# BaseBoard.net
KiCad netlist of a schematic drawn in Altium Designer
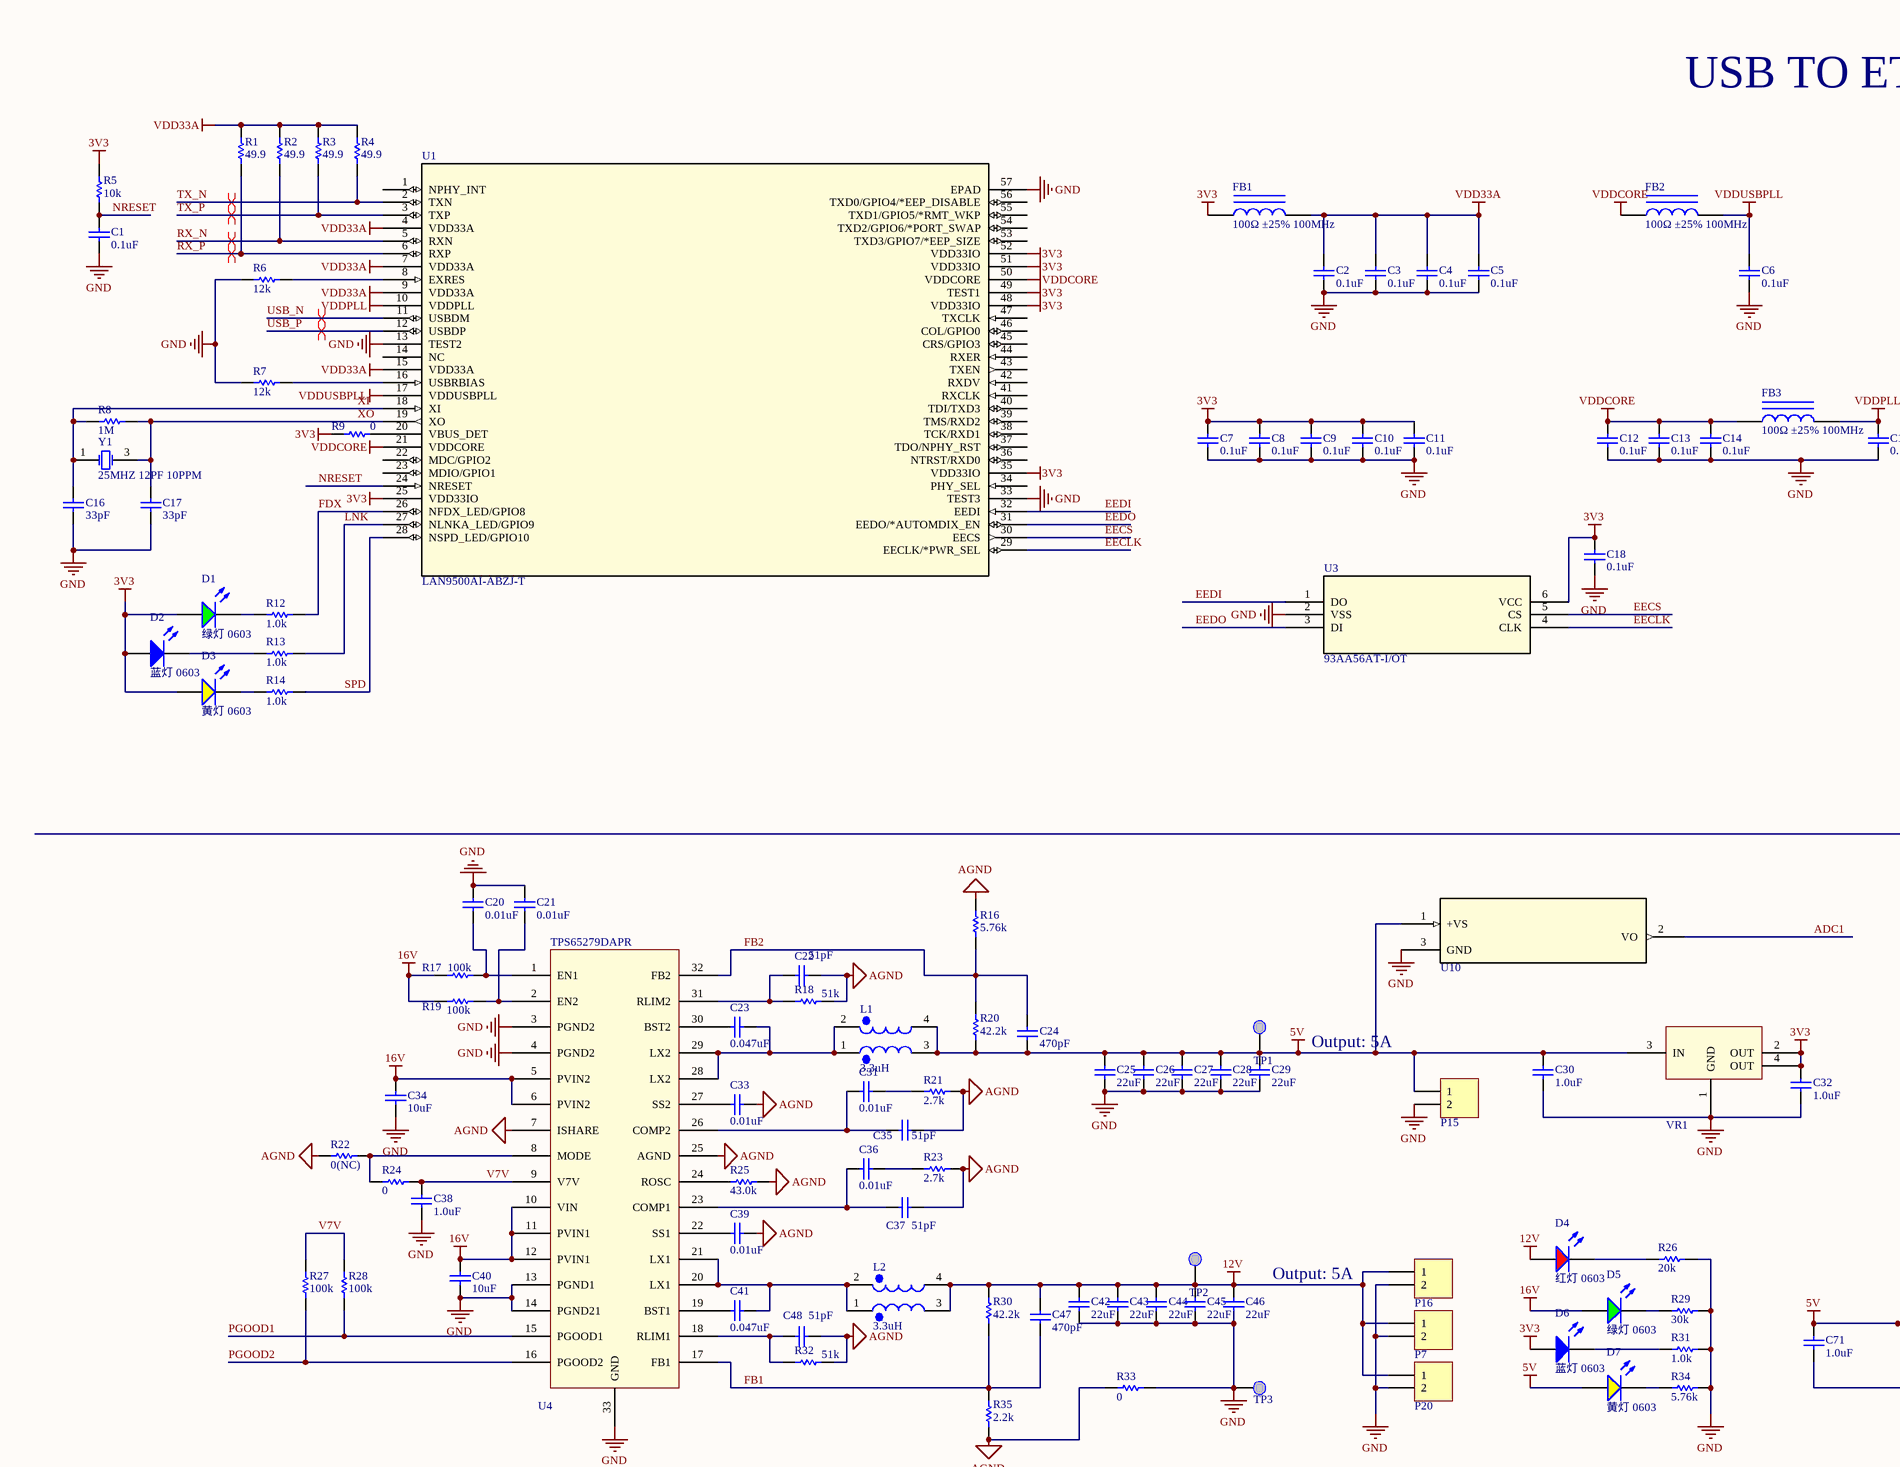
[diagram p0: BaseBoard.SchDoc, top left]
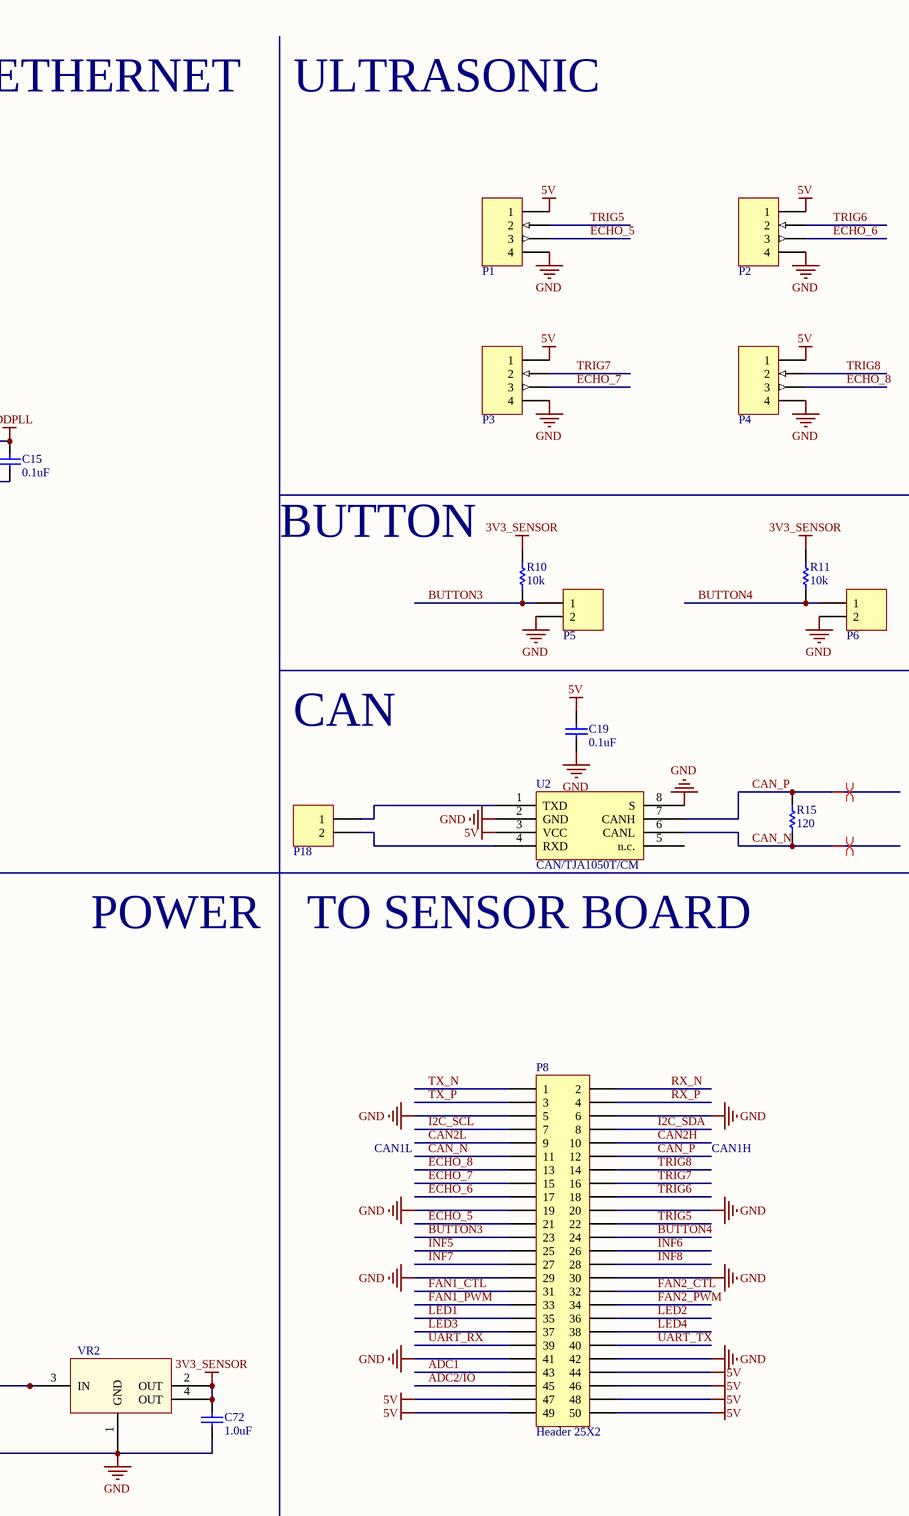
[diagram p1: BaseBoard.SchDoc, top middle]
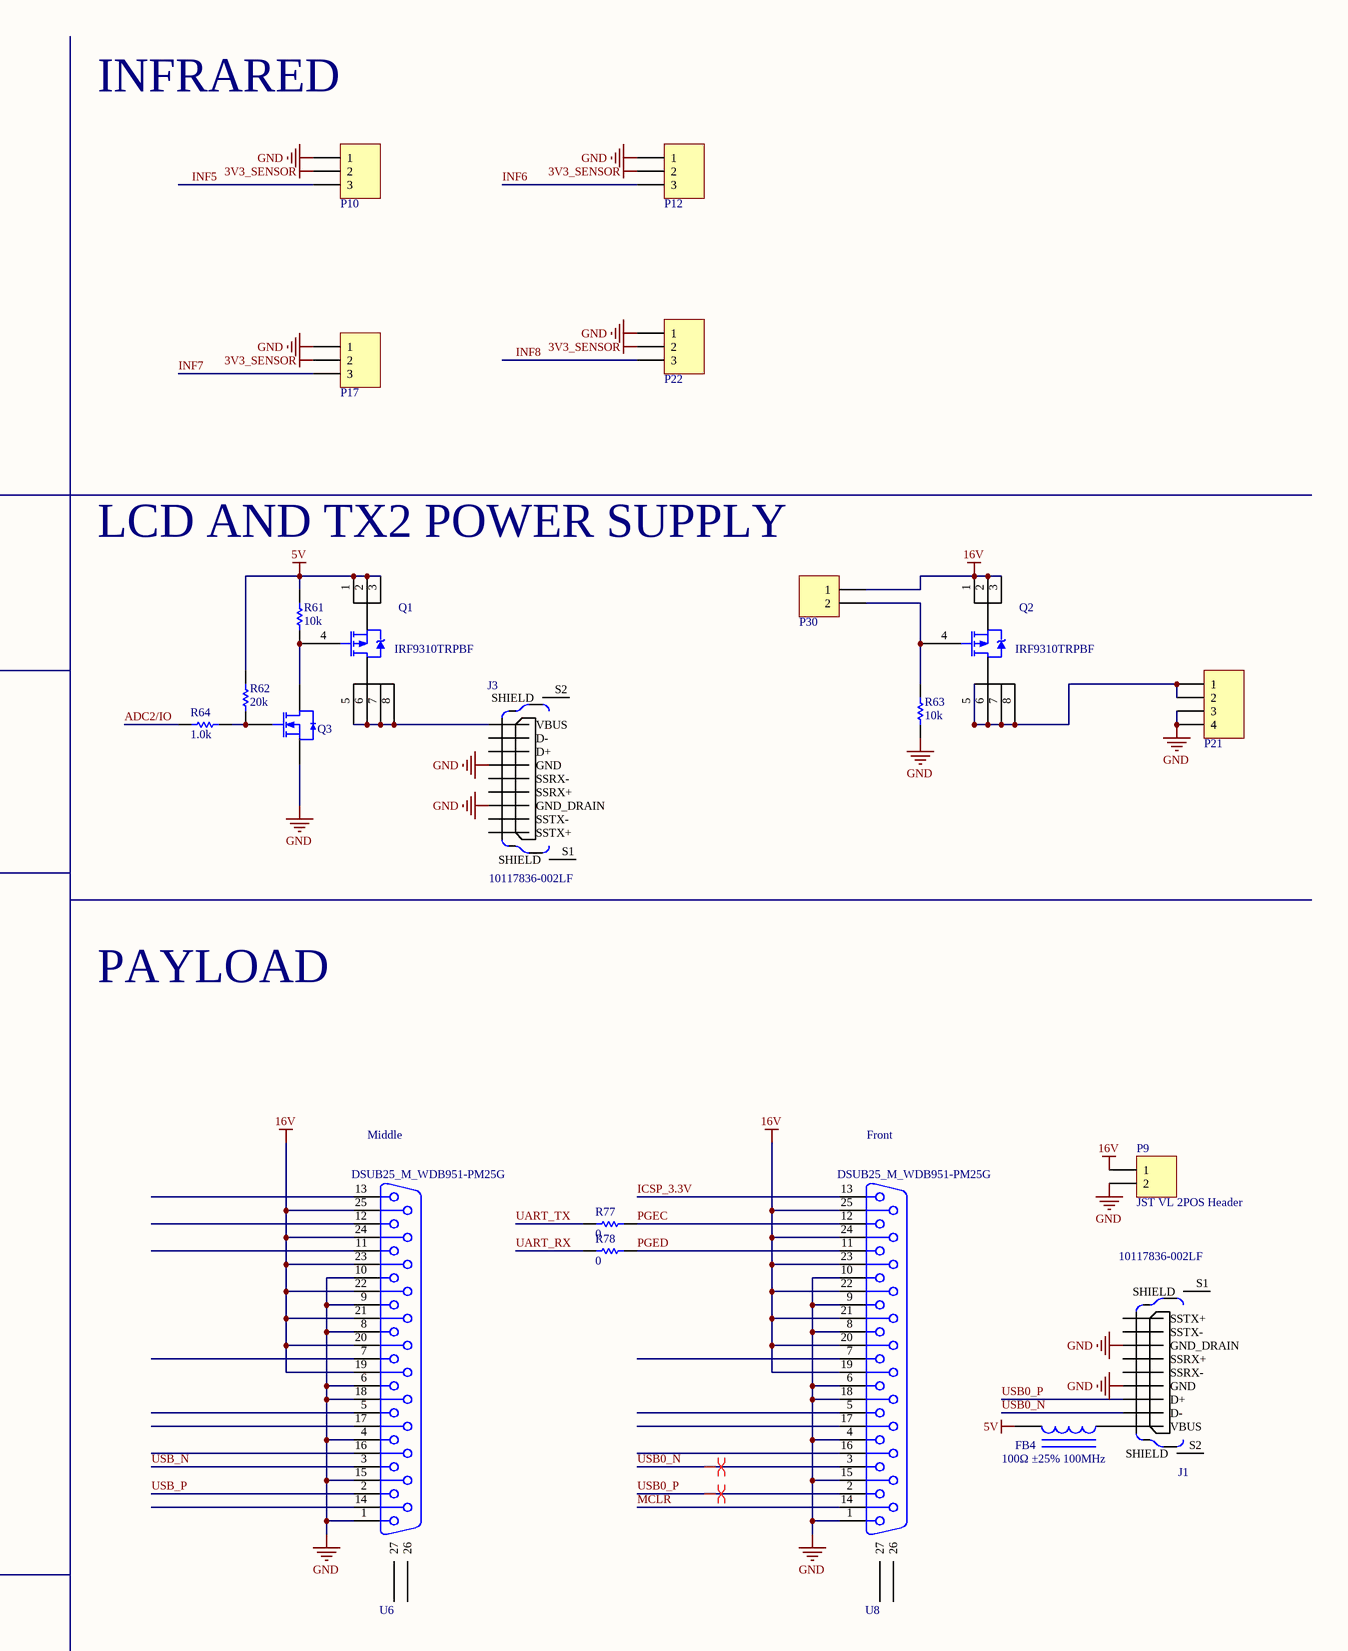
[diagram p2: BaseBoard.SchDoc, top right]
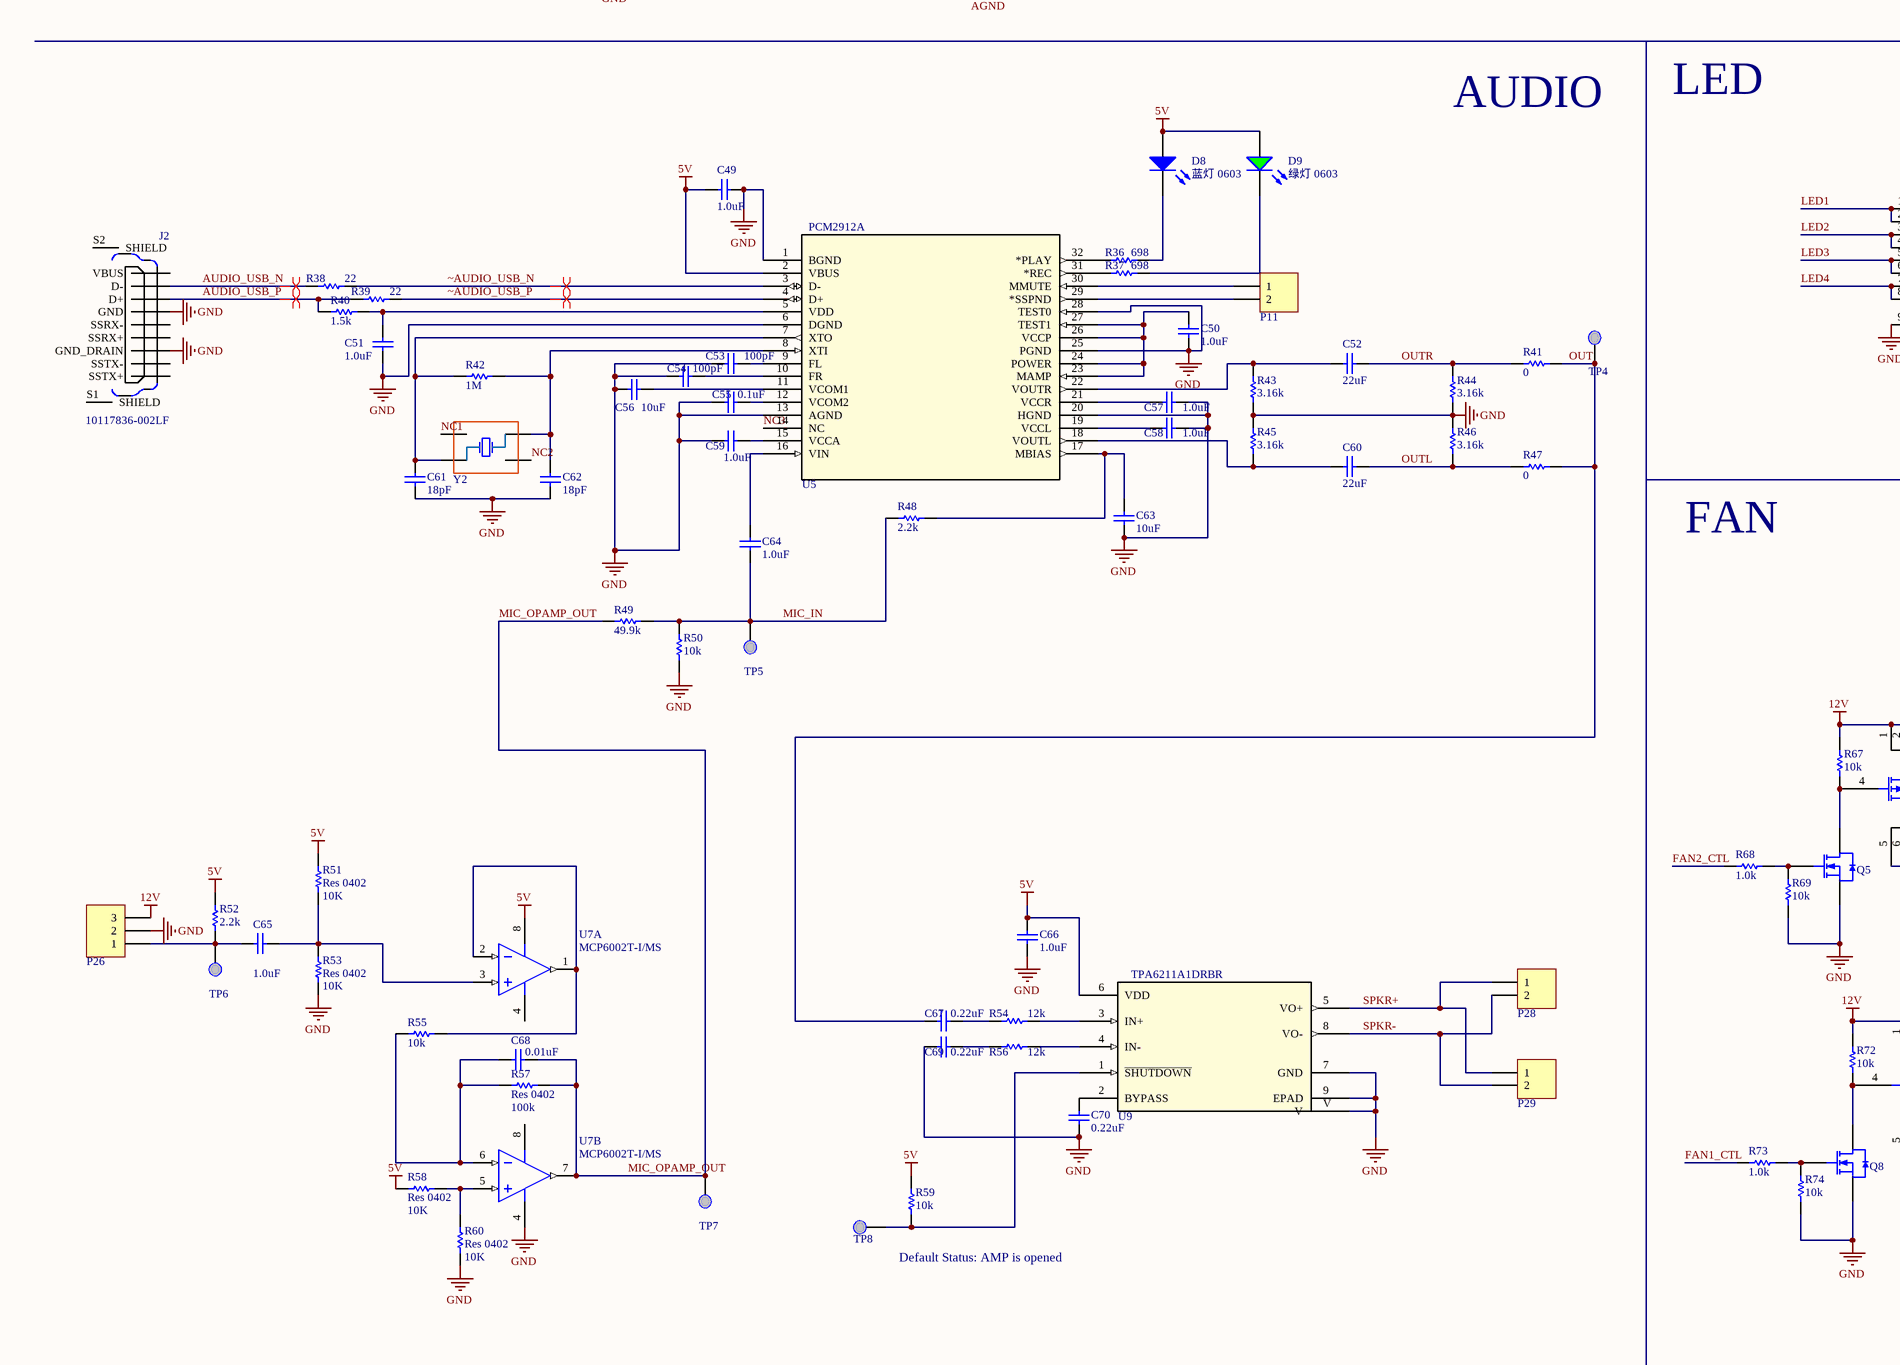
[diagram p3: BaseBoard.SchDoc, bottom left]
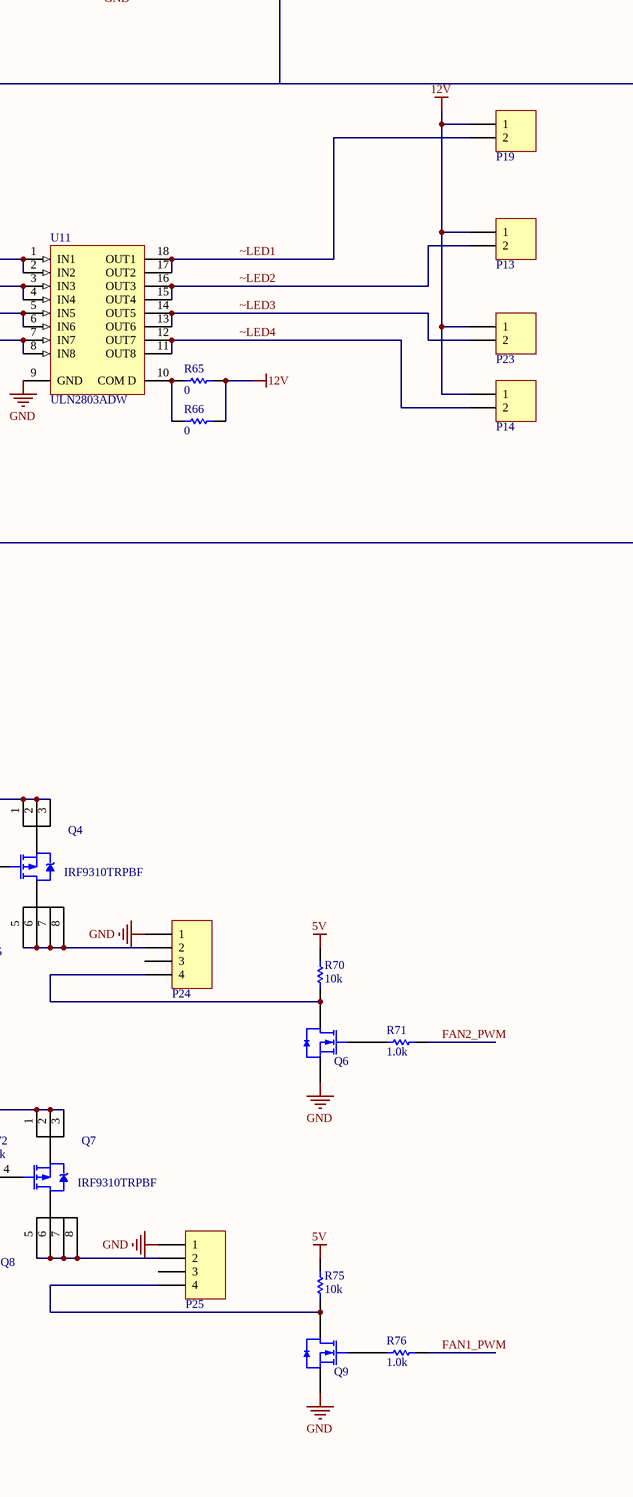
[diagram p4: BaseBoard.SchDoc, bottom middle]
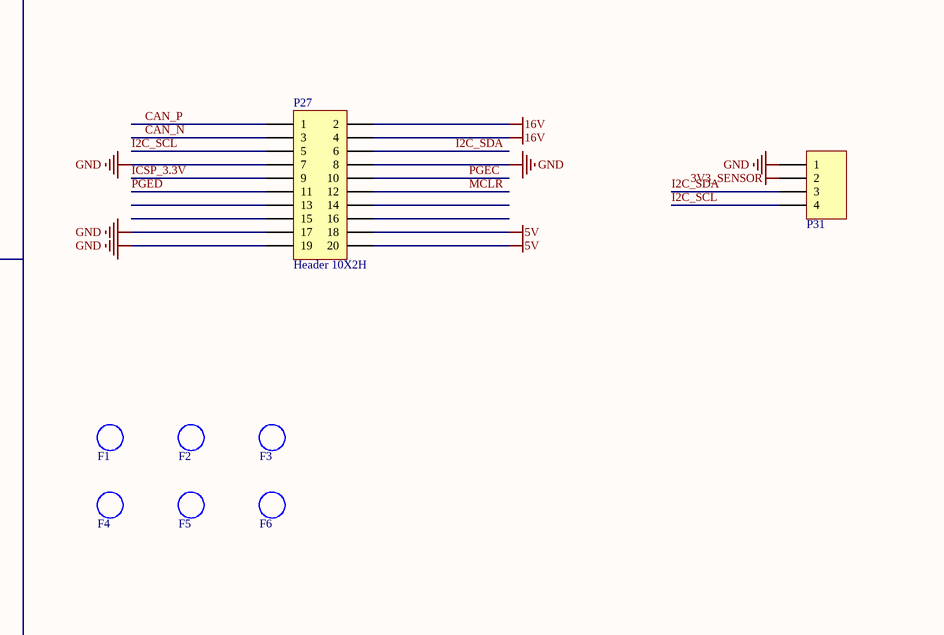
[diagram p5: BaseBoard.SchDoc, bottom right]

(export (version "E")
  (design (tool "Eeschema 10.0.6"))
  (components
    (comp (ref "C1")
      (value "0.1uF")
      (footprint "CAP0603N")
      (description "0.1µF -20%, +80% 50V Ceramic Capacitor Y5V (F) 0603 (1608 Metric)")
      (fields
        (field (name "PART NUMBER") "CAP CER 0.1UF 50V Y5V 0603")
        (field (name "MANUFACTURER") "AVX Corporation")
      )
      (libsource (lib "RoboteX") (part "Cap Non-Polar"))
    )
    (comp (ref "C2")
      (value "0.1uF")
      (footprint "CAP0402N")
      (description "CAP CER 0.1UF 50V 10% X7R 0402")
      (fields
        (field (name "MANUFACTURER") "TDK Corporation")
        (field (name "MANUFACTURER PART NUMBER") "C1005X7R1H104K")
      )
      (libsource (lib "RoboteX") (part "Cap Non-Polar"))
    )
    (comp (ref "C3")
      (value "0.1uF")
      (footprint "CAP0402N")
      (description "CAP CER 0.1UF 50V 10% X7R 0402")
      (fields
        (field (name "MANUFACTURER") "TDK Corporation")
        (field (name "MANUFACTURER PART NUMBER") "C1005X7R1H104K")
      )
      (libsource (lib "RoboteX") (part "Cap Non-Polar"))
    )
    (comp (ref "C4")
      (value "0.1uF")
      (footprint "CAP0402N")
      (description "CAP CER 0.1UF 50V 10% X7R 0402")
      (fields
        (field (name "MANUFACTURER") "TDK Corporation")
        (field (name "MANUFACTURER PART NUMBER") "C1005X7R1H104K")
      )
      (libsource (lib "RoboteX") (part "Cap Non-Polar"))
    )
    (comp (ref "C5")
      (value "0.1uF")
      (footprint "CAP0402N")
      (description "CAP CER 0.1UF 50V 10% X7R 0402")
      (fields
        (field (name "MANUFACTURER") "TDK Corporation")
        (field (name "MANUFACTURER PART NUMBER") "C1005X7R1H104K")
      )
      (libsource (lib "RoboteX") (part "Cap Non-Polar"))
    )
    (comp (ref "C6")
      (value "0.1uF")
      (footprint "CAP0402N")
      (description "CAP CER 0.1UF 50V 10% X7R 0402")
      (fields
        (field (name "MANUFACTURER") "TDK Corporation")
        (field (name "MANUFACTURER PART NUMBER") "C1005X7R1H104K")
      )
      (libsource (lib "RoboteX") (part "Cap Non-Polar"))
    )
    (comp (ref "C7")
      (value "0.1uF")
      (footprint "CAP0402N")
      (description "CAP CER 0.1UF 50V 10% X7R 0402")
      (fields
        (field (name "MANUFACTURER") "TDK Corporation")
        (field (name "MANUFACTURER PART NUMBER") "C1005X7R1H104K")
      )
      (libsource (lib "RoboteX") (part "Cap Non-Polar"))
    )
    (comp (ref "C8")
      (value "0.1uF")
      (footprint "CAP0402N")
      (description "CAP CER 0.1UF 50V 10% X7R 0402")
      (fields
        (field (name "MANUFACTURER") "TDK Corporation")
        (field (name "MANUFACTURER PART NUMBER") "C1005X7R1H104K")
      )
      (libsource (lib "RoboteX") (part "Cap Non-Polar"))
    )
    (comp (ref "C9")
      (value "0.1uF")
      (footprint "CAP0402N")
      (description "CAP CER 0.1UF 50V 10% X7R 0402")
      (fields
        (field (name "MANUFACTURER") "TDK Corporation")
        (field (name "MANUFACTURER PART NUMBER") "C1005X7R1H104K")
      )
      (libsource (lib "RoboteX") (part "Cap Non-Polar"))
    )
    (comp (ref "C10")
      (value "0.1uF")
      (footprint "CAP0402N")
      (description "CAP CER 0.1UF 50V 10% X7R 0402")
      (fields
        (field (name "MANUFACTURER") "TDK Corporation")
        (field (name "MANUFACTURER PART NUMBER") "C1005X7R1H104K")
      )
      (libsource (lib "RoboteX") (part "Cap Non-Polar"))
    )
    (comp (ref "C11")
      (value "0.1uF")
      (footprint "CAP0402N")
      (description "CAP CER 0.1UF 50V 10% X7R 0402")
      (fields
        (field (name "MANUFACTURER") "TDK Corporation")
        (field (name "MANUFACTURER PART NUMBER") "C1005X7R1H104K")
      )
      (libsource (lib "RoboteX") (part "Cap Non-Polar"))
    )
    (comp (ref "C12")
      (value "0.1uF")
      (footprint "CAP0402N")
      (description "CAP CER 0.1UF 50V 10% X7R 0402")
      (fields
        (field (name "MANUFACTURER") "TDK Corporation")
        (field (name "MANUFACTURER PART NUMBER") "C1005X7R1H104K")
      )
      (libsource (lib "RoboteX") (part "Cap Non-Polar"))
    )
    (comp (ref "C13")
      (value "0.1uF")
      (footprint "CAP0402N")
      (description "CAP CER 0.1UF 50V 10% X7R 0402")
      (fields
        (field (name "MANUFACTURER") "TDK Corporation")
        (field (name "MANUFACTURER PART NUMBER") "C1005X7R1H104K")
      )
      (libsource (lib "RoboteX") (part "Cap Non-Polar"))
    )
    (comp (ref "C14")
      (value "0.1uF")
      (footprint "CAP0402N")
      (description "CAP CER 0.1UF 50V 10% X7R 0402")
      (fields
        (field (name "MANUFACTURER") "TDK Corporation")
        (field (name "MANUFACTURER PART NUMBER") "C1005X7R1H104K")
      )
      (libsource (lib "RoboteX") (part "Cap Non-Polar"))
    )
    (comp (ref "C15")
      (value "0.1uF")
      (footprint "CAP0402N")
      (description "CAP CER 0.1UF 50V 10% X7R 0402")
      (fields
        (field (name "MANUFACTURER") "TDK Corporation")
        (field (name "MANUFACTURER PART NUMBER") "C1005X7R1H104K")
      )
      (libsource (lib "RoboteX") (part "Cap Non-Polar"))
    )
    (comp (ref "C16")
      (value "33pF")
      (footprint "CAP0402N")
      (description "CAP CERAMIC 33PF 50V NP0 0402")
      (fields
        (field (name "MANUFACTURER") "Yageo")
        (field (name "MANUFACTURER PART NUMBER") "CC0402JRNP09BN330")
      )
      (libsource (lib "RoboteX") (part "Cap Non-Polar"))
    )
    (comp (ref "C17")
      (value "33pF")
      (footprint "CAP0402N")
      (description "CAP CERAMIC 33PF 50V NP0 0402")
      (fields
        (field (name "MANUFACTURER") "Yageo")
        (field (name "MANUFACTURER PART NUMBER") "CC0402JRNP09BN330")
      )
      (libsource (lib "RoboteX") (part "Cap Non-Polar"))
    )
    (comp (ref "C18")
      (value "0.1uF")
      (footprint "CAP0402N")
      (description "CAP CER 0.1UF 50V 10% X7R 0402")
      (fields
        (field (name "MANUFACTURER") "TDK Corporation")
        (field (name "MANUFACTURER PART NUMBER") "C1005X7R1H104K")
      )
      (libsource (lib "RoboteX") (part "Cap Non-Polar"))
    )
    (comp (ref "C19")
      (value "0.1uF")
      (footprint "CAP0402N")
      (description "CAP CER 0.1UF 50V 10% X7R 0402")
      (fields
        (field (name "MANUFACTURER") "TDK Corporation")
        (field (name "MANUFACTURER PART NUMBER") "C1005X7R1H104K")
      )
      (libsource (lib "RoboteX") (part "Cap Non-Polar"))
    )
    (comp (ref "C20")
      (value "0.01uF")
      (footprint "CAP0402N")
      (description "CAP CERAMIC .01UF 50V X7R 0402")
      (fields
        (field (name "MANUFACTURER") "Yageo")
        (field (name "MANUFACTURER PART NUMBER") "CC0402KRX7R9BB103")
      )
      (libsource (lib "RoboteX") (part "Cap Non-Polar"))
    )
    (comp (ref "C21")
      (value "0.01uF")
      (footprint "CAP0402N")
      (description "CAP CERAMIC .01UF 50V X7R 0402")
      (fields
        (field (name "MANUFACTURER") "Yageo")
        (field (name "MANUFACTURER PART NUMBER") "CC0402KRX7R9BB103")
      )
      (libsource (lib "RoboteX") (part "Cap Non-Polar"))
    )
    (comp (ref "C22")
      (value "51pF")
      (footprint "CAP0402N")
      (description "CAP CER 51PF 50V 5% NP0 0402")
      (fields
        (field (name "MANUFACTURER") "Samsung")
        (field (name "MANUFACTURER PART NUMBER") "CL05C510JB5NNNC")
      )
      (libsource (lib "RoboteX") (part "Cap Non-Polar"))
    )
    (comp (ref "C23")
      (value "0.047uF")
      (footprint "CAP0402N")
      (description "CAP CER 47000PF 25V X7R 0402")
      (fields (field (name "MANUFACTURER") "TDK") (field (name "MANUFACTURER PART NUMBER") "C1005X7R1E473K"))
      (libsource (lib "RoboteX") (part "Cap Non-Polar"))
    )
    (comp (ref "C24")
      (value "470pF")
      (footprint "CAP0402N")
      (description "CAP 470PF 50V CERAMIC X7R 0402")
      (fields
        (field (name "MANUFACTURER") "Yageo")
        (field (name "MANUFACTURER PART NUMBER") "CC0402KRX7R9BB471")
      )
      (libsource (lib "RoboteX") (part "Cap Non-Polar"))
    )
    (comp (ref "C25")
      (value "22uF")
      (footprint "CAP1210N")
      (description "CAP CER 22UF 25V 20% X5R 1206")
      (fields
        (field (name "MANUFACTURER") "Taiyo Yuden")
        (field (name "MANUFACTURER PART NUMBER") "TMK316BBJ226ML-T")
      )
      (libsource (lib "RoboteX") (part "Cap Non-Polar"))
    )
    (comp (ref "C26")
      (value "22uF")
      (footprint "CAP1210N")
      (description "CAP CER 22UF 25V 20% X5R 1206")
      (fields
        (field (name "MANUFACTURER") "Taiyo Yuden")
        (field (name "MANUFACTURER PART NUMBER") "TMK316BBJ226ML-T")
      )
      (libsource (lib "RoboteX") (part "Cap Non-Polar"))
    )
    (comp (ref "C27")
      (value "22uF")
      (footprint "CAP1210N")
      (description "CAP CER 22UF 25V 20% X5R 1206")
      (fields
        (field (name "MANUFACTURER") "Taiyo Yuden")
        (field (name "MANUFACTURER PART NUMBER") "TMK316BBJ226ML-T")
      )
      (libsource (lib "RoboteX") (part "Cap Non-Polar"))
    )
    (comp (ref "C28")
      (value "22uF")
      (footprint "CAP1210N")
      (description "CAP CER 22UF 25V 20% X5R 1206")
      (fields
        (field (name "MANUFACTURER") "Taiyo Yuden")
        (field (name "MANUFACTURER PART NUMBER") "TMK316BBJ226ML-T")
      )
      (libsource (lib "RoboteX") (part "Cap Non-Polar"))
    )
    (comp (ref "C29")
      (value "22uF")
      (footprint "CAP1210N")
      (description "CAP CER 22UF 25V 20% X5R 1206")
      (fields
        (field (name "MANUFACTURER") "Taiyo Yuden")
        (field (name "MANUFACTURER PART NUMBER") "TMK316BBJ226ML-T")
      )
      (libsource (lib "RoboteX") (part "Cap Non-Polar"))
    )
    (comp (ref "C30")
      (value "1.0uF")
      (footprint "CAP0805N")
      (description "CAP CER 1.0UF 25V X7R 0805")
      (fields
        (field (name "MANUFACTURER") "Taiyo Yuden")
        (field (name "MANUFACTURER PART NUMBER") "TMK212B7105KG-T")
      )
      (libsource (lib "RoboteX") (part "Cap Non-Polar"))
    )
    (comp (ref "C31")
      (value "0.01uF")
      (footprint "CAP0402N")
      (description "CAP CERAMIC .01UF 50V X7R 0402")
      (fields
        (field (name "MANUFACTURER") "Yageo")
        (field (name "MANUFACTURER PART NUMBER") "CC0402KRX7R9BB103")
      )
      (libsource (lib "RoboteX") (part "Cap Non-Polar"))
    )
    (comp (ref "C32")
      (value "1.0uF")
      (footprint "CAP0805N")
      (description "CAP CER 1.0UF 25V X7R 0805")
      (fields
        (field (name "MANUFACTURER") "Taiyo Yuden")
        (field (name "MANUFACTURER PART NUMBER") "TMK212B7105KG-T")
      )
      (libsource (lib "RoboteX") (part "Cap Non-Polar"))
    )
    (comp (ref "C33")
      (value "0.01uF")
      (footprint "CAP0402N")
      (description "CAP CERAMIC .01UF 50V X7R 0402")
      (fields
        (field (name "MANUFACTURER") "Yageo")
        (field (name "MANUFACTURER PART NUMBER") "CC0402KRX7R9BB103")
      )
      (libsource (lib "RoboteX") (part "Cap Non-Polar"))
    )
    (comp (ref "C34")
      (value "10uF")
      (footprint "CAP1206N")
      (description "CAP CER 10UF 50V 10% X5R 1206")
      (fields
        (field (name "MANUFACTURER") "AVX Corporation")
        (field (name "MANUFACTURER PART NUMBER") "C3216X5R1H106K")
      )
      (libsource (lib "RoboteX") (part "Cap Non-Polar"))
    )
    (comp (ref "C35")
      (value "51pF")
      (footprint "CAP0402N")
      (description "CAP CER 51PF 50V 5% NP0 0402")
      (fields
        (field (name "MANUFACTURER") "Samsung")
        (field (name "MANUFACTURER PART NUMBER") "CL05C510JB5NNNC")
      )
      (libsource (lib "RoboteX") (part "Cap Non-Polar"))
    )
    (comp (ref "C36")
      (value "0.01uF")
      (footprint "CAP0402N")
      (description "CAP CERAMIC .01UF 50V X7R 0402")
      (fields
        (field (name "MANUFACTURER") "Yageo")
        (field (name "MANUFACTURER PART NUMBER") "CC0402KRX7R9BB103")
      )
      (libsource (lib "RoboteX") (part "Cap Non-Polar"))
    )
    (comp (ref "C37")
      (value "51pF")
      (footprint "CAP0402N")
      (description "CAP CER 51PF 50V 5% NP0 0402")
      (fields
        (field (name "MANUFACTURER") "Samsung")
        (field (name "MANUFACTURER PART NUMBER") "CL05C510JB5NNNC")
      )
      (libsource (lib "RoboteX") (part "Cap Non-Polar"))
    )
    (comp (ref "C38")
      (value "1.0uF")
      (footprint "CAP0603N")
      (description "CAP CER 1UF 25V 10% X7R 0603")
      (fields (field (name "MANUFACTURER") "TDK") (field (name "MANUFACTURER PART NUMBER") "C1608X7R1E105K"))
      (libsource (lib "RoboteX") (part "Cap Non-Polar"))
    )
    (comp (ref "C39")
      (value "0.01uF")
      (footprint "CAP0402N")
      (description "CAP CERAMIC .01UF 50V X7R 0402")
      (fields
        (field (name "MANUFACTURER") "Yageo")
        (field (name "MANUFACTURER PART NUMBER") "CC0402KRX7R9BB103")
      )
      (libsource (lib "RoboteX") (part "Cap Non-Polar"))
    )
    (comp (ref "C40")
      (value "10uF")
      (footprint "CAP1206N")
      (description "CAP CER 10UF 50V 10% X5R 1206")
      (fields
        (field (name "MANUFACTURER") "AVX Corporation")
        (field (name "MANUFACTURER PART NUMBER") "C3216X5R1H106K")
      )
      (libsource (lib "RoboteX") (part "Cap Non-Polar"))
    )
    (comp (ref "C41")
      (value "0.047uF")
      (footprint "CAP0402N")
      (description "CAP CER 47000PF 25V X7R 0402")
      (fields (field (name "MANUFACTURER") "TDK") (field (name "MANUFACTURER PART NUMBER") "C1005X7R1E473K"))
      (libsource (lib "RoboteX") (part "Cap Non-Polar"))
    )
    (comp (ref "C42")
      (value "22uF")
      (footprint "CAP1210N")
      (description "CAP CER 22UF 25V 20% X5R 1206")
      (fields
        (field (name "MANUFACTURER") "Taiyo Yuden")
        (field (name "MANUFACTURER PART NUMBER") "TMK316BBJ226ML-T")
      )
      (libsource (lib "RoboteX") (part "Cap Non-Polar"))
    )
    (comp (ref "C43")
      (value "22uF")
      (footprint "CAP1210N")
      (description "CAP CER 22UF 25V 20% X5R 1206")
      (fields
        (field (name "MANUFACTURER") "Taiyo Yuden")
        (field (name "MANUFACTURER PART NUMBER") "TMK316BBJ226ML-T")
      )
      (libsource (lib "RoboteX") (part "Cap Non-Polar"))
    )
    (comp (ref "C44")
      (value "22uF")
      (footprint "CAP1210N")
      (description "CAP CER 22UF 25V 20% X5R 1206")
      (fields
        (field (name "MANUFACTURER") "Taiyo Yuden")
        (field (name "MANUFACTURER PART NUMBER") "TMK316BBJ226ML-T")
      )
      (libsource (lib "RoboteX") (part "Cap Non-Polar"))
    )
    (comp (ref "C45")
      (value "22uF")
      (footprint "CAP1210N")
      (description "CAP CER 22UF 25V 20% X5R 1206")
      (fields
        (field (name "MANUFACTURER") "Taiyo Yuden")
        (field (name "MANUFACTURER PART NUMBER") "TMK316BBJ226ML-T")
      )
      (libsource (lib "RoboteX") (part "Cap Non-Polar"))
    )
    (comp (ref "C46")
      (value "22uF")
      (footprint "CAP1210N")
      (description "CAP CER 22UF 25V 20% X5R 1206")
      (fields
        (field (name "MANUFACTURER") "Taiyo Yuden")
        (field (name "MANUFACTURER PART NUMBER") "TMK316BBJ226ML-T")
      )
      (libsource (lib "RoboteX") (part "Cap Non-Polar"))
    )
    (comp (ref "C47")
      (value "470pF")
      (footprint "CAP0402N")
      (description "CAP 470PF 50V CERAMIC X7R 0402")
      (fields
        (field (name "MANUFACTURER") "Yageo")
        (field (name "MANUFACTURER PART NUMBER") "CC0402KRX7R9BB471")
      )
      (libsource (lib "RoboteX") (part "Cap Non-Polar"))
    )
    (comp (ref "C48")
      (value "51pF")
      (footprint "CAP0402N")
      (description "CAP CER 51PF 50V 5% NP0 0402")
      (fields
        (field (name "MANUFACTURER") "Samsung")
        (field (name "MANUFACTURER PART NUMBER") "CL05C510JB5NNNC")
      )
      (libsource (lib "RoboteX") (part "Cap Non-Polar"))
    )
    (comp (ref "C49")
      (value "1.0uF")
      (footprint "CAP0805N")
      (description "CAP CER 1.0UF 25V X7R 0805")
      (fields
        (field (name "MANUFACTURER") "Taiyo Yuden")
        (field (name "MANUFACTURER PART NUMBER") "TMK212B7105KG-T")
      )
      (libsource (lib "RoboteX") (part "Cap Non-Polar"))
    )
    (comp (ref "C50")
      (value "1.0uF")
      (footprint "CAP0805N")
      (description "CAP CER 1.0UF 25V X7R 0805")
      (fields
        (field (name "MANUFACTURER") "Taiyo Yuden")
        (field (name "MANUFACTURER PART NUMBER") "TMK212B7105KG-T")
      )
      (libsource (lib "RoboteX") (part "Cap Non-Polar"))
    )
    (comp (ref "C51")
      (value "1.0uF")
      (footprint "CAP0805N")
      (description "CAP CER 1.0UF 25V X7R 0805")
      (fields
        (field (name "MANUFACTURER") "Taiyo Yuden")
        (field (name "MANUFACTURER PART NUMBER") "TMK212B7105KG-T")
      )
      (libsource (lib "RoboteX") (part "Cap Non-Polar"))
    )
    (comp (ref "C52")
      (value "22uF")
      (footprint "CAP0805N")
      (description "CAP CER 22UF 10V X5R 0805")
      (fields
        (field (name "MANUFACTURER") "Taiyo Yuden")
        (field (name "MANUFACTURER PART NUMBER") "LMK212BJ226MG-T")
      )
      (libsource (lib "RoboteX") (part "Cap Non-Polar"))
    )
    (comp (ref "C53")
      (value "100pF")
      (footprint "CAP0402N")
      (description "CAP CERAMIC 100PF 50V NP0 0402")
      (fields
        (field (name "MANUFACTURER") "Yageo")
        (field (name "MANUFACTURER PART NUMBER") "CC0402JRNP09BN101")
      )
      (libsource (lib "RoboteX") (part "Cap Non-Polar"))
    )
    (comp (ref "C54")
      (value "100pF")
      (footprint "CAP0402N")
      (description "CAP CERAMIC 100PF 50V NP0 0402")
      (fields
        (field (name "MANUFACTURER") "Yageo")
        (field (name "MANUFACTURER PART NUMBER") "CC0402JRNP09BN101")
      )
      (libsource (lib "RoboteX") (part "Cap Non-Polar"))
    )
    (comp (ref "C55")
      (value "0.1uF")
      (footprint "CAP0402N")
      (description "CAP CER 0.1UF 50V 10% X7R 0402")
      (fields
        (field (name "MANUFACTURER") "TDK Corporation")
        (field (name "MANUFACTURER PART NUMBER") "C1005X7R1H104K")
      )
      (libsource (lib "RoboteX") (part "Cap Non-Polar"))
    )
    (comp (ref "C56")
      (value "10uF")
      (footprint "CAP0805N")
      (description "CAP CER 10UF 25V X5R 0805")
      (fields
        (field (name "MANUFACTURER") "Murata")
        (field (name "MANUFACTURER PART NUMBER") "GRM21BR61E106KA73L")
      )
      (libsource (lib "RoboteX") (part "Cap Non-Polar"))
    )
    (comp (ref "C57")
      (value "1.0uF")
      (footprint "CAP0805N")
      (description "CAP CER 1.0UF 25V X7R 0805")
      (fields
        (field (name "MANUFACTURER") "Taiyo Yuden")
        (field (name "MANUFACTURER PART NUMBER") "TMK212B7105KG-T")
      )
      (libsource (lib "RoboteX") (part "Cap Non-Polar"))
    )
    (comp (ref "C58")
      (value "1.0uF")
      (footprint "CAP0805N")
      (description "CAP CER 1.0UF 25V X7R 0805")
      (fields
        (field (name "MANUFACTURER") "Taiyo Yuden")
        (field (name "MANUFACTURER PART NUMBER") "TMK212B7105KG-T")
      )
      (libsource (lib "RoboteX") (part "Cap Non-Polar"))
    )
    (comp (ref "C59")
      (value "1.0uF")
      (footprint "CAP0805N")
      (description "CAP CER 1.0UF 25V X7R 0805")
      (fields
        (field (name "MANUFACTURER") "Taiyo Yuden")
        (field (name "MANUFACTURER PART NUMBER") "TMK212B7105KG-T")
      )
      (libsource (lib "RoboteX") (part "Cap Non-Polar"))
    )
    (comp (ref "C60")
      (value "22uF")
      (footprint "CAP0805N")
      (description "CAP CER 22UF 10V X5R 0805")
      (fields
        (field (name "MANUFACTURER") "Taiyo Yuden")
        (field (name "MANUFACTURER PART NUMBER") "LMK212BJ226MG-T")
      )
      (libsource (lib "RoboteX") (part "Cap Non-Polar"))
    )
    (comp (ref "C61")
      (value "18pF")
      (footprint "CAP0402N")
      (description "CAP CER 18PF 50V 5% NPO 0402")
      (fields
        (field (name "MANUFACTURER") "Yageo")
        (field (name "MANUFACTURER PART NUMBER") "CC0402JRNPO9BN180")
      )
      (libsource (lib "RoboteX") (part "Cap Non-Polar"))
    )
    (comp (ref "C62")
      (value "18pF")
      (footprint "CAP0402N")
      (description "CAP CER 18PF 50V 5% NPO 0402")
      (fields
        (field (name "MANUFACTURER") "Yageo")
        (field (name "MANUFACTURER PART NUMBER") "CC0402JRNPO9BN180")
      )
      (libsource (lib "RoboteX") (part "Cap Non-Polar"))
    )
    (comp (ref "C63")
      (value "10uF")
      (footprint "CAP0805N")
      (description "CAP CER 10UF 25V X5R 0805")
      (fields
        (field (name "MANUFACTURER") "Murata")
        (field (name "MANUFACTURER PART NUMBER") "GRM21BR61E106KA73L")
      )
      (libsource (lib "RoboteX") (part "Cap Non-Polar"))
    )
    (comp (ref "C64")
      (value "1.0uF")
      (footprint "CAP0805N")
      (description "CAP CER 1.0UF 25V X7R 0805")
      (fields
        (field (name "MANUFACTURER") "Taiyo Yuden")
        (field (name "MANUFACTURER PART NUMBER") "TMK212B7105KG-T")
      )
      (libsource (lib "RoboteX") (part "Cap Non-Polar"))
    )
    (comp (ref "C65")
      (value "1.0uF")
      (footprint "CAP0402N")
      (description "CAP CER 1.0UF 6.3V 10% X5R 0402")
      (fields
        (field (name "MANUFACTURER") "Murata Electronics North America")
        (field (name "MANUFACTURER PART NUMBER") "GRM155R60J105KE19D")
      )
      (libsource (lib "") (part "Cap Non-Polar_1"))
    )
    (comp (ref "C66")
      (value "1.0uF")
      (footprint "CAP0603N")
      (description "CAP CER 1UF 25V 10% X7R 0603")
      (fields (field (name "MANUFACTURER") "TDK") (field (name "MANUFACTURER PART NUMBER") "C1608X7R1E105K"))
      (libsource (lib "RoboteX") (part "Cap Non-Polar"))
    )
    (comp (ref "C67")
      (value "0.22uF")
      (footprint "CAP0402N")
      (description "CAP CER .22UF 25V X5R 10% 0402")
      (fields (field (name "MANUFACTURER") "TDK") (field (name "MANUFACTURER PART NUMBER") "C1005X5R1E224K"))
      (libsource (lib "RoboteX") (part "Cap Non-Polar"))
    )
    (comp (ref "C68")
      (value "0.01uF")
      (footprint "CAP0402N")
      (description "CAP CERAMIC .01UF 50V X7R 0402")
      (fields
        (field (name "MANUFACTURER") "Yageo")
        (field (name "MANUFACTURER PART NUMBER") "CC0402KRX7R9BB103")
      )
      (libsource (lib "RoboteX") (part "Cap Non-Polar"))
    )
    (comp (ref "C69")
      (value "0.22uF")
      (footprint "CAP0402N")
      (description "CAP CER .22UF 25V X5R 10% 0402")
      (fields (field (name "MANUFACTURER") "TDK") (field (name "MANUFACTURER PART NUMBER") "C1005X5R1E224K"))
      (libsource (lib "RoboteX") (part "Cap Non-Polar"))
    )
    (comp (ref "C70")
      (value "0.22uF")
      (footprint "CAP0402N")
      (description "CAP CER .22UF 25V X5R 10% 0402")
      (fields (field (name "MANUFACTURER") "TDK") (field (name "MANUFACTURER PART NUMBER") "C1005X5R1E224K"))
      (libsource (lib "RoboteX") (part "Cap Non-Polar"))
    )
    (comp (ref "C71")
      (value "1.0uF")
      (footprint "CAP0805N")
      (description "CAP CER 1.0UF 25V X7R 0805")
      (fields
        (field (name "MANUFACTURER") "Taiyo Yuden")
        (field (name "MANUFACTURER PART NUMBER") "TMK212B7105KG-T")
      )
      (libsource (lib "RoboteX") (part "Cap Non-Polar"))
    )
    (comp (ref "C72")
      (value "1.0uF")
      (footprint "CAP0805N")
      (description "CAP CER 1.0UF 25V X7R 0805")
      (fields
        (field (name "MANUFACTURER") "Taiyo Yuden")
        (field (name "MANUFACTURER PART NUMBER") "TMK212B7105KG-T")
      )
      (libsource (lib "RoboteX") (part "Cap Non-Polar"))
    )
    (comp (ref "D1")
      (value "绿灯 0603")
      (footprint "0603_LED_S1")
      (description "发光二极管")
      (libsource (lib "Miscellaneous Devices LC") (part "0603 绿灯"))
    )
    (comp (ref "D2")
      (value "蓝灯 0603")
      (footprint "0603_LED_S1")
      (description "发光二极管")
      (libsource (lib "Miscellaneous Devices LC") (part "0603 蓝灯"))
    )
    (comp (ref "D3")
      (value "黄灯 0603")
      (footprint "0603_LED_S1")
      (description "发光二极管")
      (libsource (lib "Miscellaneous Devices LC") (part "0603 黄灯"))
    )
    (comp (ref "D4")
      (value "红灯 0603")
      (footprint "0603_LED_S1")
      (description "发光二极管")
      (libsource (lib "Miscellaneous Devices LC") (part "0603 红灯"))
    )
    (comp (ref "D5")
      (value "绿灯 0603")
      (footprint "0603_LED_S1")
      (description "发光二极管")
      (libsource (lib "Miscellaneous Devices LC") (part "0603 绿灯"))
    )
    (comp (ref "D6")
      (value "蓝灯 0603")
      (footprint "0603_LED_S1")
      (description "发光二极管")
      (libsource (lib "Miscellaneous Devices LC") (part "0603 蓝灯"))
    )
    (comp (ref "D7")
      (value "黄灯 0603")
      (footprint "0603_LED_S1")
      (description "发光二极管")
      (libsource (lib "Miscellaneous Devices LC") (part "0603 黄灯"))
    )
    (comp (ref "D8")
      (value "蓝灯 0603")
      (footprint "0603_LED_S1")
      (description "发光二极管")
      (libsource (lib "Miscellaneous Devices LC") (part "0603 蓝灯"))
    )
    (comp (ref "D9")
      (value "绿灯 0603")
      (footprint "0603_LED_S1")
      (description "发光二极管")
      (libsource (lib "Miscellaneous Devices LC") (part "0603 绿灯"))
    )
    (comp (ref "F1")
      (value "Fiducial, .040\"")
      (footprint "FIDUCIAL, .040\"")
      (libsource (lib "RoboteX") (part "Fiducial"))
    )
    (comp (ref "F2")
      (value "Fiducial, .040\"")
      (footprint "FIDUCIAL, .040\"")
      (libsource (lib "RoboteX") (part "Fiducial"))
    )
    (comp (ref "F3")
      (value "Fiducial, .040\"")
      (footprint "FIDUCIAL, .040\"")
      (libsource (lib "RoboteX") (part "Fiducial"))
    )
    (comp (ref "F4")
      (value "Fiducial, .040\"")
      (footprint "FIDUCIAL, .040\"")
      (libsource (lib "RoboteX") (part "Fiducial"))
    )
    (comp (ref "F5")
      (value "Fiducial, .040\"")
      (footprint "FIDUCIAL, .040\"")
      (libsource (lib "RoboteX") (part "Fiducial"))
    )
    (comp (ref "F6")
      (value "Fiducial, .040\"")
      (footprint "FIDUCIAL, .040\"")
      (libsource (lib "RoboteX") (part "Fiducial"))
    )
    (comp (ref "FB1")
      (value "100Ω ±25% 100MHz")
      (footprint "0805_L")
      (description "贴片磁珠")
      (libsource (lib "Miscellaneous Devices LC") (part "0805 100Ω 25% 100MHz"))
    )
    (comp (ref "FB2")
      (value "100Ω ±25% 100MHz")
      (footprint "0805_L")
      (description "贴片磁珠")
      (libsource (lib "Miscellaneous Devices LC") (part "0805 100Ω 25% 100MHz"))
    )
    (comp (ref "FB3")
      (value "100Ω ±25% 100MHz")
      (footprint "0805_L")
      (description "贴片磁珠")
      (libsource (lib "Miscellaneous Devices LC") (part "0805 100Ω 25% 100MHz"))
    )
    (comp (ref "FB4")
      (value "100Ω ±25% 100MHz")
      (footprint "0805_L")
      (description "贴片磁珠")
      (libsource (lib "Miscellaneous Devices LC") (part "0805 100Ω 25% 100MHz"))
    )
    (comp (ref "J1")
      (value "10117836-002LF")
      (footprint "AMPHENOL_10117836-002LF_10117836-002LF(Primary)")
      (description "Usb, 3.0 Type A, Receptacle, SMT")
      (fields
        (field (name "MANUFACTURER") "Amphenol FCI")
        (field (name "DIGI-KEY_PART_NUMBER") "609-4660-ND")
      )
      (libsource (lib "lib") (part "10117836-002LF"))
    )
    (comp (ref "J2")
      (value "10117836-002LF")
      (footprint "AMPHENOL_10117836-002LF_10117836-002LF(Primary)")
      (description "Usb, 3.0 Type A, Receptacle, SMT")
      (fields
        (field (name "MANUFACTURER") "Amphenol FCI")
        (field (name "DIGI-KEY_PART_NUMBER") "609-4660-ND")
      )
      (libsource (lib "lib") (part "10117836-002LF"))
    )
    (comp (ref "J3")
      (value "10117836-002LF")
      (footprint "AMPHENOL_10117836-002LF_10117836-002LF(Primary)")
      (description "Usb, 3.0 Type A, Receptacle, SMT")
      (fields
        (field (name "MANUFACTURER") "Amphenol FCI")
        (field (name "DIGI-KEY_PART_NUMBER") "609-4660-ND")
      )
      (libsource (lib "") (part "10117836-002LF_1"))
    )
    (comp (ref "L1")
      (value "3.3uH")
      (footprint "SRF1280")
      (description "INDUCT ARRAY 2 COIL 3.3UH SMD")
      (fields
        (field (name "MANUFACTURER") "Bourns Inc.")
        (field (name "MANUFACTURER PART NUMBER") "SRF1280-3R3Y")
      )
      (libsource (lib "RoboteX") (part "Inductor_pin4"))
    )
    (comp (ref "L2")
      (value "3.3uH")
      (footprint "SRF1280")
      (description "INDUCT ARRAY 2 COIL 3.3UH SMD")
      (fields
        (field (name "MANUFACTURER") "Bourns Inc.")
        (field (name "MANUFACTURER PART NUMBER") "SRF1280-3R3Y")
      )
      (libsource (lib "RoboteX") (part "Inductor_pin4"))
    )
    (comp (ref "P1")
      (value "B4B-PH-SM4-TB(LF)(SN)")
      (footprint "B4B-PH-SM4-TB(LF)(SN)")
      (description "CONN HEADER PH TOP 4POS 2MM SMD")
      (fields (field (name "MANUFACTURER") "JST Sales America Inc."))
      (libsource (lib "RoboteX") (part "Header 4"))
    )
    (comp (ref "P2")
      (value "B4B-PH-SM4-TB(LF)(SN)")
      (footprint "B4B-PH-SM4-TB(LF)(SN)")
      (description "CONN HEADER PH TOP 4POS 2MM SMD")
      (fields (field (name "MANUFACTURER") "JST Sales America Inc."))
      (libsource (lib "RoboteX") (part "Header 4"))
    )
    (comp (ref "P3")
      (value "B4B-PH-SM4-TB(LF)(SN)")
      (footprint "B4B-PH-SM4-TB(LF)(SN)")
      (description "CONN HEADER PH TOP 4POS 2MM SMD")
      (fields (field (name "MANUFACTURER") "JST Sales America Inc."))
      (libsource (lib "RoboteX") (part "Header 4"))
    )
    (comp (ref "P4")
      (value "B4B-PH-SM4-TB(LF)(SN)")
      (footprint "B4B-PH-SM4-TB(LF)(SN)")
      (description "CONN HEADER PH TOP 4POS 2MM SMD")
      (fields (field (name "MANUFACTURER") "JST Sales America Inc."))
      (libsource (lib "RoboteX") (part "Header 4"))
    )
    (comp (ref "P5")
      (value "B2B-PH-SM4-TB(LF)(SN)")
      (footprint "B2B-PH-SM4-TB(LF)(SN)")
      (description "CONN HEADER PH TOP 2POS 2MM SMD")
      (fields (field (name "MANUFACTURER") "JST Sales America Inc."))
      (libsource (lib "RoboteX") (part "Header 2 POS"))
    )
    (comp (ref "P6")
      (value "B2B-PH-SM4-TB(LF)(SN)")
      (footprint "B2B-PH-SM4-TB(LF)(SN)")
      (description "CONN HEADER PH TOP 2POS 2MM SMD")
      (fields (field (name "MANUFACTURER") "JST Sales America Inc."))
      (libsource (lib "RoboteX") (part "Header 2 POS"))
    )
    (comp (ref "P7")
      (value "B2B-PH-SM4-TB(LF)(SN)")
      (footprint "B2B-PH-SM4-TB(LF)(SN)")
      (description "CONN HEADER PH TOP 2POS 2MM SMD")
      (fields (field (name "MANUFACTURER") "JST Sales America Inc."))
      (libsource (lib "RoboteX") (part "Header 2 POS"))
    )
    (comp (ref "P8")
      (value "Header 25X2")
      (footprint "HDR_2X25")
      (description "Header, 25-Pin, Dual row")
      (fields (field (name "PUBLISHER") "Altium Limited"))
      (libsource (lib "Miscellaneous Connectors") (part "Header 25X2"))
    )
    (comp (ref "P9")
      (value "JST VL 2POS Header")
      (footprint "JST-VL-2POS")
      (description "CONN HEADER 2POS VL SERIES TIN")
      (fields
        (field (name "MANUFACTURER") "JST Sales America Inc")
        (field (name "MANUFACTURER PART NUMBER") "B02P-VL")
      )
      (libsource (lib "RoboteX") (part "Header 2 POS"))
    )
    (comp (ref "P10")
      (value "B3B-PH-SM4-TB(LF)(SN)")
      (footprint "B3B-PH-SM4-TB(LF)(SN)")
      (description "CONN HEADER PH TOP 3POS 2MM SMD")
      (fields (field (name "MANUFACTURER") "JST Sales America Inc."))
      (libsource (lib "RoboteX") (part "Header 3"))
    )
    (comp (ref "P11")
      (value "0.1\" 2POS Header SNGL")
      (footprint "2 POS HEADER SINGLE ROW")
      (description "CONN HEADER 2POS .100\" SNGL TIN")
      (fields
        (field (name "MANUFACTURER") "Samtec Inc")
        (field (name "MANUFACTURER PART NUMBER") "TSW-150-08-T-S")
      )
      (libsource (lib "RoboteX") (part "Header 2 POS"))
    )
    (comp (ref "P12")
      (value "B3B-PH-SM4-TB(LF)(SN)")
      (footprint "B3B-PH-SM4-TB(LF)(SN)")
      (description "CONN HEADER PH TOP 3POS 2MM SMD")
      (fields (field (name "MANUFACTURER") "JST Sales America Inc."))
      (libsource (lib "RoboteX") (part "Header 3"))
    )
    (comp (ref "P13")
      (value "B2B-PH-SM4-TB(LF)(SN)")
      (footprint "B2B-PH-SM4-TB(LF)(SN)")
      (description "CONN HEADER PH TOP 2POS 2MM SMD")
      (fields (field (name "MANUFACTURER") "JST Sales America Inc."))
      (libsource (lib "RoboteX") (part "Header 2 POS"))
    )
    (comp (ref "P14")
      (value "B2B-PH-SM4-TB(LF)(SN)")
      (footprint "B2B-PH-SM4-TB(LF)(SN)")
      (description "CONN HEADER PH TOP 2POS 2MM SMD")
      (fields (field (name "MANUFACTURER") "JST Sales America Inc."))
      (libsource (lib "RoboteX") (part "Header 2 POS"))
    )
    (comp (ref "P15")
      (value "B2B-PH-SM4-TB(LF)(SN)")
      (footprint "B2B-PH-SM4-TB(LF)(SN)")
      (description "CONN HEADER PH TOP 2POS 2MM SMD")
      (fields (field (name "MANUFACTURER") "JST Sales America Inc."))
      (libsource (lib "RoboteX") (part "Header 2 POS"))
    )
    (comp (ref "P16")
      (value "B2B-PH-SM4-TB(LF)(SN)")
      (footprint "B2B-PH-SM4-TB(LF)(SN)")
      (description "CONN HEADER PH TOP 2POS 2MM SMD")
      (fields (field (name "MANUFACTURER") "JST Sales America Inc."))
      (libsource (lib "RoboteX") (part "Header 2 POS"))
    )
    (comp (ref "P17")
      (value "B3B-PH-SM4-TB(LF)(SN)")
      (footprint "B3B-PH-SM4-TB(LF)(SN)")
      (description "CONN HEADER PH TOP 3POS 2MM SMD")
      (fields (field (name "MANUFACTURER") "JST Sales America Inc."))
      (libsource (lib "RoboteX") (part "Header 3"))
    )
    (comp (ref "P18")
      (value "B2B-PH-SM4-TB(LF)(SN)")
      (footprint "B2B-PH-SM4-TB(LF)(SN)")
      (description "CONN HEADER PH TOP 2POS 2MM SMD")
      (fields (field (name "MANUFACTURER") "JST Sales America Inc."))
      (libsource (lib "") (part "Header 2 POS_1"))
    )
    (comp (ref "P19")
      (value "B2B-PH-SM4-TB(LF)(SN)")
      (footprint "B2B-PH-SM4-TB(LF)(SN)")
      (description "CONN HEADER PH TOP 2POS 2MM SMD")
      (fields (field (name "MANUFACTURER") "JST Sales America Inc."))
      (libsource (lib "RoboteX") (part "Header 2 POS"))
    )
    (comp (ref "P20")
      (value "B2B-PH-SM4-TB(LF)(SN)")
      (footprint "B2B-PH-SM4-TB(LF)(SN)")
      (description "CONN HEADER PH TOP 2POS 2MM SMD")
      (fields (field (name "MANUFACTURER") "JST Sales America Inc."))
      (libsource (lib "RoboteX") (part "Header 2 POS"))
    )
    (comp (ref "P21")
      (value "B4B-PH-SM4-TB(LF)(SN)")
      (footprint "B4B-PH-SM4-TB(LF)(SN)")
      (description "CONN HEADER PH TOP 4POS 2MM SMD")
      (fields (field (name "MANUFACTURER") "JST Sales America Inc."))
      (libsource (lib "") (part "Header 4_1"))
    )
    (comp (ref "P22")
      (value "B3B-PH-SM4-TB(LF)(SN)")
      (footprint "B3B-PH-SM4-TB(LF)(SN)")
      (description "CONN HEADER PH TOP 3POS 2MM SMD")
      (fields (field (name "MANUFACTURER") "JST Sales America Inc."))
      (libsource (lib "RoboteX") (part "Header 3"))
    )
    (comp (ref "P23")
      (value "B2B-PH-SM4-TB(LF)(SN)")
      (footprint "B2B-PH-SM4-TB(LF)(SN)")
      (description "CONN HEADER PH TOP 2POS 2MM SMD")
      (fields (field (name "MANUFACTURER") "JST Sales America Inc."))
      (libsource (lib "RoboteX") (part "Header 2 POS"))
    )
    (comp (ref "P24")
      (value "B4B-PH-SM4-TB(LF)(SN)")
      (footprint "B4B-PH-SM4-TB(LF)(SN)")
      (description "CONN HEADER PH TOP 4POS 2MM SMD")
      (fields (field (name "MANUFACTURER") "JST Sales America Inc."))
      (libsource (lib "") (part "Header 4_1"))
    )
    (comp (ref "P25")
      (value "B4B-PH-SM4-TB(LF)(SN)")
      (footprint "B4B-PH-SM4-TB(LF)(SN)")
      (description "CONN HEADER PH TOP 4POS 2MM SMD")
      (fields (field (name "MANUFACTURER") "JST Sales America Inc."))
      (libsource (lib "") (part "Header 4_1"))
    )
    (comp (ref "P26")
      (value "B3B-PH-SM4-TB(LF)(SN)")
      (footprint "B3B-PH-SM4-TB(LF)(SN)")
      (description "CONN HEADER PH TOP 3POS 2MM SMD")
      (fields (field (name "MANUFACTURER") "JST Sales America Inc."))
      (libsource (lib "") (part "Header 3_1"))
    )
    (comp (ref "P27")
      (value "Header 10X2H")
      (footprint "HDR_2X10")
      (description "Header, 10-Pin, Dual row, Right Angle")
      (fields
        (field (name "MANUFACTURER PART NUMBER") "AWHW 10G-0202-T")
        (field (name "MANUFACTURER") "Assmann WSW Components")
        (field (name "PUBLISHER") "Altium Limited")
      )
      (libsource (lib "Miscellaneous Connectors") (part "Header 10X2H"))
    )
    (comp (ref "P28")
      (value "B2B-PH-SM4-TB(LF)(SN)")
      (footprint "B2B-PH-SM4-TB(LF)(SN)")
      (description "CONN HEADER PH TOP 2POS 2MM SMD")
      (fields (field (name "MANUFACTURER") "JST Sales America Inc."))
      (libsource (lib "RoboteX") (part "Header 2 POS"))
    )
    (comp (ref "P29")
      (value "B2B-PH-SM4-TB(LF)(SN)")
      (footprint "B2B-PH-SM4-TB(LF)(SN)")
      (description "CONN HEADER PH TOP 2POS 2MM SMD")
      (fields (field (name "MANUFACTURER") "JST Sales America Inc."))
      (libsource (lib "RoboteX") (part "Header 2 POS"))
    )
    (comp (ref "P30")
      (value "B2B-PH-SM4-TB(LF)(SN)")
      (footprint "B2B-PH-SM4-TB(LF)(SN)")
      (description "CONN HEADER PH TOP 2POS 2MM SMD")
      (fields (field (name "MANUFACTURER") "JST Sales America Inc."))
      (libsource (lib "") (part "Header 2 POS_1"))
    )
    (comp (ref "P31")
      (value "B4B-PH-SM4-TB(LF)(SN)")
      (footprint "B4B-PH-SM4-TB(LF)(SN)")
      (description "CONN HEADER PH TOP 4POS 2MM SMD")
      (fields (field (name "MANUFACTURER") "JST Sales America Inc."))
      (libsource (lib "") (part "Header 4_1"))
    )
    (comp (ref "Q1")
      (value "IRF9310TRPBF")
      (footprint "SOIC-SN8_M")
      (description "MOSFET P-CH 30V 20A 8-SOIC")
      (fields (field (name "MANUFACTURER") "International Rectifier"))
      (libsource (lib "RoboteX") (part "MOSFET_P_8_PADS"))
    )
    (comp (ref "Q2")
      (value "IRF9310TRPBF")
      (footprint "SOIC-SN8_M")
      (description "MOSFET P-CH 30V 20A 8-SOIC")
      (fields (field (name "MANUFACTURER") "International Rectifier"))
      (libsource (lib "RoboteX") (part "MOSFET_P_8_PADS"))
    )
    (comp (ref "Q3")
      (value "AO3400A N道沟 X0YV1T SOT-23")
      (footprint "SOT-23-3L")
      (description "MOS(场效应管)")
      (libsource (lib "Miscellaneous Devices LC") (part "AO3400A N道沟 X0YV1T SOT-23"))
    )
    (comp (ref "Q4")
      (value "IRF9310TRPBF")
      (footprint "SOIC-SN8_M")
      (description "MOSFET P-CH 30V 20A 8-SOIC")
      (fields (field (name "MANUFACTURER") "International Rectifier"))
      (libsource (lib "RoboteX") (part "MOSFET_P_8_PADS"))
    )
    (comp (ref "Q5")
      (value "AO3400A N道沟 X0YV1T SOT-23")
      (footprint "SOT-23-3L")
      (description "MOS(场效应管)")
      (libsource (lib "Miscellaneous Devices LC") (part "AO3400A N道沟 X0YV1T SOT-23"))
    )
    (comp (ref "Q6")
      (value "AO3400A N道沟 X0YV1T SOT-23")
      (footprint "SOT-23-3L")
      (description "MOS(场效应管)")
      (libsource (lib "Miscellaneous Devices LC") (part "AO3400A N道沟 X0YV1T SOT-23"))
    )
    (comp (ref "Q7")
      (value "IRF9310TRPBF")
      (footprint "SOIC-SN8_M")
      (description "MOSFET P-CH 30V 20A 8-SOIC")
      (fields (field (name "MANUFACTURER") "International Rectifier"))
      (libsource (lib "RoboteX") (part "MOSFET_P_8_PADS"))
    )
    (comp (ref "Q8")
      (value "AO3400A N道沟 X0YV1T SOT-23")
      (footprint "SOT-23-3L")
      (description "MOS(场效应管)")
      (libsource (lib "Miscellaneous Devices LC") (part "AO3400A N道沟 X0YV1T SOT-23"))
    )
    (comp (ref "Q9")
      (value "AO3400A N道沟 X0YV1T SOT-23")
      (footprint "SOT-23-3L")
      (description "MOS(场效应管)")
      (libsource (lib "Miscellaneous Devices LC") (part "AO3400A N道沟 X0YV1T SOT-23"))
    )
    (comp (ref "R1")
      (value "49.9")
      (footprint "RES0603N")
      (description "RES 49.9 OHM 1/10W 1% 0603 SMD")
      (fields
        (field (name "MANUFACTURER") "Yageo")
        (field (name "MANUFACTURER PART NUMBER") "RC0603FR-0749R9L")
      )
      (libsource (lib "RoboteX") (part "Res"))
    )
    (comp (ref "R2")
      (value "49.9")
      (footprint "RES0603N")
      (description "RES 49.9 OHM 1/10W 1% 0603 SMD")
      (fields
        (field (name "MANUFACTURER") "Yageo")
        (field (name "MANUFACTURER PART NUMBER") "RC0603FR-0749R9L")
      )
      (libsource (lib "RoboteX") (part "Res"))
    )
    (comp (ref "R3")
      (value "49.9")
      (footprint "RES0603N")
      (description "RES 49.9 OHM 1/10W 1% 0603 SMD")
      (fields
        (field (name "MANUFACTURER") "Yageo")
        (field (name "MANUFACTURER PART NUMBER") "RC0603FR-0749R9L")
      )
      (libsource (lib "RoboteX") (part "Res"))
    )
    (comp (ref "R4")
      (value "49.9")
      (footprint "RES0603N")
      (description "RES 49.9 OHM 1/10W 1% 0603 SMD")
      (fields
        (field (name "MANUFACTURER") "Yageo")
        (field (name "MANUFACTURER PART NUMBER") "RC0603FR-0749R9L")
      )
      (libsource (lib "RoboteX") (part "Res"))
    )
    (comp (ref "R5")
      (value "10k")
      (footprint "RES0603N")
      (description "RES 10K OHM 1/10W 1% 0603 SMD")
      (fields
        (field (name "MANUFACTURER") "Stackpole Electronics Inc")
        (field (name "MANUFACTURER PART NUMBER") "RMCF0603FT10K0")
      )
      (libsource (lib "RoboteX") (part "Res"))
    )
    (comp (ref "R6")
      (value "12k")
      (footprint "RES0603N")
      (description "RES 12K OHM 1/10W 1% 0603 SMD")
      (fields
        (field (name "MANUFACTURER") "Stackpole Electronics")
        (field (name "MANUFACTURER PART NUMBER") "RMCF0603FT12K0")
      )
      (libsource (lib "RoboteX") (part "Res"))
    )
    (comp (ref "R7")
      (value "12k")
      (footprint "RES0603N")
      (description "RES 12K OHM 1/10W 1% 0603 SMD")
      (fields
        (field (name "MANUFACTURER") "Stackpole Electronics")
        (field (name "MANUFACTURER PART NUMBER") "RMCF0603FT12K0")
      )
      (libsource (lib "RoboteX") (part "Res"))
    )
    (comp (ref "R8")
      (value "1M")
      (footprint "RES0402N")
      (description "RES 1M OHM 1/16W 1% 0402 SMD")
      (fields
        (field (name "MANUFACTURER") "Stackpole Electronics")
        (field (name "MANUFACTURER PART NUMBER") "RMCF0402FT1M00")
      )
      (libsource (lib "RoboteX") (part "Res"))
    )
    (comp (ref "R9")
      (value "0")
      (footprint "RES0603N")
      (description "RES 0.0 OHM 1/10W 0603 SMD")
      (fields
        (field (name "MANUFACTURER") "Stackpole Electronics Inc")
        (field (name "MANUFACTURER PART NUMBER") "RMCF0603ZT0R00")
      )
      (libsource (lib "RoboteX") (part "Res"))
    )
    (comp (ref "R10")
      (value "10k")
      (footprint "RES0603N")
      (description "RES 10K OHM 1/10W 1% 0603 SMD")
      (fields
        (field (name "MANUFACTURER") "Stackpole Electronics Inc")
        (field (name "MANUFACTURER PART NUMBER") "RMCF0603FT10K0")
      )
      (libsource (lib "RoboteX") (part "Res"))
    )
    (comp (ref "R11")
      (value "10k")
      (footprint "RES0603N")
      (description "RES 10K OHM 1/10W 1% 0603 SMD")
      (fields
        (field (name "MANUFACTURER") "Stackpole Electronics Inc")
        (field (name "MANUFACTURER PART NUMBER") "RMCF0603FT10K0")
      )
      (libsource (lib "RoboteX") (part "Res"))
    )
    (comp (ref "R12")
      (value "1.0k")
      (footprint "RES0603N")
      (description "RES 1K OHM 1/10W 1% 0603 SMD")
      (fields
        (field (name "MANUFACTURER") "Stackpole Electronics Inc")
        (field (name "MANUFACTURER PART NUMBER") "RMCF0603FT1K00")
      )
      (libsource (lib "RoboteX") (part "Res"))
    )
    (comp (ref "R13")
      (value "1.0k")
      (footprint "RES0603N")
      (description "RES 1K OHM 1/10W 1% 0603 SMD")
      (fields
        (field (name "MANUFACTURER") "Stackpole Electronics Inc")
        (field (name "MANUFACTURER PART NUMBER") "RMCF0603FT1K00")
      )
      (libsource (lib "RoboteX") (part "Res"))
    )
    (comp (ref "R14")
      (value "1.0k")
      (footprint "RES0603N")
      (description "RES 1K OHM 1/10W 1% 0603 SMD")
      (fields
        (field (name "MANUFACTURER") "Stackpole Electronics Inc")
        (field (name "MANUFACTURER PART NUMBER") "RMCF0603FT1K00")
      )
      (libsource (lib "RoboteX") (part "Res"))
    )
    (comp (ref "R15")
      (value "120")
      (footprint "RES0603N")
      (description "RES SMD 120 OHM 1% 1/10W 0603")
      (fields
        (field (name "MANUFACTURER") "Panasonic Electronic Components")
        (field (name "MANUFACTURER PART NUMBER") "ERJ-3EKF1200V")
      )
      (libsource (lib "RoboteX") (part "Res"))
    )
    (comp (ref "R16")
      (value "5.76k")
      (footprint "RES0402N")
      (description "RES 5.76K OHM 1/10W 1% 0402 SMD")
      (fields
        (field (name "MANUFACTURER") "Panasonic - ECG")
        (field (name "MANUFACTURER PART NUMBER") "ERJ-2RKF5761X")
      )
      (libsource (lib "RoboteX") (part "Res"))
    )
    (comp (ref "R17")
      (value "100k")
      (footprint "RES0603N")
      (description "RES 100K OHM 1/10W 1% 0603 SMD")
      (fields
        (field (name "MANUFACTURER") "Stackpole Electronics Inc")
        (field (name "MANUFACTURER PART NUMBER") "RMCF0603FT100K")
      )
      (libsource (lib "RoboteX") (part "Res"))
    )
    (comp (ref "R18")
      (value "51k")
      (footprint "RES0402N")
      (description "RES 51.0K OHM 1/10W 1% 0402 SMD")
      (fields
        (field (name "MANUFACTURER") "Panasonic - ECG")
        (field (name "MANUFACTURER PART NUMBER") "ERJ-2RKF5102X")
      )
      (libsource (lib "RoboteX") (part "Res"))
    )
    (comp (ref "R19")
      (value "100k")
      (footprint "RES0603N")
      (description "RES 100K OHM 1/10W 1% 0603 SMD")
      (fields
        (field (name "MANUFACTURER") "Stackpole Electronics Inc")
        (field (name "MANUFACTURER PART NUMBER") "RMCF0603FT100K")
      )
      (libsource (lib "RoboteX") (part "Res"))
    )
    (comp (ref "R20")
      (value "42.2k")
      (footprint "RES0402N")
      (description "RES 42.2K OHM 1/16W 1% 0402 SMD")
      (fields
        (field (name "MANUFACTURER") "Yageo")
        (field (name "MANUFACTURER PART NUMBER") "RC0402FR-0742K2L")
      )
      (libsource (lib "RoboteX") (part "Res"))
    )
    (comp (ref "R21")
      (value "2.7k")
      (footprint "RES0603N")
      (description "RES 2.70K OHM 1/10W 1% 0603 SMD")
      (fields
        (field (name "MANUFACTURER") "Panasonic - ECG")
        (field (name "MANUFACTURER PART NUMBER") "ERJ-3EKF2701V")
      )
      (libsource (lib "RoboteX") (part "Res"))
    )
    (comp (ref "R22")
      (value "0(NC)")
      (footprint "RES0603N")
      (description "RES 0.0 OHM 1/10W 0603 SMD")
      (fields
        (field (name "MANUFACTURER") "Stackpole Electronics Inc")
        (field (name "MANUFACTURER PART NUMBER") "RMCF0603ZT0R00")
      )
      (libsource (lib "RoboteX") (part "Res"))
    )
    (comp (ref "R23")
      (value "2.7k")
      (footprint "RES0603N")
      (description "RES 2.70K OHM 1/10W 1% 0603 SMD")
      (fields
        (field (name "MANUFACTURER") "Panasonic - ECG")
        (field (name "MANUFACTURER PART NUMBER") "ERJ-3EKF2701V")
      )
      (libsource (lib "RoboteX") (part "Res"))
    )
    (comp (ref "R24")
      (value "0")
      (footprint "RES0603N")
      (description "RES 0.0 OHM 1/10W 0603 SMD")
      (fields
        (field (name "MANUFACTURER") "Stackpole Electronics Inc")
        (field (name "MANUFACTURER PART NUMBER") "RMCF0603ZT0R00")
      )
      (libsource (lib "RoboteX") (part "Res"))
    )
    (comp (ref "R25")
      (value "43.0k")
      (footprint "RES0603N")
      (description "RES 43.0K OHM 1/10W 1% 0603 SMD")
      (fields
        (field (name "MANUFACTURER") "Panasonic - ECG")
        (field (name "MANUFACTURER PART NUMBER") "ERJ-3EKF4302V")
      )
      (libsource (lib "RoboteX") (part "Res"))
    )
    (comp (ref "R26")
      (value "20k")
      (footprint "RES0603N")
      (description "RES 20K OHM 1/10W 1% 0603 SMD")
      (fields
        (field (name "MANUFACTURER") "Stackpole Electronics")
        (field (name "MANUFACTURER PART NUMBER") "RMCF0603FT20K0")
      )
      (libsource (lib "RoboteX") (part "Res"))
    )
    (comp (ref "R27")
      (value "100k")
      (footprint "RES0603N")
      (description "RES 100K OHM 1/10W 1% 0603 SMD")
      (fields
        (field (name "MANUFACTURER") "Stackpole Electronics Inc")
        (field (name "MANUFACTURER PART NUMBER") "RMCF0603FT100K")
      )
      (libsource (lib "RoboteX") (part "Res"))
    )
    (comp (ref "R28")
      (value "100k")
      (footprint "RES0603N")
      (description "RES 100K OHM 1/10W 1% 0603 SMD")
      (fields
        (field (name "MANUFACTURER") "Stackpole Electronics Inc")
        (field (name "MANUFACTURER PART NUMBER") "RMCF0603FT100K")
      )
      (libsource (lib "RoboteX") (part "Res"))
    )
    (comp (ref "R29")
      (value "30k")
      (footprint "RES0603N")
      (description "RES 30K OHM 1/10W 1% 0603 SMD")
      (fields
        (field (name "MANUFACTURER") "Stackpole Electronics")
        (field (name "MANUFACTURER PART NUMBER") "RMCF0603FT30K0")
      )
      (libsource (lib "RoboteX") (part "Res"))
    )
    (comp (ref "R30")
      (value "42.2k")
      (footprint "RES0402N")
      (description "RES 42.2K OHM 1/16W 1% 0402 SMD")
      (fields
        (field (name "MANUFACTURER") "Yageo")
        (field (name "MANUFACTURER PART NUMBER") "RC0402FR-0742K2L")
      )
      (libsource (lib "RoboteX") (part "Res"))
    )
    (comp (ref "R31")
      (value "1.0k")
      (footprint "RES0603N")
      (description "RES 1K OHM 1/10W 1% 0603 SMD")
      (fields
        (field (name "MANUFACTURER") "Stackpole Electronics Inc")
        (field (name "MANUFACTURER PART NUMBER") "RMCF0603FT1K00")
      )
      (libsource (lib "RoboteX") (part "Res"))
    )
    (comp (ref "R32")
      (value "51k")
      (footprint "RES0402N")
      (description "RES 51.0K OHM 1/10W 1% 0402 SMD")
      (fields
        (field (name "MANUFACTURER") "Panasonic - ECG")
        (field (name "MANUFACTURER PART NUMBER") "ERJ-2RKF5102X")
      )
      (libsource (lib "RoboteX") (part "Res"))
    )
    (comp (ref "R33")
      (value "0")
      (footprint "RES0805N")
      (description "RES 0.0 OHM 1/8W 0805 SMD")
      (fields
        (field (name "MANUFACTURER") "Stackpole Electronics Inc")
        (field (name "MANUFACTURER PART NUMBER") "RMCF0805ZT0R00")
      )
      (libsource (lib "RoboteX") (part "Res"))
    )
    (comp (ref "R34")
      (value "5.76k")
      (footprint "RES0603N")
      (description "RES TF 5.76K OHM 1% 0.1W 0603")
      (fields
        (field (name "MANUFACTURER") "Stackpole Electronics")
        (field (name "MANUFACTURER PART NUMBER") "RMCF0603FT5K76")
      )
      (libsource (lib "RoboteX") (part "Res"))
    )
    (comp (ref "R35")
      (value "2.2k")
      (footprint "RES0402N")
      (description "RES 2.20K OHM 1/16W 1% 0402 SMD")
      (fields
        (field (name "MANUFACTURER") "Yageo")
        (field (name "MANUFACTURER PART NUMBER") "RC0402FR-072K2L")
      )
      (libsource (lib "RoboteX") (part "Res"))
    )
    (comp (ref "R36")
      (value "698")
      (footprint "RES0805N")
      (description "RES 698 OHM 1/8W 1% 0805 SMD")
      (fields
        (field (name "MANUFACTURER") "Rohm Semiconductor")
        (field (name "MANUFACTURER PART NUMBER") "MCR10EZPF6980")
      )
      (libsource (lib "RoboteX") (part "Res"))
    )
    (comp (ref "R37")
      (value "698")
      (footprint "RES0805N")
      (description "RES 698 OHM 1/8W 1% 0805 SMD")
      (fields
        (field (name "MANUFACTURER") "Rohm Semiconductor")
        (field (name "MANUFACTURER PART NUMBER") "MCR10EZPF6980")
      )
      (libsource (lib "RoboteX") (part "Res"))
    )
    (comp (ref "R38")
      (value "22")
      (footprint "RES0402N")
      (description "RES 22 OHM 1/10W 1% 0402 SMD")
      (fields
        (field (name "MANUFACTURER") "Panasonic")
        (field (name "MANUFACTURER PART NUMBER") "ERJ-2RKF22R0X")
      )
      (libsource (lib "RoboteX") (part "Res"))
    )
    (comp (ref "R39")
      (value "22")
      (footprint "RES0402N")
      (description "RES 22 OHM 1/10W 1% 0402 SMD")
      (fields
        (field (name "MANUFACTURER") "Panasonic")
        (field (name "MANUFACTURER PART NUMBER") "ERJ-2RKF22R0X")
      )
      (libsource (lib "RoboteX") (part "Res"))
    )
    (comp (ref "R40")
      (value "1.5k")
      (footprint "RES0402N")
      (description "RES 1.5K OHM 1/16W 1% 0402 SMD")
      (fields
        (field (name "MANUFACTURER") "Stackpole Electronics")
        (field (name "MANUFACTURER PART NUMBER") "RMCF0402FT1K50")
      )
      (libsource (lib "RoboteX") (part "Res"))
    )
    (comp (ref "R41")
      (value "0")
      (footprint "RES0402N")
      (description "RES 0.0 OHM 1/16W 0402 SMD")
      (fields
        (field (name "MANUFACTURER") "Stackpole Electronics")
        (field (name "MANUFACTURER PART NUMBER") "RMCF0402ZT0R00")
      )
      (libsource (lib "RoboteX") (part "Res"))
    )
    (comp (ref "R42")
      (value "1M")
      (footprint "RES0402N")
      (description "RES 1M OHM 1/16W 1% 0402 SMD")
      (fields
        (field (name "MANUFACTURER") "Stackpole Electronics")
        (field (name "MANUFACTURER PART NUMBER") "RMCF0402FT1M00")
      )
      (libsource (lib "RoboteX") (part "Res"))
    )
    (comp (ref "R43")
      (value "3.16k")
      (footprint "RES0402N")
      (description "RES 3.16K OHM 1/10W 1% 0402 SMD")
      (fields
        (field (name "MANUFACTURER") "Panasonic")
        (field (name "MANUFACTURER PART NUMBER") "ERJ-2RKF3161X")
      )
      (libsource (lib "RoboteX") (part "Res"))
    )
    (comp (ref "R44")
      (value "3.16k")
      (footprint "RES0402N")
      (description "RES 3.16K OHM 1/10W 1% 0402 SMD")
      (fields
        (field (name "MANUFACTURER") "Panasonic")
        (field (name "MANUFACTURER PART NUMBER") "ERJ-2RKF3161X")
      )
      (libsource (lib "RoboteX") (part "Res"))
    )
    (comp (ref "R45")
      (value "3.16k")
      (footprint "RES0402N")
      (description "RES 3.16K OHM 1/10W 1% 0402 SMD")
      (fields
        (field (name "MANUFACTURER") "Panasonic")
        (field (name "MANUFACTURER PART NUMBER") "ERJ-2RKF3161X")
      )
      (libsource (lib "RoboteX") (part "Res"))
    )
    (comp (ref "R46")
      (value "3.16k")
      (footprint "RES0402N")
      (description "RES 3.16K OHM 1/10W 1% 0402 SMD")
      (fields
        (field (name "MANUFACTURER") "Panasonic")
        (field (name "MANUFACTURER PART NUMBER") "ERJ-2RKF3161X")
      )
      (libsource (lib "RoboteX") (part "Res"))
    )
    (comp (ref "R47")
      (value "0")
      (footprint "RES0402N")
      (description "RES 0.0 OHM 1/16W 0402 SMD")
      (fields
        (field (name "MANUFACTURER") "Stackpole Electronics")
        (field (name "MANUFACTURER PART NUMBER") "RMCF0402ZT0R00")
      )
      (libsource (lib "RoboteX") (part "Res"))
    )
    (comp (ref "R48")
      (value "2.2k")
      (footprint "RES0402N")
      (description "RES 2.20K OHM 1/16W 1% 0402 SMD")
      (fields
        (field (name "MANUFACTURER") "Yageo")
        (field (name "MANUFACTURER PART NUMBER") "RC0402FR-072K2L")
      )
      (libsource (lib "RoboteX") (part "Res"))
    )
    (comp (ref "R49")
      (value "49.9k")
      (footprint "RES0603N")
      (description "RES 49.9K OHM 1/10W 1% 0603 SMD")
      (fields
        (field (name "MANUFACTURER") "Yageo")
        (field (name "MANUFACTURER PART NUMBER") "RC0603FR-0749K9L")
      )
      (libsource (lib "RoboteX") (part "Res"))
    )
    (comp (ref "R50")
      (value "10k")
      (footprint "RES0603N")
      (description "RES 10K OHM 1/10W 1% 0603 SMD")
      (fields
        (field (name "MANUFACTURER") "Stackpole Electronics Inc")
        (field (name "MANUFACTURER PART NUMBER") "RMCF0603FT10K0")
      )
      (libsource (lib "RoboteX") (part "Res"))
    )
    (comp (ref "R51")
      (value "Res 0402")
      (footprint "RES0402N")
      (description "RES 10K OHM 1/16W 1% 0402 SMD")
      (fields
        (field (name "ALTIUM_VALUE") "10K")
        (field (name "MANUFACTURER") "Stackpole Electronics")
        (field (name "MANUFACTURER PART NUMBER") "RMCF0402FT10K0")
      )
      (libsource (lib "RoboteX") (part "Res"))
    )
    (comp (ref "R52")
      (value "2.2k")
      (footprint "RES0402N")
      (description "RES 2.20K OHM 1/16W 1% 0402 SMD")
      (fields
        (field (name "MANUFACTURER") "Yageo")
        (field (name "MANUFACTURER PART NUMBER") "RC0402FR-072K2L")
      )
      (libsource (lib "RoboteX") (part "Res"))
    )
    (comp (ref "R53")
      (value "Res 0402")
      (footprint "RES0402N")
      (description "RES 10K OHM 1/16W 1% 0402 SMD")
      (fields
        (field (name "ALTIUM_VALUE") "10K")
        (field (name "MANUFACTURER") "Stackpole Electronics")
        (field (name "MANUFACTURER PART NUMBER") "RMCF0402FT10K0")
      )
      (libsource (lib "RoboteX") (part "Res"))
    )
    (comp (ref "R54")
      (value "12k")
      (footprint "RES0603N")
      (description "RES 12K OHM 1/10W 1% 0603 SMD")
      (fields
        (field (name "MANUFACTURER") "Stackpole Electronics")
        (field (name "MANUFACTURER PART NUMBER") "RMCF0603FT12K0")
      )
      (libsource (lib "RoboteX") (part "Res"))
    )
    (comp (ref "R55")
      (value "10k")
      (footprint "RES0603N")
      (description "RES 10K OHM 1/10W 1% 0603 SMD")
      (fields
        (field (name "MANUFACTURER") "Stackpole Electronics Inc")
        (field (name "MANUFACTURER PART NUMBER") "RMCF0603FT10K0")
      )
      (libsource (lib "RoboteX") (part "Res"))
    )
    (comp (ref "R56")
      (value "12k")
      (footprint "RES0603N")
      (description "RES 12K OHM 1/10W 1% 0603 SMD")
      (fields
        (field (name "MANUFACTURER") "Stackpole Electronics")
        (field (name "MANUFACTURER PART NUMBER") "RMCF0603FT12K0")
      )
      (libsource (lib "RoboteX") (part "Res"))
    )
    (comp (ref "R57")
      (value "Res 0402")
      (footprint "RES0402N")
      (description "RES 100K OHM 1/16W 1% 0402 SMD")
      (fields
        (field (name "ALTIUM_VALUE") "100k")
        (field (name "MANUFACTURER") "Stackpole Electronics")
        (field (name "MANUFACTURER PART NUMBER") "RMCF0402FT100K")
      )
      (libsource (lib "RoboteX") (part "Res"))
    )
    (comp (ref "R58")
      (value "Res 0402")
      (footprint "RES0402N")
      (description "RES 10K OHM 1/16W 1% 0402 SMD")
      (fields
        (field (name "ALTIUM_VALUE") "10K")
        (field (name "MANUFACTURER") "Stackpole Electronics")
        (field (name "MANUFACTURER PART NUMBER") "RMCF0402FT10K0")
      )
      (libsource (lib "RoboteX") (part "Res"))
    )
    (comp (ref "R59")
      (value "10k")
      (footprint "RES0603N")
      (description "RES 10K OHM 1/10W 1% 0603 SMD")
      (fields
        (field (name "MANUFACTURER") "Stackpole Electronics Inc")
        (field (name "MANUFACTURER PART NUMBER") "RMCF0603FT10K0")
      )
      (libsource (lib "RoboteX") (part "Res"))
    )
    (comp (ref "R60")
      (value "Res 0402")
      (footprint "RES0402N")
      (description "RES 10K OHM 1/16W 1% 0402 SMD")
      (fields
        (field (name "ALTIUM_VALUE") "10K")
        (field (name "MANUFACTURER") "Stackpole Electronics")
        (field (name "MANUFACTURER PART NUMBER") "RMCF0402FT10K0")
      )
      (libsource (lib "RoboteX") (part "Res"))
    )
    (comp (ref "R61")
      (value "10k")
      (footprint "RES0603N")
      (description "RES 10K OHM 1/10W 1% 0603 SMD")
      (fields
        (field (name "MANUFACTURER") "Stackpole Electronics Inc")
        (field (name "MANUFACTURER PART NUMBER") "RMCF0603FT10K0")
      )
      (libsource (lib "RoboteX") (part "Res"))
    )
    (comp (ref "R62")
      (value "20k")
      (footprint "RES0603N")
      (description "RES 20K OHM 1/10W 1% 0603 SMD")
      (fields
        (field (name "MANUFACTURER") "Stackpole Electronics")
        (field (name "MANUFACTURER PART NUMBER") "RMCF0603FT20K0")
      )
      (libsource (lib "RoboteX") (part "Res"))
    )
    (comp (ref "R63")
      (value "10k")
      (footprint "RES0603N")
      (description "RES 10K OHM 1/10W 1% 0603 SMD")
      (fields
        (field (name "MANUFACTURER") "Stackpole Electronics Inc")
        (field (name "MANUFACTURER PART NUMBER") "RMCF0603FT10K0")
      )
      (libsource (lib "RoboteX") (part "Res"))
    )
    (comp (ref "R64")
      (value "1.0k")
      (footprint "RES0603N")
      (description "RES 1K OHM 1/10W 1% 0603 SMD")
      (fields
        (field (name "MANUFACTURER") "Stackpole Electronics Inc")
        (field (name "MANUFACTURER PART NUMBER") "RMCF0603FT1K00")
      )
      (libsource (lib "RoboteX") (part "Res"))
    )
    (comp (ref "R65")
      (value "0")
      (footprint "RES0805N")
      (description "RES 0.0 OHM 1/8W 0805 SMD")
      (fields
        (field (name "MANUFACTURER") "Stackpole Electronics Inc")
        (field (name "MANUFACTURER PART NUMBER") "RMCF0805ZT0R00")
      )
      (libsource (lib "RoboteX") (part "Res"))
    )
    (comp (ref "R66")
      (value "0")
      (footprint "RES0805N")
      (description "RES 0.0 OHM 1/8W 0805 SMD")
      (fields
        (field (name "MANUFACTURER") "Stackpole Electronics Inc")
        (field (name "MANUFACTURER PART NUMBER") "RMCF0805ZT0R00")
      )
      (libsource (lib "RoboteX") (part "Res"))
    )
    (comp (ref "R67")
      (value "10k")
      (footprint "RES0603N")
      (description "RES 10K OHM 1/10W 1% 0603 SMD")
      (fields
        (field (name "MANUFACTURER") "Stackpole Electronics Inc")
        (field (name "MANUFACTURER PART NUMBER") "RMCF0603FT10K0")
      )
      (libsource (lib "RoboteX") (part "Res"))
    )
    (comp (ref "R68")
      (value "1.0k")
      (footprint "RES0603N")
      (description "RES 1K OHM 1/10W 1% 0603 SMD")
      (fields
        (field (name "MANUFACTURER") "Stackpole Electronics Inc")
        (field (name "MANUFACTURER PART NUMBER") "RMCF0603FT1K00")
      )
      (libsource (lib "RoboteX") (part "Res"))
    )
    (comp (ref "R69")
      (value "10k")
      (footprint "RES0603N")
      (description "RES 10K OHM 1/10W 1% 0603 SMD")
      (fields
        (field (name "MANUFACTURER") "Stackpole Electronics Inc")
        (field (name "MANUFACTURER PART NUMBER") "RMCF0603FT10K0")
      )
      (libsource (lib "RoboteX") (part "Res"))
    )
    (comp (ref "R70")
      (value "10k")
      (footprint "RES0603N")
      (description "RES 10K OHM 1/10W 1% 0603 SMD")
      (fields
        (field (name "MANUFACTURER") "Stackpole Electronics Inc")
        (field (name "MANUFACTURER PART NUMBER") "RMCF0603FT10K0")
      )
      (libsource (lib "RoboteX") (part "Res"))
    )
    (comp (ref "R71")
      (value "1.0k")
      (footprint "RES0603N")
      (description "RES 1K OHM 1/10W 1% 0603 SMD")
      (fields
        (field (name "MANUFACTURER") "Stackpole Electronics Inc")
        (field (name "MANUFACTURER PART NUMBER") "RMCF0603FT1K00")
      )
      (libsource (lib "RoboteX") (part "Res"))
    )
    (comp (ref "R72")
      (value "10k")
      (footprint "RES0603N")
      (description "RES 10K OHM 1/10W 1% 0603 SMD")
      (fields
        (field (name "MANUFACTURER") "Stackpole Electronics Inc")
        (field (name "MANUFACTURER PART NUMBER") "RMCF0603FT10K0")
      )
      (libsource (lib "RoboteX") (part "Res"))
    )
    (comp (ref "R73")
      (value "1.0k")
      (footprint "RES0603N")
      (description "RES 1K OHM 1/10W 1% 0603 SMD")
      (fields
        (field (name "MANUFACTURER") "Stackpole Electronics Inc")
        (field (name "MANUFACTURER PART NUMBER") "RMCF0603FT1K00")
      )
      (libsource (lib "RoboteX") (part "Res"))
    )
    (comp (ref "R74")
      (value "10k")
      (footprint "RES0603N")
      (description "RES 10K OHM 1/10W 1% 0603 SMD")
      (fields
        (field (name "MANUFACTURER") "Stackpole Electronics Inc")
        (field (name "MANUFACTURER PART NUMBER") "RMCF0603FT10K0")
      )
      (libsource (lib "RoboteX") (part "Res"))
    )
    (comp (ref "R75")
      (value "10k")
      (footprint "RES0603N")
      (description "RES 10K OHM 1/10W 1% 0603 SMD")
      (fields
        (field (name "MANUFACTURER") "Stackpole Electronics Inc")
        (field (name "MANUFACTURER PART NUMBER") "RMCF0603FT10K0")
      )
      (libsource (lib "RoboteX") (part "Res"))
    )
    (comp (ref "R76")
      (value "1.0k")
      (footprint "RES0603N")
      (description "RES 1K OHM 1/10W 1% 0603 SMD")
      (fields
        (field (name "MANUFACTURER") "Stackpole Electronics Inc")
        (field (name "MANUFACTURER PART NUMBER") "RMCF0603FT1K00")
      )
      (libsource (lib "RoboteX") (part "Res"))
    )
    (comp (ref "R77")
      (value "0")
      (footprint "RES0603N")
      (description "RES 0.0 OHM 1/10W 0603 SMD")
      (fields
        (field (name "MANUFACTURER") "Stackpole Electronics Inc")
        (field (name "MANUFACTURER PART NUMBER") "RMCF0603ZT0R00")
      )
      (libsource (lib "RoboteX") (part "Res"))
    )
    (comp (ref "R78")
      (value "0")
      (footprint "RES0603N")
      (description "RES 0.0 OHM 1/10W 0603 SMD")
      (fields
        (field (name "MANUFACTURER") "Stackpole Electronics Inc")
        (field (name "MANUFACTURER PART NUMBER") "RMCF0603ZT0R00")
      )
      (libsource (lib "RoboteX") (part "Res"))
    )
    (comp (ref "TP1")
      (value "Test Point, 60mil")
      (footprint "test_point_60_mil")
      (libsource (lib "RoboteX") (part "test_point"))
    )
    (comp (ref "TP2")
      (value "Test Point, 60mil")
      (footprint "test_point_60_mil")
      (libsource (lib "RoboteX") (part "test_point"))
    )
    (comp (ref "TP3")
      (value "Test Point, 60mil")
      (footprint "test_point_60_mil")
      (libsource (lib "RoboteX") (part "test_point"))
    )
    (comp (ref "TP4")
      (value "Test Point, 60mil")
      (footprint "test_point_60_mil")
      (libsource (lib "RoboteX") (part "test_point"))
    )
    (comp (ref "TP5")
      (value "Test Point, 60mil")
      (footprint "test_point_60_mil")
      (libsource (lib "RoboteX") (part "test_point"))
    )
    (comp (ref "TP6")
      (value "Test Point, 60mil")
      (footprint "test_point_60_mil")
      (libsource (lib "RoboteX") (part "test_point"))
    )
    (comp (ref "TP7")
      (value "Test Point, 60mil")
      (footprint "test_point_60_mil")
      (libsource (lib "RoboteX") (part "test_point"))
    )
    (comp (ref "TP8")
      (value "Test Point, 60mil")
      (footprint "test_point_60_mil")
      (libsource (lib "RoboteX") (part "test_point"))
    )
    (comp (ref "U1")
      (value "LAN9500AI-ABZJ-T")
      (footprint "QFN56_8X8MC-M")
      (description "Imported")
      (fields (field (name "MANUFACTURER_PART_NUMBER") "LAN9500AI-ABZJ-TR"))
      (libsource (lib "AltiumDesigner") (part "LAN9500AI-ABZJ-T"))
    )
    (comp (ref "U2")
      (value "CAN/TJA1050T/CM")
      (footprint "SOIC-8_150mil")
      (description "CAN")
      (libsource (lib "Miscellaneous Devices LC") (part "CAN/TJA1050T/CM_[C6952]"))
    )
    (comp (ref "U3")
      (value "93AA56AT-I/OT")
      (footprint "SOT-23-6_MC-M")
      (description "Imported")
      (libsource (lib "AltiumDesigner") (part "93AA56AT-I/OT"))
    )
    (comp (ref "U4")
      (value "TPS65279DAPR")
      (footprint "DAD32-M")
      (description "IC REG BUCK ADJ 5A DL 32HTSSOP")
      (fields (field (name "PART NUMBER") "TPS65279DAP") (field (name "MANUFACTURER") "Texas Instruments"))
      (libsource (lib "RoboteX") (part "TPS65279DAPR"))
    )
    (comp (ref "U5")
      (value "PCM2912A")
      (footprint "PJT32-M")
      (description "IC STEREO AUD CODEC W/USB 32TQFP")
      (fields
        (field (name "MANUFACTURER") "Texas Instruments")
        (field (name "MANUFACTURER PART NUMBER") "PCM2912APJTR")
      )
      (libsource (lib "RoboteX") (part "PCM2912A_PJT_32"))
    )
    (comp (ref "U6")
      (value "DSUB25_M_WDB951-PM25G")
      (footprint "DSUB25_M_WDB951-PM25G")
      (fields
        (field (name "MANUFACTURER") "MMT Machrone")
        (field (name "MANUFACTURER PART NUMBER") "WDB951-PM25G")
      )
      (libsource (lib "RoboteX") (part "DSUB-25_Male_Board_Locks"))
    )
    (comp (ref "U7")
      (value "MCP6002T-I/MS")
      (footprint "MSOP-MS8_N")
      (description "IC OPAMP 1.8V 1MHZ DUAL 8-MSOP")
      (fields (field (name "MANUFACTURER") "Microchip") (field (name "PUBLISHER") "Altium Limited"))
      (libsource (lib "RoboteX") (part "MCP6002T-I/MS"))
    )
    (comp (ref "U8")
      (value "DSUB25_M_WDB951-PM25G")
      (footprint "DSUB25_M_WDB951-PM25G")
      (fields
        (field (name "MANUFACTURER") "MMT Machrone")
        (field (name "MANUFACTURER PART NUMBER") "WDB951-PM25G")
      )
      (libsource (lib "RoboteX") (part "DSUB-25_Male_Board_Locks"))
    )
    (comp (ref "U9")
      (value "TPA6211A1DRBR")
      (footprint "DRB8_1P75X1P5")
      (description "IC AMP AUDIO PWR 3.1W MONO 8SON")
      (fields (field (name "MANUFACTURER") "Texas Instruments"))
      (libsource (lib "RoboteX") (part "TPA6211A1_DRB_8"))
    )
    (comp (ref "U10")
      (value "LM50CIM3/NOPB")
      (footprint "MF03A-M")
      (description "Temperature Sensor Analog, Local -40°C ~ 125°C 10mV/°C SOT-23-3")
      (fields (field (name "MANUFACTURER") "Texas Instruments"))
      (libsource (lib "RoboteX") (part "LM50_DBZ_3"))
    )
    (comp (ref "U11")
      (value "ULN2803ADW")
      (footprint "SOIC-18_300mil")
      (description "大电流驱动")
      (libsource (lib "Miscellaneous Devices LC") (part "ULN2803ADW_[C9683]"))
    )
    (comp (ref "VR1")
      (value "AZ1117EH-3.3TRG1")
      (footprint "SOT-223")
      (description "IC REG LINEAR 3.3V 1A SOT223")
      (fields (field (name "MANUFACTURER") "Diodes Incorporated"))
      (libsource (lib "RoboteX") (part "AZ1117EH-3.3TRG1"))
    )
    (comp (ref "VR2")
      (value "AZ1117EH-3.3TRG1")
      (footprint "SOT-223")
      (description "IC REG LINEAR 3.3V 1A SOT223")
      (fields (field (name "MANUFACTURER") "Diodes Incorporated"))
      (libsource (lib "RoboteX") (part "AZ1117EH-3.3TRG1"))
    )
    (comp (ref "Y1")
      (value "25MHZ 12PF 10PPM")
      (footprint "SMD-3225_4P")
      (description "贴片晶振")
      (libsource (lib "Miscellaneous Devices LC") (part "SMD-3225_4P  25MHZ 12PF 10PPM"))
    )
    (comp (ref "Y2")
      (value "ABMM-6.000MHZ-B2-T")
      (footprint "SMD-7050_4P")
      (description "CRYSTAL 6.0000MHZ 18PF SMD")
      (fields (field (name "MANUFACTURER") "Abracon LLC"))
      (libsource (lib "RoboteX") (part "XTAL_4P"))
    )
  )
  (nets
    (net (code "1") (name "/ADC1") (class "Default")
      (node (ref "P8") (pin "43") (pinfunction "43_43") (pintype "passive"))
      (node (ref "U10") (pin "2") (pinfunction "VO_2") (pintype "output"))
    )
    (net (code "2") (name "/ADC2{slash}IO") (class "Default")
      (node (ref "P8") (pin "45") (pinfunction "45_45") (pintype "passive"))
      (node (ref "R64") (pin "1") (pinfunction "1_1") (pintype "passive"))
    )
    (net (code "3") (name "/AUDIO_USB_N") (class "Default")
      (node (ref "J2") (pin "2") (pinfunction "D-_2") (pintype "passive"))
      (node (ref "R38") (pin "1") (pinfunction "1_1") (pintype "passive"))
    )
    (net (code "4") (name "/AUDIO_USB_P") (class "Default")
      (node (ref "J2") (pin "3") (pinfunction "D+_3") (pintype "passive"))
      (node (ref "R39") (pin "1") (pinfunction "1_1") (pintype "passive"))
      (node (ref "R40") (pin "1") (pinfunction "1_1") (pintype "passive"))
    )
    (net (code "5") (name "/BUTTON3") (class "Default")
      (node (ref "P5") (pin "1") (pinfunction "1_1") (pintype "passive"))
      (node (ref "P8") (pin "23") (pinfunction "23_23") (pintype "passive"))
      (node (ref "R10") (pin "1") (pinfunction "1_1") (pintype "passive"))
    )
    (net (code "6") (name "/BUTTON4") (class "Default")
      (node (ref "P6") (pin "1") (pinfunction "1_1") (pintype "passive"))
      (node (ref "P8") (pin "24") (pinfunction "24_24") (pintype "passive"))
      (node (ref "R11") (pin "1") (pinfunction "1_1") (pintype "passive"))
    )
    (net (code "7") (name "/CAN2H") (class "Default")
      (node (ref "P8") (pin "10") (pinfunction "10_10") (pintype "passive"))
    )
    (net (code "8") (name "/CAN2L") (class "Default")
      (node (ref "P8") (pin "9") (pinfunction "9_9") (pintype "passive"))
    )
    (net (code "9") (name "/CAN_N") (class "Default")
      (node (ref "P27") (pin "3") (pinfunction "3_3") (pintype "passive"))
      (node (ref "P8") (pin "11") (pinfunction "11_11") (pintype "passive"))
      (node (ref "R15") (pin "1") (pinfunction "1_1") (pintype "passive"))
      (node (ref "U2") (pin "6") (pinfunction "CANL_6") (pintype "passive"))
    )
    (net (code "10") (name "/CAN_P") (class "Default")
      (node (ref "P27") (pin "1") (pinfunction "1_1") (pintype "passive"))
      (node (ref "P8") (pin "12") (pinfunction "12_12") (pintype "passive"))
      (node (ref "R15") (pin "2") (pinfunction "2_2") (pintype "passive"))
      (node (ref "U2") (pin "7") (pinfunction "CANH_7") (pintype "passive"))
    )
    (net (code "11") (name "/ECHO_5") (class "Default")
      (node (ref "P1") (pin "3") (pinfunction "3_3") (pintype "output"))
      (node (ref "P8") (pin "21") (pinfunction "21_21") (pintype "passive"))
    )
    (net (code "12") (name "/ECHO_6") (class "Default")
      (node (ref "P2") (pin "3") (pinfunction "3_3") (pintype "output"))
      (node (ref "P8") (pin "17") (pinfunction "17_17") (pintype "passive"))
    )
    (net (code "13") (name "/ECHO_7") (class "Default")
      (node (ref "P3") (pin "3") (pinfunction "3_3") (pintype "output"))
      (node (ref "P8") (pin "15") (pinfunction "15_15") (pintype "passive"))
    )
    (net (code "14") (name "/ECHO_8") (class "Default")
      (node (ref "P4") (pin "3") (pinfunction "3_3") (pintype "output"))
      (node (ref "P8") (pin "13") (pinfunction "13_13") (pintype "passive"))
    )
    (net (code "15") (name "/EECLK") (class "Default")
      (node (ref "U1") (pin "29") (pinfunction "EECLK/*PWR_SEL_29") (pintype "bidirectional"))
      (node (ref "U3") (pin "4") (pinfunction "CLK_4") (pintype "passive"))
    )
    (net (code "16") (name "/EECS") (class "Default")
      (node (ref "U1") (pin "30") (pinfunction "EECS_30") (pintype "output"))
      (node (ref "U3") (pin "5") (pinfunction "CS_5") (pintype "passive"))
    )
    (net (code "17") (name "/EEDI") (class "Default")
      (node (ref "U1") (pin "32") (pinfunction "EEDI_32") (pintype "input"))
      (node (ref "U3") (pin "1") (pinfunction "DO_1") (pintype "passive"))
    )
    (net (code "18") (name "/EEDO") (class "Default")
      (node (ref "U1") (pin "31") (pinfunction "EEDO/*AUTOMDIX_EN_31") (pintype "bidirectional"))
      (node (ref "U3") (pin "3") (pinfunction "DI_3") (pintype "passive"))
    )
    (net (code "19") (name "/FAN1_CTL") (class "Default")
      (node (ref "P8") (pin "31") (pinfunction "31_31") (pintype "passive"))
      (node (ref "R73") (pin "1") (pinfunction "1_1") (pintype "passive"))
    )
    (net (code "20") (name "/FAN1_PWM") (class "Default")
      (node (ref "P8") (pin "33") (pinfunction "33_33") (pintype "passive"))
      (node (ref "R76") (pin "2") (pinfunction "2_2") (pintype "passive"))
    )
    (net (code "21") (name "/FAN2_CTL") (class "Default")
      (node (ref "P8") (pin "32") (pinfunction "32_32") (pintype "passive"))
      (node (ref "R68") (pin "1") (pinfunction "1_1") (pintype "passive"))
    )
    (net (code "22") (name "/FAN2_PWM") (class "Default")
      (node (ref "P8") (pin "34") (pinfunction "34_34") (pintype "passive"))
      (node (ref "R71") (pin "2") (pinfunction "2_2") (pintype "passive"))
    )
    (net (code "23") (name "/FB1") (class "Default")
      (node (ref "C47") (pin "1") (pinfunction "1_1") (pintype "passive"))
      (node (ref "R30") (pin "1") (pinfunction "1_1") (pintype "passive"))
      (node (ref "R35") (pin "2") (pinfunction "2_2") (pintype "passive"))
      (node (ref "U4") (pin "17") (pinfunction "FB1_17") (pintype "passive"))
    )
    (net (code "24") (name "/FB2") (class "Default")
      (node (ref "C24") (pin "2") (pinfunction "2_2") (pintype "passive"))
      (node (ref "R16") (pin "1") (pinfunction "1_1") (pintype "passive"))
      (node (ref "R20") (pin "2") (pinfunction "2_2") (pintype "passive"))
      (node (ref "U4") (pin "32") (pinfunction "FB2_32") (pintype "passive"))
    )
    (net (code "25") (name "/FDX") (class "Default")
      (node (ref "R12") (pin "2") (pinfunction "2_2") (pintype "passive"))
      (node (ref "U1") (pin "26") (pinfunction "NFDX_LED/GPIO8_26") (pintype "bidirectional"))
    )
    (net (code "26") (name "/I2C_SCL") (class "Default")
      (node (ref "P27") (pin "5") (pinfunction "5_5") (pintype "passive"))
      (node (ref "P31") (pin "4") (pinfunction "4_4") (pintype "passive"))
      (node (ref "P8") (pin "7") (pinfunction "7_7") (pintype "passive"))
    )
    (net (code "27") (name "/I2C_SDA") (class "Default")
      (node (ref "P27") (pin "6") (pinfunction "6_6") (pintype "passive"))
      (node (ref "P31") (pin "3") (pinfunction "3_3") (pintype "passive"))
      (node (ref "P8") (pin "8") (pinfunction "8_8") (pintype "passive"))
    )
    (net (code "28") (name "/ICSP_3.3V") (class "Default")
      (node (ref "P27") (pin "9") (pinfunction "9_9") (pintype "passive"))
      (node (ref "U8") (pin "13") (pinfunction "13_13") (pintype "passive"))
    )
    (net (code "29") (name "/INF5") (class "Default")
      (node (ref "P10") (pin "3") (pinfunction "3_3") (pintype "passive"))
      (node (ref "P8") (pin "25") (pinfunction "25_25") (pintype "passive"))
    )
    (net (code "30") (name "/INF6") (class "Default")
      (node (ref "P12") (pin "3") (pinfunction "3_3") (pintype "passive"))
      (node (ref "P8") (pin "26") (pinfunction "26_26") (pintype "passive"))
    )
    (net (code "31") (name "/INF7") (class "Default")
      (node (ref "P17") (pin "3") (pinfunction "3_3") (pintype "passive"))
      (node (ref "P8") (pin "27") (pinfunction "27_27") (pintype "passive"))
    )
    (net (code "32") (name "/INF8") (class "Default")
      (node (ref "P22") (pin "3") (pinfunction "3_3") (pintype "passive"))
      (node (ref "P8") (pin "28") (pinfunction "28_28") (pintype "passive"))
    )
    (net (code "33") (name "/LED1") (class "Default")
      (node (ref "P8") (pin "35") (pinfunction "35_35") (pintype "passive"))
      (node (ref "U11") (pin "1") (pinfunction "IN1_1") (pintype "input"))
      (node (ref "U11") (pin "2") (pinfunction "IN2_2") (pintype "input"))
    )
    (net (code "34") (name "/LED2") (class "Default")
      (node (ref "P8") (pin "36") (pinfunction "36_36") (pintype "passive"))
      (node (ref "U11") (pin "3") (pinfunction "IN3_3") (pintype "input"))
      (node (ref "U11") (pin "4") (pinfunction "IN4_4") (pintype "input"))
    )
    (net (code "35") (name "/LED3") (class "Default")
      (node (ref "P8") (pin "37") (pinfunction "37_37") (pintype "passive"))
      (node (ref "U11") (pin "5") (pinfunction "IN5_5") (pintype "input"))
      (node (ref "U11") (pin "6") (pinfunction "IN6_6") (pintype "input"))
    )
    (net (code "36") (name "/LED4") (class "Default")
      (node (ref "P8") (pin "38") (pinfunction "38_38") (pintype "passive"))
      (node (ref "U11") (pin "7") (pinfunction "IN7_7") (pintype "input"))
      (node (ref "U11") (pin "8") (pinfunction "IN8_8") (pintype "input"))
    )
    (net (code "37") (name "/LNK") (class "Default")
      (node (ref "R13") (pin "2") (pinfunction "2_2") (pintype "passive"))
      (node (ref "U1") (pin "27") (pinfunction "NLNKA_LED/GPIO9_27") (pintype "bidirectional"))
    )
    (net (code "38") (name "/MCLR") (class "Default")
      (node (ref "P27") (pin "12") (pinfunction "12_12") (pintype "passive"))
      (node (ref "U8") (pin "14") (pinfunction "14_14") (pintype "passive"))
    )
    (net (code "39") (name "/MIC_IN") (class "Default")
      (node (ref "C64") (pin "1") (pinfunction "1_1") (pintype "passive"))
      (node (ref "R48") (pin "1") (pinfunction "1_1") (pintype "passive"))
      (node (ref "R49") (pin "2") (pinfunction "2_2") (pintype "passive"))
      (node (ref "R50") (pin "2") (pinfunction "2_2") (pintype "passive"))
      (node (ref "TP5") (pin "0") (pinfunction "0_0") (pintype "passive"))
    )
    (net (code "40") (name "/MIC_OPAMP_OUT") (class "Default")
      (node (ref "C68") (pin "2") (pinfunction "2_2") (pintype "passive"))
      (node (ref "R49") (pin "1") (pinfunction "1_1") (pintype "passive"))
      (node (ref "R57") (pin "1") (pinfunction "1_1") (pintype "passive"))
      (node (ref "TP7") (pin "0") (pinfunction "0_0") (pintype "passive"))
      (node (ref "U7") (pin "7") (pinfunction "VOUTB_7") (pintype "output"))
    )
    (net (code "41") (name "/NC1") (class "Default")
      (node (ref "Y2") (pin "4") (pinfunction "NC_4") (pintype "passive"))
    )
    (net (code "42") (name "/NC2") (class "Default")
      (node (ref "Y2") (pin "2") (pinfunction "NC_2") (pintype "passive"))
    )
    (net (code "43") (name "/NC3") (class "Default")
      (node (ref "U5") (pin "14") (pinfunction "NC_14") (pintype "passive"))
    )
    (net (code "44") (name "/NRESET") (class "Default")
      (node (ref "C1") (pin "2") (pinfunction "2_2") (pintype "passive"))
      (node (ref "R5") (pin "1") (pinfunction "1_1") (pintype "passive"))
      (node (ref "U1") (pin "24") (pinfunction "NRESET_24") (pintype "input"))
    )
    (net (code "45") (name "/OUT") (class "Default")
      (node (ref "C67") (pin "2") (pinfunction "2_2") (pintype "passive"))
      (node (ref "R41") (pin "2") (pinfunction "2_2") (pintype "passive"))
      (node (ref "R47") (pin "2") (pinfunction "2_2") (pintype "passive"))
      (node (ref "TP4") (pin "0") (pinfunction "0_0") (pintype "passive"))
    )
    (net (code "46") (name "/OUTL") (class "Default")
      (node (ref "C60") (pin "2") (pinfunction "2_2") (pintype "passive"))
      (node (ref "R46") (pin "1") (pinfunction "1_1") (pintype "passive"))
      (node (ref "R47") (pin "1") (pinfunction "1_1") (pintype "passive"))
    )
    (net (code "47") (name "/OUTR") (class "Default")
      (node (ref "C52") (pin "2") (pinfunction "2_2") (pintype "passive"))
      (node (ref "R41") (pin "1") (pinfunction "1_1") (pintype "passive"))
      (node (ref "R44") (pin "2") (pinfunction "2_2") (pintype "passive"))
    )
    (net (code "48") (name "/PGEC") (class "Default")
      (node (ref "P27") (pin "10") (pinfunction "10_10") (pintype "passive"))
      (node (ref "R77") (pin "2") (pinfunction "2_2") (pintype "passive"))
      (node (ref "U8") (pin "12") (pinfunction "12_12") (pintype "passive"))
    )
    (net (code "49") (name "/PGED") (class "Default")
      (node (ref "P27") (pin "11") (pinfunction "11_11") (pintype "passive"))
      (node (ref "R78") (pin "2") (pinfunction "2_2") (pintype "passive"))
      (node (ref "U8") (pin "11") (pinfunction "11_11") (pintype "passive"))
    )
    (net (code "50") (name "/PGOOD1") (class "Default")
      (node (ref "R28") (pin "1") (pinfunction "1_1") (pintype "passive"))
      (node (ref "U4") (pin "15") (pinfunction "PGOOD1_15") (pintype "passive"))
    )
    (net (code "51") (name "/PGOOD2") (class "Default")
      (node (ref "R27") (pin "1") (pinfunction "1_1") (pintype "passive"))
      (node (ref "U4") (pin "16") (pinfunction "PGOOD2_16") (pintype "passive"))
    )
    (net (code "52") (name "/RX_N") (class "Default")
      (node (ref "P8") (pin "2") (pinfunction "2_2") (pintype "passive"))
      (node (ref "R2") (pin "1") (pinfunction "1_1") (pintype "passive"))
      (node (ref "U1") (pin "5") (pinfunction "RXN_5") (pintype "bidirectional"))
    )
    (net (code "53") (name "/RX_P") (class "Default")
      (node (ref "P8") (pin "4") (pinfunction "4_4") (pintype "passive"))
      (node (ref "R1") (pin "1") (pinfunction "1_1") (pintype "passive"))
      (node (ref "U1") (pin "6") (pinfunction "RXP_6") (pintype "bidirectional"))
    )
    (net (code "54") (name "/SPD") (class "Default")
      (node (ref "R14") (pin "2") (pinfunction "2_2") (pintype "passive"))
      (node (ref "U1") (pin "28") (pinfunction "NSPD_LED/GPIO10_28") (pintype "bidirectional"))
    )
    (net (code "55") (name "/SPKR+") (class "Default")
      (node (ref "P28") (pin "1") (pinfunction "1_1") (pintype "passive"))
      (node (ref "P29") (pin "1") (pinfunction "1_1") (pintype "passive"))
      (node (ref "U9") (pin "5") (pinfunction "VO+_5") (pintype "output"))
    )
    (net (code "56") (name "/SPKR-") (class "Default")
      (node (ref "P28") (pin "2") (pinfunction "2_2") (pintype "passive"))
      (node (ref "P29") (pin "2") (pinfunction "2_2") (pintype "passive"))
      (node (ref "U9") (pin "8") (pinfunction "VO-_8") (pintype "output"))
    )
    (net (code "57") (name "/TRIG5") (class "Default")
      (node (ref "P1") (pin "2") (pinfunction "2_2") (pintype "input"))
      (node (ref "P8") (pin "22") (pinfunction "22_22") (pintype "passive"))
    )
    (net (code "58") (name "/TRIG6") (class "Default")
      (node (ref "P2") (pin "2") (pinfunction "2_2") (pintype "input"))
      (node (ref "P8") (pin "18") (pinfunction "18_18") (pintype "passive"))
    )
    (net (code "59") (name "/TRIG7") (class "Default")
      (node (ref "P3") (pin "2") (pinfunction "2_2") (pintype "input"))
      (node (ref "P8") (pin "16") (pinfunction "16_16") (pintype "passive"))
    )
    (net (code "60") (name "/TRIG8") (class "Default")
      (node (ref "P4") (pin "2") (pinfunction "2_2") (pintype "input"))
      (node (ref "P8") (pin "14") (pinfunction "14_14") (pintype "passive"))
    )
    (net (code "61") (name "/TX_N") (class "Default")
      (node (ref "P8") (pin "1") (pinfunction "1_1") (pintype "passive"))
      (node (ref "R4") (pin "1") (pinfunction "1_1") (pintype "passive"))
      (node (ref "U1") (pin "2") (pinfunction "TXN_2") (pintype "bidirectional"))
    )
    (net (code "62") (name "/TX_P") (class "Default")
      (node (ref "P8") (pin "3") (pinfunction "3_3") (pintype "passive"))
      (node (ref "R3") (pin "1") (pinfunction "1_1") (pintype "passive"))
      (node (ref "U1") (pin "3") (pinfunction "TXP_3") (pintype "bidirectional"))
    )
    (net (code "63") (name "/UART_RX") (class "Default")
      (node (ref "P8") (pin "39") (pinfunction "39_39") (pintype "passive"))
      (node (ref "R78") (pin "1") (pinfunction "1_1") (pintype "passive"))
    )
    (net (code "64") (name "/UART_TX") (class "Default")
      (node (ref "P8") (pin "40") (pinfunction "40_40") (pintype "passive"))
      (node (ref "R77") (pin "1") (pinfunction "1_1") (pintype "passive"))
    )
    (net (code "65") (name "/USB0_N") (class "Default")
      (node (ref "J1") (pin "2") (pinfunction "D-_2") (pintype "passive"))
      (node (ref "U8") (pin "3") (pinfunction "3_3") (pintype "passive"))
    )
    (net (code "66") (name "/USB0_P") (class "Default")
      (node (ref "J1") (pin "3") (pinfunction "D+_3") (pintype "passive"))
      (node (ref "U8") (pin "2") (pinfunction "2_2") (pintype "passive"))
    )
    (net (code "67") (name "/USB_N") (class "Default")
      (node (ref "U1") (pin "11") (pinfunction "USBDM_11") (pintype "bidirectional"))
      (node (ref "U6") (pin "3") (pinfunction "3_3") (pintype "passive"))
    )
    (net (code "68") (name "/USB_P") (class "Default")
      (node (ref "U1") (pin "12") (pinfunction "USBDP_12") (pintype "bidirectional"))
      (node (ref "U6") (pin "2") (pinfunction "2_2") (pintype "passive"))
    )
    (net (code "69") (name "/V7V") (class "Default")
      (node (ref "C38") (pin "2") (pinfunction "2_2") (pintype "passive"))
      (node (ref "R24") (pin "2") (pinfunction "2_2") (pintype "passive"))
      (node (ref "R27") (pin "2") (pinfunction "2_2") (pintype "passive"))
      (node (ref "R28") (pin "2") (pinfunction "2_2") (pintype "passive"))
      (node (ref "U4") (pin "9") (pinfunction "V7V_9") (pintype "passive"))
    )
    (net (code "70") (name "/XI") (class "Default")
      (node (ref "C16") (pin "2") (pinfunction "2_2") (pintype "passive"))
      (node (ref "R8") (pin "1") (pinfunction "1_1") (pintype "passive"))
      (node (ref "U1") (pin "18") (pinfunction "XI_18") (pintype "input"))
      (node (ref "Y1") (pin "1") (pinfunction "OSC1_1") (pintype "passive"))
    )
    (net (code "71") (name "/XO") (class "Default")
      (node (ref "C17") (pin "2") (pinfunction "2_2") (pintype "passive"))
      (node (ref "R8") (pin "2") (pinfunction "2_2") (pintype "passive"))
      (node (ref "U1") (pin "19") (pinfunction "XO_19") (pintype "output"))
      (node (ref "Y1") (pin "3") (pinfunction "OSC2_3") (pintype "passive"))
    )
    (net (code "72") (name "/~AUDIO_USB_N") (class "Default")
      (node (ref "R38") (pin "2") (pinfunction "2_2") (pintype "passive"))
      (node (ref "U5") (pin "3") (pinfunction "D-_3") (pintype "bidirectional"))
    )
    (net (code "73") (name "/~AUDIO_USB_P") (class "Default")
      (node (ref "R39") (pin "2") (pinfunction "2_2") (pintype "passive"))
      (node (ref "U5") (pin "4") (pinfunction "D+_4") (pintype "bidirectional"))
    )
    (net (code "74") (name "/~LED1") (class "Default")
      (node (ref "P19") (pin "2") (pinfunction "2_2") (pintype "passive"))
      (node (ref "U11") (pin "17") (pinfunction "OUT2_17") (pintype "open_collector"))
      (node (ref "U11") (pin "18") (pinfunction "OUT1_18") (pintype "open_collector"))
    )
    (net (code "75") (name "/~LED2") (class "Default")
      (node (ref "P13") (pin "2") (pinfunction "2_2") (pintype "passive"))
      (node (ref "U11") (pin "15") (pinfunction "OUT4_15") (pintype "open_collector"))
      (node (ref "U11") (pin "16") (pinfunction "OUT3_16") (pintype "open_collector"))
    )
    (net (code "76") (name "/~LED3") (class "Default")
      (node (ref "P23") (pin "2") (pinfunction "2_2") (pintype "passive"))
      (node (ref "U11") (pin "13") (pinfunction "OUT6_13") (pintype "open_collector"))
      (node (ref "U11") (pin "14") (pinfunction "OUT5_14") (pintype "open_collector"))
    )
    (net (code "77") (name "/~LED4") (class "Default")
      (node (ref "P14") (pin "2") (pinfunction "2_2") (pintype "passive"))
      (node (ref "U11") (pin "11") (pinfunction "OUT8_11") (pintype "open_collector"))
      (node (ref "U11") (pin "12") (pinfunction "OUT7_12") (pintype "open_collector"))
    )
    (net (code "78") (name "3V3") (class "Default")
      (node (ref "C10") (pin "2") (pinfunction "2_2") (pintype "passive"))
      (node (ref "C11") (pin "2") (pinfunction "2_2") (pintype "passive"))
      (node (ref "C18") (pin "2") (pinfunction "2_2") (pintype "passive"))
      (node (ref "C32") (pin "2") (pinfunction "2_2") (pintype "passive"))
      (node (ref "C7") (pin "2") (pinfunction "2_2") (pintype "passive"))
      (node (ref "C8") (pin "2") (pinfunction "2_2") (pintype "passive"))
      (node (ref "C9") (pin "2") (pinfunction "2_2") (pintype "passive"))
      (node (ref "D1") (pin "A") (pinfunction "A_A") (pintype "passive"))
      (node (ref "D2") (pin "A") (pinfunction "A_A") (pintype "passive"))
      (node (ref "D3") (pin "A") (pinfunction "A_A") (pintype "passive"))
      (node (ref "D6") (pin "A") (pinfunction "A_A") (pintype "passive"))
      (node (ref "FB1") (pin "1") (pinfunction "1_1") (pintype "passive"))
      (node (ref "R5") (pin "2") (pinfunction "2_2") (pintype "passive"))
      (node (ref "R9") (pin "1") (pinfunction "1_1") (pintype "passive"))
      (node (ref "U1") (pin "25") (pinfunction "VDD33IO_25") (pintype "power_in"))
      (node (ref "U1") (pin "35") (pinfunction "VDD33IO_35") (pintype "power_in"))
      (node (ref "U1") (pin "48") (pinfunction "VDD33IO_48") (pintype "power_in"))
      (node (ref "U1") (pin "49") (pinfunction "TEST1_49") (pintype "passive"))
      (node (ref "U1") (pin "51") (pinfunction "VDD33IO_51") (pintype "power_in"))
      (node (ref "U1") (pin "52") (pinfunction "VDD33IO_52") (pintype "power_in"))
      (node (ref "U3") (pin "6") (pinfunction "VCC_6") (pintype "passive"))
      (node (ref "VR1") (pin "2") (pinfunction "OUT_2") (pintype "passive"))
      (node (ref "VR1") (pin "4") (pinfunction "OUT_4") (pintype "passive"))
    )
    (net (code "79") (name "3V3_SENSOR") (class "Default")
      (node (ref "C72") (pin "2") (pinfunction "2_2") (pintype "passive"))
      (node (ref "P10") (pin "2") (pinfunction "2_2") (pintype "passive"))
      (node (ref "P12") (pin "2") (pinfunction "2_2") (pintype "passive"))
      (node (ref "P17") (pin "2") (pinfunction "2_2") (pintype "passive"))
      (node (ref "P22") (pin "2") (pinfunction "2_2") (pintype "passive"))
      (node (ref "P31") (pin "2") (pinfunction "2_2") (pintype "passive"))
      (node (ref "R10") (pin "2") (pinfunction "2_2") (pintype "passive"))
      (node (ref "R11") (pin "2") (pinfunction "2_2") (pintype "passive"))
      (node (ref "VR2") (pin "2") (pinfunction "OUT_2") (pintype "passive"))
      (node (ref "VR2") (pin "4") (pinfunction "OUT_4") (pintype "passive"))
    )
    (net (code "80") (name "5V") (class "Default")
      (node (ref "C19") (pin "2") (pinfunction "2_2") (pintype "passive"))
      (node (ref "C24") (pin "1") (pinfunction "1_1") (pintype "passive"))
      (node (ref "C25") (pin "2") (pinfunction "2_2") (pintype "passive"))
      (node (ref "C26") (pin "2") (pinfunction "2_2") (pintype "passive"))
      (node (ref "C27") (pin "2") (pinfunction "2_2") (pintype "passive"))
      (node (ref "C28") (pin "2") (pinfunction "2_2") (pintype "passive"))
      (node (ref "C29") (pin "2") (pinfunction "2_2") (pintype "passive"))
      (node (ref "C30") (pin "2") (pinfunction "2_2") (pintype "passive"))
      (node (ref "C49") (pin "1") (pinfunction "1_1") (pintype "passive"))
      (node (ref "C66") (pin "2") (pinfunction "2_2") (pintype "passive"))
      (node (ref "C71") (pin "2") (pinfunction "2_2") (pintype "passive"))
      (node (ref "D7") (pin "A") (pinfunction "A_A") (pintype "passive"))
      (node (ref "D8") (pin "A") (pinfunction "A_A") (pintype "passive"))
      (node (ref "D9") (pin "A") (pinfunction "A_A") (pintype "passive"))
      (node (ref "FB4") (pin "2") (pinfunction "2_2") (pintype "passive"))
      (node (ref "L1") (pin "3") (pinfunction "3_3") (pintype "passive"))
      (node (ref "L1") (pin "4") (pinfunction "4_4") (pintype "passive"))
      (node (ref "P1") (pin "1") (pinfunction "1_1") (pintype "passive"))
      (node (ref "P15") (pin "1") (pinfunction "1_1") (pintype "passive"))
      (node (ref "P2") (pin "1") (pinfunction "1_1") (pintype "passive"))
      (node (ref "P27") (pin "18") (pinfunction "18_18") (pintype "passive"))
      (node (ref "P27") (pin "20") (pinfunction "20_20") (pintype "passive"))
      (node (ref "P3") (pin "1") (pinfunction "1_1") (pintype "passive"))
      (node (ref "P4") (pin "1") (pinfunction "1_1") (pintype "passive"))
      (node (ref "P8") (pin "44") (pinfunction "44_44") (pintype "passive"))
      (node (ref "P8") (pin "46") (pinfunction "46_46") (pintype "passive"))
      (node (ref "P8") (pin "47") (pinfunction "47_47") (pintype "passive"))
      (node (ref "P8") (pin "48") (pinfunction "48_48") (pintype "passive"))
      (node (ref "P8") (pin "49") (pinfunction "49_49") (pintype "passive"))
      (node (ref "P8") (pin "50") (pinfunction "50_50") (pintype "passive"))
      (node (ref "Q1") (pin "1") (pinfunction "G_1") (pintype "passive"))
      (node (ref "Q1") (pin "2") (pinfunction "D_2") (pintype "passive"))
      (node (ref "Q1") (pin "3") (pinfunction "S_3") (pintype "passive"))
      (node (ref "R20") (pin "1") (pinfunction "1_1") (pintype "passive"))
      (node (ref "R51") (pin "1") (pinfunction "1_1") (pintype "passive"))
      (node (ref "R52") (pin "2") (pinfunction "2_2") (pintype "passive"))
      (node (ref "R58") (pin "1") (pinfunction "1_1") (pintype "passive"))
      (node (ref "R59") (pin "2") (pinfunction "2_2") (pintype "passive"))
      (node (ref "R61") (pin "2") (pinfunction "2_2") (pintype "passive"))
      (node (ref "R62") (pin "2") (pinfunction "2_2") (pintype "passive"))
      (node (ref "R70") (pin "2") (pinfunction "2_2") (pintype "passive"))
      (node (ref "R75") (pin "2") (pinfunction "2_2") (pintype "passive"))
      (node (ref "TP1") (pin "0") (pinfunction "0_0") (pintype "passive"))
      (node (ref "U10") (pin "1") (pinfunction "+VS_1") (pintype "input"))
      (node (ref "U2") (pin "3") (pinfunction "VCC_3") (pintype "passive"))
      (node (ref "U5") (pin "2") (pinfunction "VBUS_2") (pintype "power_in"))
      (node (ref "U7") (pin "8") (pinfunction "VDD_8") (pintype "power_in"))
      (node (ref "U9") (pin "6") (pinfunction "VDD_6") (pintype "power_in"))
      (node (ref "VR1") (pin "3") (pinfunction "IN_3") (pintype "passive"))
      (node (ref "VR2") (pin "3") (pinfunction "IN_3") (pintype "passive"))
    )
    (net (code "81") (name "12V") (class "Default")
      (node (ref "C42") (pin "2") (pinfunction "2_2") (pintype "passive"))
      (node (ref "C43") (pin "2") (pinfunction "2_2") (pintype "passive"))
      (node (ref "C44") (pin "2") (pinfunction "2_2") (pintype "passive"))
      (node (ref "C45") (pin "2") (pinfunction "2_2") (pintype "passive"))
      (node (ref "C46") (pin "2") (pinfunction "2_2") (pintype "passive"))
      (node (ref "C47") (pin "2") (pinfunction "2_2") (pintype "passive"))
      (node (ref "D4") (pin "A") (pinfunction "A_A") (pintype "passive"))
      (node (ref "L2") (pin "3") (pinfunction "3_3") (pintype "passive"))
      (node (ref "L2") (pin "4") (pinfunction "4_4") (pintype "passive"))
      (node (ref "P13") (pin "1") (pinfunction "1_1") (pintype "passive"))
      (node (ref "P14") (pin "1") (pinfunction "1_1") (pintype "passive"))
      (node (ref "P16") (pin "1") (pinfunction "1_1") (pintype "passive"))
      (node (ref "P19") (pin "1") (pinfunction "1_1") (pintype "passive"))
      (node (ref "P20") (pin "1") (pinfunction "1_1") (pintype "passive"))
      (node (ref "P23") (pin "1") (pinfunction "1_1") (pintype "passive"))
      (node (ref "P26") (pin "3") (pinfunction "3_3") (pintype "passive"))
      (node (ref "P7") (pin "1") (pinfunction "1_1") (pintype "passive"))
      (node (ref "Q4") (pin "1") (pinfunction "G_1") (pintype "passive"))
      (node (ref "Q4") (pin "2") (pinfunction "D_2") (pintype "passive"))
      (node (ref "Q4") (pin "3") (pinfunction "S_3") (pintype "passive"))
      (node (ref "Q7") (pin "1") (pinfunction "G_1") (pintype "passive"))
      (node (ref "Q7") (pin "2") (pinfunction "D_2") (pintype "passive"))
      (node (ref "Q7") (pin "3") (pinfunction "S_3") (pintype "passive"))
      (node (ref "R30") (pin "2") (pinfunction "2_2") (pintype "passive"))
      (node (ref "R65") (pin "2") (pinfunction "2_2") (pintype "passive"))
      (node (ref "R66") (pin "2") (pinfunction "2_2") (pintype "passive"))
      (node (ref "R67") (pin "2") (pinfunction "2_2") (pintype "passive"))
      (node (ref "R72") (pin "2") (pinfunction "2_2") (pintype "passive"))
      (node (ref "TP2") (pin "0") (pinfunction "0_0") (pintype "passive"))
    )
    (net (code "82") (name "16V") (class "Default")
      (node (ref "C34") (pin "2") (pinfunction "2_2") (pintype "passive"))
      (node (ref "C40") (pin "2") (pinfunction "2_2") (pintype "passive"))
      (node (ref "D5") (pin "A") (pinfunction "A_A") (pintype "passive"))
      (node (ref "P27") (pin "2") (pinfunction "2_2") (pintype "passive"))
      (node (ref "P27") (pin "4") (pinfunction "4_4") (pintype "passive"))
      (node (ref "P30") (pin "1") (pinfunction "1_1") (pintype "passive"))
      (node (ref "P9") (pin "1") (pinfunction "1_1") (pintype "passive"))
      (node (ref "Q2") (pin "1") (pinfunction "G_1") (pintype "passive"))
      (node (ref "Q2") (pin "2") (pinfunction "D_2") (pintype "passive"))
      (node (ref "Q2") (pin "3") (pinfunction "S_3") (pintype "passive"))
      (node (ref "R17") (pin "1") (pinfunction "1_1") (pintype "passive"))
      (node (ref "R19") (pin "1") (pinfunction "1_1") (pintype "passive"))
      (node (ref "U4") (pin "10") (pinfunction "VIN_10") (pintype "passive"))
      (node (ref "U4") (pin "11") (pinfunction "PVIN1_11") (pintype "passive"))
      (node (ref "U4") (pin "12") (pinfunction "PVIN1_12") (pintype "passive"))
      (node (ref "U4") (pin "5") (pinfunction "PVIN2_5") (pintype "passive"))
      (node (ref "U4") (pin "6") (pinfunction "PVIN2_6") (pintype "passive"))
      (node (ref "U6") (pin "19") (pinfunction "19_19") (pintype "passive"))
      (node (ref "U6") (pin "20") (pinfunction "20_20") (pintype "passive"))
      (node (ref "U6") (pin "21") (pinfunction "21_21") (pintype "passive"))
      (node (ref "U6") (pin "22") (pinfunction "22_22") (pintype "passive"))
      (node (ref "U6") (pin "23") (pinfunction "23_23") (pintype "passive"))
      (node (ref "U6") (pin "24") (pinfunction "24_24") (pintype "passive"))
      (node (ref "U6") (pin "25") (pinfunction "25_25") (pintype "passive"))
      (node (ref "U8") (pin "19") (pinfunction "19_19") (pintype "passive"))
      (node (ref "U8") (pin "20") (pinfunction "20_20") (pintype "passive"))
      (node (ref "U8") (pin "21") (pinfunction "21_21") (pintype "passive"))
      (node (ref "U8") (pin "22") (pinfunction "22_22") (pintype "passive"))
      (node (ref "U8") (pin "23") (pinfunction "23_23") (pintype "passive"))
      (node (ref "U8") (pin "24") (pinfunction "24_24") (pintype "passive"))
      (node (ref "U8") (pin "25") (pinfunction "25_25") (pintype "passive"))
    )
    (net (code "83") (name "AGND") (class "Default")
      (node (ref "C22") (pin "2") (pinfunction "2_2") (pintype "passive"))
      (node (ref "C33") (pin "1") (pinfunction "1_1") (pintype "passive"))
      (node (ref "C35") (pin "2") (pinfunction "2_2") (pintype "passive"))
      (node (ref "C37") (pin "2") (pinfunction "2_2") (pintype "passive"))
      (node (ref "C39") (pin "1") (pinfunction "1_1") (pintype "passive"))
      (node (ref "C48") (pin "2") (pinfunction "2_2") (pintype "passive"))
      (node (ref "R16") (pin "2") (pinfunction "2_2") (pintype "passive"))
      (node (ref "R18") (pin "2") (pinfunction "2_2") (pintype "passive"))
      (node (ref "R21") (pin "2") (pinfunction "2_2") (pintype "passive"))
      (node (ref "R22") (pin "2") (pinfunction "2_2") (pintype "passive"))
      (node (ref "R23") (pin "2") (pinfunction "2_2") (pintype "passive"))
      (node (ref "R25") (pin "2") (pinfunction "2_2") (pintype "passive"))
      (node (ref "R32") (pin "2") (pinfunction "2_2") (pintype "passive"))
      (node (ref "R33") (pin "1") (pinfunction "1_1") (pintype "passive"))
      (node (ref "R35") (pin "1") (pinfunction "1_1") (pintype "passive"))
      (node (ref "U4") (pin "25") (pinfunction "AGND_25") (pintype "passive"))
      (node (ref "U4") (pin "7") (pinfunction "ISHARE_7") (pintype "passive"))
    )
    (net (code "84") (name "GND") (class "Default")
      (node (ref "C1") (pin "1") (pinfunction "1_1") (pintype "passive"))
      (node (ref "C10") (pin "1") (pinfunction "1_1") (pintype "passive"))
      (node (ref "C11") (pin "1") (pinfunction "1_1") (pintype "passive"))
      (node (ref "C12") (pin "1") (pinfunction "1_1") (pintype "passive"))
      (node (ref "C13") (pin "1") (pinfunction "1_1") (pintype "passive"))
      (node (ref "C14") (pin "1") (pinfunction "1_1") (pintype "passive"))
      (node (ref "C15") (pin "1") (pinfunction "1_1") (pintype "passive"))
      (node (ref "C16") (pin "1") (pinfunction "1_1") (pintype "passive"))
      (node (ref "C17") (pin "1") (pinfunction "1_1") (pintype "passive"))
      (node (ref "C18") (pin "1") (pinfunction "1_1") (pintype "passive"))
      (node (ref "C19") (pin "1") (pinfunction "1_1") (pintype "passive"))
      (node (ref "C2") (pin "1") (pinfunction "1_1") (pintype "passive"))
      (node (ref "C20") (pin "2") (pinfunction "2_2") (pintype "passive"))
      (node (ref "C21") (pin "2") (pinfunction "2_2") (pintype "passive"))
      (node (ref "C25") (pin "1") (pinfunction "1_1") (pintype "passive"))
      (node (ref "C26") (pin "1") (pinfunction "1_1") (pintype "passive"))
      (node (ref "C27") (pin "1") (pinfunction "1_1") (pintype "passive"))
      (node (ref "C28") (pin "1") (pinfunction "1_1") (pintype "passive"))
      (node (ref "C29") (pin "1") (pinfunction "1_1") (pintype "passive"))
      (node (ref "C3") (pin "1") (pinfunction "1_1") (pintype "passive"))
      (node (ref "C30") (pin "1") (pinfunction "1_1") (pintype "passive"))
      (node (ref "C32") (pin "1") (pinfunction "1_1") (pintype "passive"))
      (node (ref "C34") (pin "1") (pinfunction "1_1") (pintype "passive"))
      (node (ref "C38") (pin "1") (pinfunction "1_1") (pintype "passive"))
      (node (ref "C4") (pin "1") (pinfunction "1_1") (pintype "passive"))
      (node (ref "C40") (pin "1") (pinfunction "1_1") (pintype "passive"))
      (node (ref "C42") (pin "1") (pinfunction "1_1") (pintype "passive"))
      (node (ref "C43") (pin "1") (pinfunction "1_1") (pintype "passive"))
      (node (ref "C44") (pin "1") (pinfunction "1_1") (pintype "passive"))
      (node (ref "C45") (pin "1") (pinfunction "1_1") (pintype "passive"))
      (node (ref "C46") (pin "1") (pinfunction "1_1") (pintype "passive"))
      (node (ref "C49") (pin "2") (pinfunction "2_2") (pintype "passive"))
      (node (ref "C5") (pin "1") (pinfunction "1_1") (pintype "passive"))
      (node (ref "C50") (pin "1") (pinfunction "1_1") (pintype "passive"))
      (node (ref "C51") (pin "1") (pinfunction "1_1") (pintype "passive"))
      (node (ref "C53") (pin "1") (pinfunction "1_1") (pintype "passive"))
      (node (ref "C54") (pin "1") (pinfunction "1_1") (pintype "passive"))
      (node (ref "C55") (pin "1") (pinfunction "1_1") (pintype "passive"))
      (node (ref "C56") (pin "1") (pinfunction "1_1") (pintype "passive"))
      (node (ref "C57") (pin "2") (pinfunction "2_2") (pintype "passive"))
      (node (ref "C58") (pin "2") (pinfunction "2_2") (pintype "passive"))
      (node (ref "C59") (pin "1") (pinfunction "1_1") (pintype "passive"))
      (node (ref "C6") (pin "1") (pinfunction "1_1") (pintype "passive"))
      (node (ref "C61") (pin "1") (pinfunction "1_1") (pintype "passive"))
      (node (ref "C62") (pin "1") (pinfunction "1_1") (pintype "passive"))
      (node (ref "C63") (pin "1") (pinfunction "1_1") (pintype "passive"))
      (node (ref "C66") (pin "1") (pinfunction "1_1") (pintype "passive"))
      (node (ref "C69") (pin "2") (pinfunction "2_2") (pintype "passive"))
      (node (ref "C7") (pin "1") (pinfunction "1_1") (pintype "passive"))
      (node (ref "C70") (pin "1") (pinfunction "1_1") (pintype "passive"))
      (node (ref "C71") (pin "1") (pinfunction "1_1") (pintype "passive"))
      (node (ref "C72") (pin "1") (pinfunction "1_1") (pintype "passive"))
      (node (ref "C8") (pin "1") (pinfunction "1_1") (pintype "passive"))
      (node (ref "C9") (pin "1") (pinfunction "1_1") (pintype "passive"))
      (node (ref "J1") (pin "4") (pinfunction "GND_4") (pintype "passive"))
      (node (ref "J1") (pin "7") (pinfunction "GND_DRAIN_7") (pintype "passive"))
      (node (ref "J2") (pin "4") (pinfunction "GND_4") (pintype "passive"))
      (node (ref "J2") (pin "7") (pinfunction "GND_DRAIN_7") (pintype "passive"))
      (node (ref "J3") (pin "4") (pinfunction "GND_4") (pintype "passive"))
      (node (ref "J3") (pin "7") (pinfunction "GND_DRAIN_7") (pintype "passive"))
      (node (ref "P1") (pin "4") (pinfunction "4_4") (pintype "passive"))
      (node (ref "P10") (pin "1") (pinfunction "1_1") (pintype "passive"))
      (node (ref "P12") (pin "1") (pinfunction "1_1") (pintype "passive"))
      (node (ref "P15") (pin "2") (pinfunction "2_2") (pintype "passive"))
      (node (ref "P16") (pin "2") (pinfunction "2_2") (pintype "passive"))
      (node (ref "P17") (pin "1") (pinfunction "1_1") (pintype "passive"))
      (node (ref "P2") (pin "4") (pinfunction "4_4") (pintype "passive"))
      (node (ref "P20") (pin "2") (pinfunction "2_2") (pintype "passive"))
      (node (ref "P21") (pin "3") (pinfunction "3_3") (pintype "passive"))
      (node (ref "P21") (pin "4") (pinfunction "4_4") (pintype "passive"))
      (node (ref "P22") (pin "1") (pinfunction "1_1") (pintype "passive"))
      (node (ref "P24") (pin "1") (pinfunction "1_1") (pintype "passive"))
      (node (ref "P25") (pin "1") (pinfunction "1_1") (pintype "passive"))
      (node (ref "P26") (pin "2") (pinfunction "2_2") (pintype "passive"))
      (node (ref "P27") (pin "17") (pinfunction "17_17") (pintype "passive"))
      (node (ref "P27") (pin "19") (pinfunction "19_19") (pintype "passive"))
      (node (ref "P27") (pin "7") (pinfunction "7_7") (pintype "passive"))
      (node (ref "P27") (pin "8") (pinfunction "8_8") (pintype "passive"))
      (node (ref "P3") (pin "4") (pinfunction "4_4") (pintype "passive"))
      (node (ref "P31") (pin "1") (pinfunction "1_1") (pintype "passive"))
      (node (ref "P4") (pin "4") (pinfunction "4_4") (pintype "passive"))
      (node (ref "P5") (pin "2") (pinfunction "2_2") (pintype "passive"))
      (node (ref "P6") (pin "2") (pinfunction "2_2") (pintype "passive"))
      (node (ref "P7") (pin "2") (pinfunction "2_2") (pintype "passive"))
      (node (ref "P8") (pin "19") (pinfunction "19_19") (pintype "passive"))
      (node (ref "P8") (pin "20") (pinfunction "20_20") (pintype "passive"))
      (node (ref "P8") (pin "29") (pinfunction "29_29") (pintype "passive"))
      (node (ref "P8") (pin "30") (pinfunction "30_30") (pintype "passive"))
      (node (ref "P8") (pin "41") (pinfunction "41_41") (pintype "passive"))
      (node (ref "P8") (pin "42") (pinfunction "42_42") (pintype "passive"))
      (node (ref "P8") (pin "5") (pinfunction "5_5") (pintype "passive"))
      (node (ref "P8") (pin "6") (pinfunction "6_6") (pintype "passive"))
      (node (ref "P9") (pin "2") (pinfunction "2_2") (pintype "passive"))
      (node (ref "Q3") (pin "2") (pinfunction "S_2") (pintype "passive"))
      (node (ref "Q5") (pin "2") (pinfunction "S_2") (pintype "passive"))
      (node (ref "Q6") (pin "2") (pinfunction "S_2") (pintype "passive"))
      (node (ref "Q8") (pin "2") (pinfunction "S_2") (pintype "passive"))
      (node (ref "Q9") (pin "2") (pinfunction "S_2") (pintype "passive"))
      (node (ref "R26") (pin "2") (pinfunction "2_2") (pintype "passive"))
      (node (ref "R29") (pin "2") (pinfunction "2_2") (pintype "passive"))
      (node (ref "R31") (pin "2") (pinfunction "2_2") (pintype "passive"))
      (node (ref "R33") (pin "2") (pinfunction "2_2") (pintype "passive"))
      (node (ref "R34") (pin "2") (pinfunction "2_2") (pintype "passive"))
      (node (ref "R43") (pin "1") (pinfunction "1_1") (pintype "passive"))
      (node (ref "R44") (pin "1") (pinfunction "1_1") (pintype "passive"))
      (node (ref "R45") (pin "2") (pinfunction "2_2") (pintype "passive"))
      (node (ref "R46") (pin "2") (pinfunction "2_2") (pintype "passive"))
      (node (ref "R50") (pin "1") (pinfunction "1_1") (pintype "passive"))
      (node (ref "R53") (pin "2") (pinfunction "2_2") (pintype "passive"))
      (node (ref "R6") (pin "1") (pinfunction "1_1") (pintype "passive"))
      (node (ref "R60") (pin "1") (pinfunction "1_1") (pintype "passive"))
      (node (ref "R63") (pin "1") (pinfunction "1_1") (pintype "passive"))
      (node (ref "R69") (pin "1") (pinfunction "1_1") (pintype "passive"))
      (node (ref "R7") (pin "1") (pinfunction "1_1") (pintype "passive"))
      (node (ref "R74") (pin "1") (pinfunction "1_1") (pintype "passive"))
      (node (ref "TP3") (pin "0") (pinfunction "0_0") (pintype "passive"))
      (node (ref "U1") (pin "13") (pinfunction "TEST2_13") (pintype "passive"))
      (node (ref "U1") (pin "33") (pinfunction "TEST3_33") (pintype "passive"))
      (node (ref "U1") (pin "57") (pinfunction "EPAD_57") (pintype "passive"))
      (node (ref "U10") (pin "3") (pinfunction "GND_3") (pintype "passive"))
      (node (ref "U11") (pin "9") (pinfunction "GND_9") (pintype "power_in"))
      (node (ref "U2") (pin "2") (pinfunction "GND_2") (pintype "passive"))
      (node (ref "U2") (pin "8") (pinfunction "S_8") (pintype "passive"))
      (node (ref "U3") (pin "2") (pinfunction "VSS_2") (pintype "passive"))
      (node (ref "U4") (pin "13") (pinfunction "PGND1_13") (pintype "passive"))
      (node (ref "U4") (pin "14") (pinfunction "PGND21_14") (pintype "passive"))
      (node (ref "U4") (pin "3") (pinfunction "PGND2_3") (pintype "passive"))
      (node (ref "U4") (pin "33") (pinfunction "GND_33") (pintype "passive"))
      (node (ref "U4") (pin "4") (pinfunction "PGND2_4") (pintype "passive"))
      (node (ref "U5") (pin "1") (pinfunction "BGND_1") (pintype "power_in"))
      (node (ref "U5") (pin "13") (pinfunction "AGND_13") (pintype "power_in"))
      (node (ref "U5") (pin "20") (pinfunction "HGND_20") (pintype "power_in"))
      (node (ref "U5") (pin "25") (pinfunction "PGND_25") (pintype "power_in"))
      (node (ref "U5") (pin "28") (pinfunction "TEST0_28") (pintype "input"))
      (node (ref "U5") (pin "6") (pinfunction "DGND_6") (pintype "power_in"))
      (node (ref "U6") (pin "1") (pinfunction "1_1") (pintype "passive"))
      (node (ref "U6") (pin "10") (pinfunction "10_10") (pintype "passive"))
      (node (ref "U6") (pin "15") (pinfunction "15_15") (pintype "passive"))
      (node (ref "U6") (pin "18") (pinfunction "18_18") (pintype "passive"))
      (node (ref "U6") (pin "4") (pinfunction "4_4") (pintype "passive"))
      (node (ref "U6") (pin "6") (pinfunction "6_6") (pintype "passive"))
      (node (ref "U6") (pin "8") (pinfunction "8_8") (pintype "passive"))
      (node (ref "U6") (pin "9") (pinfunction "9_9") (pintype "passive"))
      (node (ref "U7") (pin "4") (pinfunction "VSS_4") (pintype "power_in"))
      (node (ref "U8") (pin "1") (pinfunction "1_1") (pintype "passive"))
      (node (ref "U8") (pin "10") (pinfunction "10_10") (pintype "passive"))
      (node (ref "U8") (pin "15") (pinfunction "15_15") (pintype "passive"))
      (node (ref "U8") (pin "18") (pinfunction "18_18") (pintype "passive"))
      (node (ref "U8") (pin "4") (pinfunction "4_4") (pintype "passive"))
      (node (ref "U8") (pin "6") (pinfunction "6_6") (pintype "passive"))
      (node (ref "U8") (pin "8") (pinfunction "8_8") (pintype "passive"))
      (node (ref "U8") (pin "9") (pinfunction "9_9") (pintype "passive"))
      (node (ref "U9") (pin "7") (pinfunction "GND_7") (pintype "power_in"))
      (node (ref "U9") (pin "9") (pinfunction "EPAD_9") (pintype "passive"))
      (node (ref "U9") (pin "V") (pinfunction "V_V") (pintype "passive"))
      (node (ref "VR1") (pin "1") (pinfunction "GND_1") (pintype "passive"))
      (node (ref "VR2") (pin "1") (pinfunction "GND_1") (pintype "passive"))
    )
    (net (code "85") (name "Net-(C23-Pad2)") (class "Default")
      (node (ref "C23") (pin "2") (pinfunction "2_2") (pintype "passive"))
      (node (ref "L1") (pin "1") (pinfunction "1_1") (pintype "passive"))
      (node (ref "L1") (pin "2") (pinfunction "2_2") (pintype "passive"))
      (node (ref "U4") (pin "28") (pinfunction "LX2_28") (pintype "passive"))
      (node (ref "U4") (pin "29") (pinfunction "LX2_29") (pintype "passive"))
    )
    (net (code "86") (name "Net-(C31-Pad1)") (class "Default")
      (node (ref "C31") (pin "1") (pinfunction "1_1") (pintype "passive"))
      (node (ref "R21") (pin "1") (pinfunction "1_1") (pintype "passive"))
    )
    (net (code "87") (name "Net-(C36-Pad1)") (class "Default")
      (node (ref "C36") (pin "1") (pinfunction "1_1") (pintype "passive"))
      (node (ref "R23") (pin "1") (pinfunction "1_1") (pintype "passive"))
    )
    (net (code "88") (name "Net-(C41-Pad2)") (class "Default")
      (node (ref "C41") (pin "2") (pinfunction "2_2") (pintype "passive"))
      (node (ref "L2") (pin "1") (pinfunction "1_1") (pintype "passive"))
      (node (ref "L2") (pin "2") (pinfunction "2_2") (pintype "passive"))
      (node (ref "U4") (pin "20") (pinfunction "LX1_20") (pintype "passive"))
      (node (ref "U4") (pin "21") (pinfunction "LX1_21") (pintype "passive"))
    )
    (net (code "89") (name "Net-(C65-Pad2)") (class "Default")
      (node (ref "C65") (pin "2") (pinfunction "2_2") (pintype "passive"))
      (node (ref "P26") (pin "1") (pinfunction "1_1") (pintype "passive"))
      (node (ref "R52") (pin "1") (pinfunction "1_1") (pintype "passive"))
      (node (ref "TP6") (pin "0") (pinfunction "0_0") (pintype "passive"))
    )
    (net (code "90") (name "Net-(C67-Pad1)") (class "Default")
      (node (ref "C67") (pin "1") (pinfunction "1_1") (pintype "passive"))
      (node (ref "R54") (pin "1") (pinfunction "1_1") (pintype "passive"))
    )
    (net (code "91") (name "Net-(C69-Pad1)") (class "Default")
      (node (ref "C69") (pin "1") (pinfunction "1_1") (pintype "passive"))
      (node (ref "R56") (pin "1") (pinfunction "1_1") (pintype "passive"))
    )
    (net (code "92") (name "Net-(D1-PadK)") (class "Default")
      (node (ref "D1") (pin "K") (pinfunction "K_K") (pintype "passive"))
      (node (ref "R12") (pin "1") (pinfunction "1_1") (pintype "passive"))
    )
    (net (code "93") (name "Net-(D2-PadK)") (class "Default")
      (node (ref "D2") (pin "K") (pinfunction "K_K") (pintype "passive"))
      (node (ref "R13") (pin "1") (pinfunction "1_1") (pintype "passive"))
    )
    (net (code "94") (name "Net-(D3-PadK)") (class "Default")
      (node (ref "D3") (pin "K") (pinfunction "K_K") (pintype "passive"))
      (node (ref "R14") (pin "1") (pinfunction "1_1") (pintype "passive"))
    )
    (net (code "95") (name "Net-(D4-PadK)") (class "Default")
      (node (ref "D4") (pin "K") (pinfunction "K_K") (pintype "passive"))
      (node (ref "R26") (pin "1") (pinfunction "1_1") (pintype "passive"))
    )
    (net (code "96") (name "Net-(D5-PadK)") (class "Default")
      (node (ref "D5") (pin "K") (pinfunction "K_K") (pintype "passive"))
      (node (ref "R29") (pin "1") (pinfunction "1_1") (pintype "passive"))
    )
    (net (code "97") (name "Net-(D6-PadK)") (class "Default")
      (node (ref "D6") (pin "K") (pinfunction "K_K") (pintype "passive"))
      (node (ref "R31") (pin "1") (pinfunction "1_1") (pintype "passive"))
    )
    (net (code "98") (name "Net-(D7-PadK)") (class "Default")
      (node (ref "D7") (pin "K") (pinfunction "K_K") (pintype "passive"))
      (node (ref "R34") (pin "1") (pinfunction "1_1") (pintype "passive"))
    )
    (net (code "99") (name "Net-(D8-PadK)") (class "Default")
      (node (ref "D8") (pin "K") (pinfunction "K_K") (pintype "passive"))
      (node (ref "R36") (pin "2") (pinfunction "2_2") (pintype "passive"))
    )
    (net (code "100") (name "Net-(D9-PadK)") (class "Default")
      (node (ref "D9") (pin "K") (pinfunction "K_K") (pintype "passive"))
      (node (ref "R37") (pin "2") (pinfunction "2_2") (pintype "passive"))
    )
    (net (code "101") (name "Net-(J1-VBUS)") (class "Default")
      (node (ref "FB4") (pin "1") (pinfunction "1_1") (pintype "passive"))
      (node (ref "J1") (pin "1") (pinfunction "VBUS_1") (pintype "passive"))
    )
    (net (code "102") (name "Net-(J3-VBUS)") (class "Default")
      (node (ref "J3") (pin "1") (pinfunction "VBUS_1") (pintype "passive"))
      (node (ref "Q1") (pin "5") (pinfunction "5_5") (pintype "passive"))
      (node (ref "Q1") (pin "6") (pinfunction "6_6") (pintype "passive"))
      (node (ref "Q1") (pin "7") (pinfunction "7_7") (pintype "passive"))
      (node (ref "Q1") (pin "8") (pinfunction "8_8") (pintype "passive"))
    )
    (net (code "103") (name "Net-(P21-Pad1)") (class "Default")
      (node (ref "P21") (pin "1") (pinfunction "1_1") (pintype "passive"))
      (node (ref "P21") (pin "2") (pinfunction "2_2") (pintype "passive"))
      (node (ref "Q2") (pin "5") (pinfunction "5_5") (pintype "passive"))
      (node (ref "Q2") (pin "6") (pinfunction "6_6") (pintype "passive"))
      (node (ref "Q2") (pin "7") (pinfunction "7_7") (pintype "passive"))
      (node (ref "Q2") (pin "8") (pinfunction "8_8") (pintype "passive"))
    )
    (net (code "104") (name "Net-(P24-Pad2)") (class "Default")
      (node (ref "P24") (pin "2") (pinfunction "2_2") (pintype "passive"))
      (node (ref "Q4") (pin "5") (pinfunction "5_5") (pintype "passive"))
      (node (ref "Q4") (pin "6") (pinfunction "6_6") (pintype "passive"))
      (node (ref "Q4") (pin "7") (pinfunction "7_7") (pintype "passive"))
      (node (ref "Q4") (pin "8") (pinfunction "8_8") (pintype "passive"))
    )
    (net (code "105") (name "Net-(P25-Pad2)") (class "Default")
      (node (ref "P25") (pin "2") (pinfunction "2_2") (pintype "passive"))
      (node (ref "Q7") (pin "5") (pinfunction "5_5") (pintype "passive"))
      (node (ref "Q7") (pin "6") (pinfunction "6_6") (pintype "passive"))
      (node (ref "Q7") (pin "7") (pinfunction "7_7") (pintype "passive"))
      (node (ref "Q7") (pin "8") (pinfunction "8_8") (pintype "passive"))
    )
    (net (code "106") (name "Net-(P30-Pad2)") (class "Default")
      (node (ref "P30") (pin "2") (pinfunction "2_2") (pintype "passive"))
      (node (ref "Q2") (pin "4") (pinfunction "4_4") (pintype "passive"))
      (node (ref "R63") (pin "2") (pinfunction "2_2") (pintype "passive"))
    )
    (net (code "107") (name "Net-(Q3-D)") (class "Default")
      (node (ref "Q1") (pin "4") (pinfunction "4_4") (pintype "passive"))
      (node (ref "Q3") (pin "3") (pinfunction "D_3") (pintype "passive"))
      (node (ref "R61") (pin "1") (pinfunction "1_1") (pintype "passive"))
    )
    (net (code "108") (name "Net-(Q3-G)") (class "Default")
      (node (ref "Q3") (pin "1") (pinfunction "G_1") (pintype "passive"))
      (node (ref "R62") (pin "1") (pinfunction "1_1") (pintype "passive"))
      (node (ref "R64") (pin "2") (pinfunction "2_2") (pintype "passive"))
    )
    (net (code "109") (name "Net-(Q5-D)") (class "Default")
      (node (ref "Q4") (pin "4") (pinfunction "4_4") (pintype "passive"))
      (node (ref "Q5") (pin "3") (pinfunction "D_3") (pintype "passive"))
      (node (ref "R67") (pin "1") (pinfunction "1_1") (pintype "passive"))
    )
    (net (code "110") (name "Net-(Q5-G)") (class "Default")
      (node (ref "Q5") (pin "1") (pinfunction "G_1") (pintype "passive"))
      (node (ref "R68") (pin "2") (pinfunction "2_2") (pintype "passive"))
      (node (ref "R69") (pin "2") (pinfunction "2_2") (pintype "passive"))
    )
    (net (code "111") (name "Net-(Q6-D)") (class "Default")
      (node (ref "P24") (pin "4") (pinfunction "4_4") (pintype "passive"))
      (node (ref "Q6") (pin "3") (pinfunction "D_3") (pintype "passive"))
      (node (ref "R70") (pin "1") (pinfunction "1_1") (pintype "passive"))
    )
    (net (code "112") (name "Net-(Q6-G)") (class "Default")
      (node (ref "Q6") (pin "1") (pinfunction "G_1") (pintype "passive"))
      (node (ref "R71") (pin "1") (pinfunction "1_1") (pintype "passive"))
    )
    (net (code "113") (name "Net-(Q8-D)") (class "Default")
      (node (ref "Q7") (pin "4") (pinfunction "4_4") (pintype "passive"))
      (node (ref "Q8") (pin "3") (pinfunction "D_3") (pintype "passive"))
      (node (ref "R72") (pin "1") (pinfunction "1_1") (pintype "passive"))
    )
    (net (code "114") (name "Net-(Q8-G)") (class "Default")
      (node (ref "Q8") (pin "1") (pinfunction "G_1") (pintype "passive"))
      (node (ref "R73") (pin "2") (pinfunction "2_2") (pintype "passive"))
      (node (ref "R74") (pin "2") (pinfunction "2_2") (pintype "passive"))
    )
    (net (code "115") (name "Net-(Q9-D)") (class "Default")
      (node (ref "P25") (pin "4") (pinfunction "4_4") (pintype "passive"))
      (node (ref "Q9") (pin "3") (pinfunction "D_3") (pintype "passive"))
      (node (ref "R75") (pin "1") (pinfunction "1_1") (pintype "passive"))
    )
    (net (code "116") (name "Net-(Q9-G)") (class "Default")
      (node (ref "Q9") (pin "1") (pinfunction "G_1") (pintype "passive"))
      (node (ref "R76") (pin "1") (pinfunction "1_1") (pintype "passive"))
    )
    (net (code "117") (name "Net-(U1-EXRES)") (class "Default")
      (node (ref "R6") (pin "2") (pinfunction "2_2") (pintype "passive"))
      (node (ref "U1") (pin "8") (pinfunction "EXRES_8") (pintype "input"))
    )
    (net (code "118") (name "Net-(U1-USBRBIAS)") (class "Default")
      (node (ref "R7") (pin "2") (pinfunction "2_2") (pintype "passive"))
      (node (ref "U1") (pin "16") (pinfunction "USBRBIAS_16") (pintype "input"))
    )
    (net (code "119") (name "Net-(U1-VBUS_DET)") (class "Default")
      (node (ref "R9") (pin "2") (pinfunction "2_2") (pintype "passive"))
      (node (ref "U1") (pin "20") (pinfunction "VBUS_DET_20") (pintype "power_in"))
    )
    (net (code "120") (name "Net-(U2-RXD)") (class "Default")
      (node (ref "P18") (pin "2") (pinfunction "2_2") (pintype "passive"))
      (node (ref "U2") (pin "4") (pinfunction "RXD_4") (pintype "passive"))
    )
    (net (code "121") (name "Net-(U2-TXD)") (class "Default")
      (node (ref "P18") (pin "1") (pinfunction "1_1") (pintype "passive"))
      (node (ref "U2") (pin "1") (pinfunction "TXD_1") (pintype "passive"))
    )
    (net (code "122") (name "Net-(U4-BST1)") (class "Default")
      (node (ref "C41") (pin "1") (pinfunction "1_1") (pintype "passive"))
      (node (ref "U4") (pin "19") (pinfunction "BST1_19") (pintype "passive"))
    )
    (net (code "123") (name "Net-(U4-BST2)") (class "Default")
      (node (ref "C23") (pin "1") (pinfunction "1_1") (pintype "passive"))
      (node (ref "U4") (pin "30") (pinfunction "BST2_30") (pintype "passive"))
    )
    (net (code "124") (name "Net-(U4-COMP1)") (class "Default")
      (node (ref "C36") (pin "2") (pinfunction "2_2") (pintype "passive"))
      (node (ref "C37") (pin "1") (pinfunction "1_1") (pintype "passive"))
      (node (ref "U4") (pin "23") (pinfunction "COMP1_23") (pintype "passive"))
    )
    (net (code "125") (name "Net-(U4-COMP2)") (class "Default")
      (node (ref "C31") (pin "2") (pinfunction "2_2") (pintype "passive"))
      (node (ref "C35") (pin "1") (pinfunction "1_1") (pintype "passive"))
      (node (ref "U4") (pin "26") (pinfunction "COMP2_26") (pintype "passive"))
    )
    (net (code "126") (name "Net-(U4-EN1)") (class "Default")
      (node (ref "C20") (pin "1") (pinfunction "1_1") (pintype "passive"))
      (node (ref "R17") (pin "2") (pinfunction "2_2") (pintype "passive"))
      (node (ref "U4") (pin "1") (pinfunction "EN1_1") (pintype "passive"))
    )
    (net (code "127") (name "Net-(U4-EN2)") (class "Default")
      (node (ref "C21") (pin "1") (pinfunction "1_1") (pintype "passive"))
      (node (ref "R19") (pin "2") (pinfunction "2_2") (pintype "passive"))
      (node (ref "U4") (pin "2") (pinfunction "EN2_2") (pintype "passive"))
    )
    (net (code "128") (name "Net-(U4-MODE)") (class "Default")
      (node (ref "R22") (pin "1") (pinfunction "1_1") (pintype "passive"))
      (node (ref "R24") (pin "1") (pinfunction "1_1") (pintype "passive"))
      (node (ref "U4") (pin "8") (pinfunction "MODE_8") (pintype "passive"))
    )
    (net (code "129") (name "Net-(U4-RLIM1)") (class "Default")
      (node (ref "C48") (pin "1") (pinfunction "1_1") (pintype "passive"))
      (node (ref "R32") (pin "1") (pinfunction "1_1") (pintype "passive"))
      (node (ref "U4") (pin "18") (pinfunction "RLIM1_18") (pintype "passive"))
    )
    (net (code "130") (name "Net-(U4-RLIM2)") (class "Default")
      (node (ref "C22") (pin "1") (pinfunction "1_1") (pintype "passive"))
      (node (ref "R18") (pin "1") (pinfunction "1_1") (pintype "passive"))
      (node (ref "U4") (pin "31") (pinfunction "RLIM2_31") (pintype "passive"))
    )
    (net (code "131") (name "Net-(U4-ROSC)") (class "Default")
      (node (ref "R25") (pin "1") (pinfunction "1_1") (pintype "passive"))
      (node (ref "U4") (pin "24") (pinfunction "ROSC_24") (pintype "passive"))
    )
    (net (code "132") (name "Net-(U4-SS1)") (class "Default")
      (node (ref "C39") (pin "2") (pinfunction "2_2") (pintype "passive"))
      (node (ref "U4") (pin "22") (pinfunction "SS1_22") (pintype "passive"))
    )
    (net (code "133") (name "Net-(U4-SS2)") (class "Default")
      (node (ref "C33") (pin "2") (pinfunction "2_2") (pintype "passive"))
      (node (ref "U4") (pin "27") (pinfunction "SS2_27") (pintype "passive"))
    )
    (net (code "134") (name "Net-(U5-*PLAY)") (class "Default")
      (node (ref "R36") (pin "1") (pinfunction "1_1") (pintype "passive"))
      (node (ref "U5") (pin "32") (pinfunction "*PLAY_32") (pintype "output"))
    )
    (net (code "135") (name "Net-(U5-*REC)") (class "Default")
      (node (ref "R37") (pin "1") (pinfunction "1_1") (pintype "passive"))
      (node (ref "U5") (pin "31") (pinfunction "*REC_31") (pintype "output"))
    )
    (net (code "136") (name "Net-(U5-*SSPND)") (class "Default")
      (node (ref "P11") (pin "2") (pinfunction "2_2") (pintype "passive"))
      (node (ref "U5") (pin "29") (pinfunction "*SSPND_29") (pintype "output"))
    )
    (net (code "137") (name "Net-(U5-FL)") (class "Default")
      (node (ref "C53") (pin "2") (pinfunction "2_2") (pintype "passive"))
      (node (ref "U5") (pin "9") (pinfunction "FL_9") (pintype "passive"))
    )
    (net (code "138") (name "Net-(U5-FR)") (class "Default")
      (node (ref "C54") (pin "2") (pinfunction "2_2") (pintype "passive"))
      (node (ref "U5") (pin "10") (pinfunction "FR_10") (pintype "passive"))
    )
    (net (code "139") (name "Net-(U5-MAMP)") (class "Default")
      (node (ref "C50") (pin "2") (pinfunction "2_2") (pintype "passive"))
      (node (ref "U5") (pin "23") (pinfunction "MAMP_23") (pintype "input"))
      (node (ref "U5") (pin "24") (pinfunction "POWER_24") (pintype "power_in"))
      (node (ref "U5") (pin "26") (pinfunction "VCCP_26") (pintype "power_in"))
      (node (ref "U5") (pin "27") (pinfunction "TEST1_27") (pintype "input"))
    )
    (net (code "140") (name "Net-(U5-MBIAS)") (class "Default")
      (node (ref "C63") (pin "2") (pinfunction "2_2") (pintype "passive"))
      (node (ref "R48") (pin "2") (pinfunction "2_2") (pintype "passive"))
      (node (ref "U5") (pin "17") (pinfunction "MBIAS_17") (pintype "output"))
    )
    (net (code "141") (name "Net-(U5-MMUTE)") (class "Default")
      (node (ref "P11") (pin "1") (pinfunction "1_1") (pintype "passive"))
      (node (ref "U5") (pin "30") (pinfunction "MMUTE_30") (pintype "input"))
    )
    (net (code "142") (name "Net-(U5-VCCA)") (class "Default")
      (node (ref "C59") (pin "2") (pinfunction "2_2") (pintype "passive"))
      (node (ref "U5") (pin "15") (pinfunction "VCCA_15") (pintype "power_in"))
    )
    (net (code "143") (name "Net-(U5-VCCL)") (class "Default")
      (node (ref "C58") (pin "1") (pinfunction "1_1") (pintype "passive"))
      (node (ref "U5") (pin "19") (pinfunction "VCCL_19") (pintype "power_in"))
    )
    (net (code "144") (name "Net-(U5-VCCR)") (class "Default")
      (node (ref "C57") (pin "1") (pinfunction "1_1") (pintype "passive"))
      (node (ref "U5") (pin "21") (pinfunction "VCCR_21") (pintype "power_in"))
    )
    (net (code "145") (name "Net-(U5-VCOM1)") (class "Default")
      (node (ref "C56") (pin "2") (pinfunction "2_2") (pintype "passive"))
      (node (ref "U5") (pin "11") (pinfunction "VCOM1_11") (pintype "power_in"))
    )
    (net (code "146") (name "Net-(U5-VCOM2)") (class "Default")
      (node (ref "C55") (pin "2") (pinfunction "2_2") (pintype "passive"))
      (node (ref "U5") (pin "12") (pinfunction "VCOM2_12") (pintype "power_in"))
    )
    (net (code "147") (name "Net-(U5-VDD)") (class "Default")
      (node (ref "C51") (pin "2") (pinfunction "2_2") (pintype "passive"))
      (node (ref "R40") (pin "2") (pinfunction "2_2") (pintype "passive"))
      (node (ref "U5") (pin "5") (pinfunction "VDD_5") (pintype "power_in"))
    )
    (net (code "148") (name "Net-(U5-VIN)") (class "Default")
      (node (ref "C64") (pin "2") (pinfunction "2_2") (pintype "passive"))
      (node (ref "U5") (pin "16") (pinfunction "VIN_16") (pintype "input"))
    )
    (net (code "149") (name "Net-(U5-VOUTL)") (class "Default")
      (node (ref "C60") (pin "1") (pinfunction "1_1") (pintype "passive"))
      (node (ref "R45") (pin "1") (pinfunction "1_1") (pintype "passive"))
      (node (ref "U5") (pin "18") (pinfunction "VOUTL_18") (pintype "output"))
    )
    (net (code "150") (name "Net-(U5-VOUTR)") (class "Default")
      (node (ref "C52") (pin "1") (pinfunction "1_1") (pintype "passive"))
      (node (ref "R43") (pin "2") (pinfunction "2_2") (pintype "passive"))
      (node (ref "U5") (pin "22") (pinfunction "VOUTR_22") (pintype "output"))
    )
    (net (code "151") (name "Net-(U5-XTI)") (class "Default")
      (node (ref "C62") (pin "2") (pinfunction "2_2") (pintype "passive"))
      (node (ref "R42") (pin "2") (pinfunction "2_2") (pintype "passive"))
      (node (ref "U5") (pin "8") (pinfunction "XTI_8") (pintype "input"))
      (node (ref "Y2") (pin "1") (pinfunction "OSC1_1") (pintype "passive"))
    )
    (net (code "152") (name "Net-(U5-XTO)") (class "Default")
      (node (ref "C61") (pin "2") (pinfunction "2_2") (pintype "passive"))
      (node (ref "R42") (pin "1") (pinfunction "1_1") (pintype "passive"))
      (node (ref "U5") (pin "7") (pinfunction "XTO_7") (pintype "output"))
      (node (ref "Y2") (pin "3") (pinfunction "OSC2_3") (pintype "passive"))
    )
    (net (code "153") (name "Net-(U7A-VINA+)") (class "Default")
      (node (ref "C65") (pin "1") (pinfunction "1_1") (pintype "passive"))
      (node (ref "R51") (pin "2") (pinfunction "2_2") (pintype "passive"))
      (node (ref "R53") (pin "1") (pinfunction "1_1") (pintype "passive"))
      (node (ref "U7") (pin "3") (pinfunction "VINA+_3") (pintype "input"))
    )
    (net (code "154") (name "Net-(U7A-VINA-)") (class "Default")
      (node (ref "R55") (pin "2") (pinfunction "2_2") (pintype "passive"))
      (node (ref "U7") (pin "1") (pinfunction "VOUTA_1") (pintype "output"))
      (node (ref "U7") (pin "2") (pinfunction "VINA-_2") (pintype "input"))
    )
    (net (code "155") (name "Net-(U7B-VINB+)") (class "Default")
      (node (ref "R58") (pin "2") (pinfunction "2_2") (pintype "passive"))
      (node (ref "R60") (pin "2") (pinfunction "2_2") (pintype "passive"))
      (node (ref "U7") (pin "5") (pinfunction "VINB+_5") (pintype "input"))
    )
    (net (code "156") (name "Net-(U7B-VINB-)") (class "Default")
      (node (ref "C68") (pin "1") (pinfunction "1_1") (pintype "passive"))
      (node (ref "R55") (pin "1") (pinfunction "1_1") (pintype "passive"))
      (node (ref "R57") (pin "2") (pinfunction "2_2") (pintype "passive"))
      (node (ref "U7") (pin "6") (pinfunction "VINB-_6") (pintype "input"))
    )
    (net (code "157") (name "Net-(U9-BYPASS)") (class "Default")
      (node (ref "C70") (pin "2") (pinfunction "2_2") (pintype "passive"))
      (node (ref "U9") (pin "2") (pinfunction "BYPASS_2") (pintype "passive"))
    )
    (net (code "158") (name "Net-(U9-IN+)") (class "Default")
      (node (ref "R54") (pin "2") (pinfunction "2_2") (pintype "passive"))
      (node (ref "U9") (pin "3") (pinfunction "IN+_3") (pintype "input"))
    )
    (net (code "159") (name "Net-(U9-IN-)") (class "Default")
      (node (ref "R56") (pin "2") (pinfunction "2_2") (pintype "passive"))
      (node (ref "U9") (pin "4") (pinfunction "IN-_4") (pintype "input"))
    )
    (net (code "160") (name "Net-(U9-~{SHUTDOWN})") (class "Default")
      (node (ref "R59") (pin "1") (pinfunction "1_1") (pintype "passive"))
      (node (ref "TP8") (pin "0") (pinfunction "0_0") (pintype "passive"))
      (node (ref "U9") (pin "1") (pinfunction "~{SHUTDOWN}_1") (pintype "input"))
    )
    (net (code "161") (name "Net-(U11-COM_D)") (class "Default")
      (node (ref "R65") (pin "1") (pinfunction "1_1") (pintype "passive"))
      (node (ref "R66") (pin "1") (pinfunction "1_1") (pintype "passive"))
      (node (ref "U11") (pin "10") (pinfunction "COM_D_10") (pintype "passive"))
    )
    (net (code "162") (name "VDD33A") (class "Default")
      (node (ref "C2") (pin "2") (pinfunction "2_2") (pintype "passive"))
      (node (ref "C3") (pin "2") (pinfunction "2_2") (pintype "passive"))
      (node (ref "C4") (pin "2") (pinfunction "2_2") (pintype "passive"))
      (node (ref "C5") (pin "2") (pinfunction "2_2") (pintype "passive"))
      (node (ref "FB1") (pin "2") (pinfunction "2_2") (pintype "passive"))
      (node (ref "R1") (pin "2") (pinfunction "2_2") (pintype "passive"))
      (node (ref "R2") (pin "2") (pinfunction "2_2") (pintype "passive"))
      (node (ref "R3") (pin "2") (pinfunction "2_2") (pintype "passive"))
      (node (ref "R4") (pin "2") (pinfunction "2_2") (pintype "passive"))
      (node (ref "U1") (pin "15") (pinfunction "VDD33A_15") (pintype "power_in"))
      (node (ref "U1") (pin "4") (pinfunction "VDD33A_4") (pintype "power_in"))
      (node (ref "U1") (pin "7") (pinfunction "VDD33A_7") (pintype "power_in"))
      (node (ref "U1") (pin "9") (pinfunction "VDD33A_9") (pintype "power_in"))
    )
    (net (code "163") (name "VDDCORE") (class "Default")
      (node (ref "C12") (pin "2") (pinfunction "2_2") (pintype "passive"))
      (node (ref "C13") (pin "2") (pinfunction "2_2") (pintype "passive"))
      (node (ref "C14") (pin "2") (pinfunction "2_2") (pintype "passive"))
      (node (ref "FB2") (pin "1") (pinfunction "1_1") (pintype "passive"))
      (node (ref "FB3") (pin "1") (pinfunction "1_1") (pintype "passive"))
      (node (ref "U1") (pin "21") (pinfunction "VDDCORE_21") (pintype "power_in"))
      (node (ref "U1") (pin "50") (pinfunction "VDDCORE_50") (pintype "power_in"))
    )
    (net (code "164") (name "VDDPLL") (class "Default")
      (node (ref "C15") (pin "2") (pinfunction "2_2") (pintype "passive"))
      (node (ref "FB3") (pin "2") (pinfunction "2_2") (pintype "passive"))
      (node (ref "U1") (pin "10") (pinfunction "VDDPLL_10") (pintype "power_in"))
    )
    (net (code "165") (name "VDDUSBPLL") (class "Default")
      (node (ref "C6") (pin "2") (pinfunction "2_2") (pintype "passive"))
      (node (ref "FB2") (pin "2") (pinfunction "2_2") (pintype "passive"))
      (node (ref "U1") (pin "17") (pinfunction "VDDUSBPLL_17") (pintype "power_in"))
    )
    (net (code "166") (name "unconnected-(J1-SHIELD-PadS1)") (class "Default")
      (node (ref "J1") (pin "S1") (pinfunction "SHIELD_S1") (pintype "passive"))
    )
    (net (code "167") (name "unconnected-(J1-SHIELD-PadS2)") (class "Default")
      (node (ref "J1") (pin "S2") (pinfunction "SHIELD_S2") (pintype "passive"))
    )
    (net (code "168") (name "unconnected-(J1-SSRX+-Pad6)") (class "Default")
      (node (ref "J1") (pin "6") (pinfunction "SSRX+_6") (pintype "passive"))
    )
    (net (code "169") (name "unconnected-(J1-SSRX--Pad5)") (class "Default")
      (node (ref "J1") (pin "5") (pinfunction "SSRX-_5") (pintype "passive"))
    )
    (net (code "170") (name "unconnected-(J1-SSTX+-Pad9)") (class "Default")
      (node (ref "J1") (pin "9") (pinfunction "SSTX+_9") (pintype "passive"))
    )
    (net (code "171") (name "unconnected-(J1-SSTX--Pad8)") (class "Default")
      (node (ref "J1") (pin "8") (pinfunction "SSTX-_8") (pintype "passive"))
    )
    (net (code "172") (name "unconnected-(J2-SHIELD-PadS1)") (class "Default")
      (node (ref "J2") (pin "S1") (pinfunction "SHIELD_S1") (pintype "passive"))
    )
    (net (code "173") (name "unconnected-(J2-SHIELD-PadS2)") (class "Default")
      (node (ref "J2") (pin "S2") (pinfunction "SHIELD_S2") (pintype "passive"))
    )
    (net (code "174") (name "unconnected-(J2-SSRX+-Pad6)") (class "Default")
      (node (ref "J2") (pin "6") (pinfunction "SSRX+_6") (pintype "passive"))
    )
    (net (code "175") (name "unconnected-(J2-SSRX--Pad5)") (class "Default")
      (node (ref "J2") (pin "5") (pinfunction "SSRX-_5") (pintype "passive"))
    )
    (net (code "176") (name "unconnected-(J2-SSTX+-Pad9)") (class "Default")
      (node (ref "J2") (pin "9") (pinfunction "SSTX+_9") (pintype "passive"))
    )
    (net (code "177") (name "unconnected-(J2-SSTX--Pad8)") (class "Default")
      (node (ref "J2") (pin "8") (pinfunction "SSTX-_8") (pintype "passive"))
    )
    (net (code "178") (name "unconnected-(J2-VBUS-Pad1)") (class "Default")
      (node (ref "J2") (pin "1") (pinfunction "VBUS_1") (pintype "passive"))
    )
    (net (code "179") (name "unconnected-(J3-D+-Pad3)") (class "Default")
      (node (ref "J3") (pin "3") (pinfunction "D+_3") (pintype "passive"))
    )
    (net (code "180") (name "unconnected-(J3-D--Pad2)") (class "Default")
      (node (ref "J3") (pin "2") (pinfunction "D-_2") (pintype "passive"))
    )
    (net (code "181") (name "unconnected-(J3-SHIELD-PadS1)") (class "Default")
      (node (ref "J3") (pin "S1") (pinfunction "SHIELD_S1") (pintype "passive"))
    )
    (net (code "182") (name "unconnected-(J3-SHIELD-PadS2)") (class "Default")
      (node (ref "J3") (pin "S2") (pinfunction "SHIELD_S2") (pintype "passive"))
    )
    (net (code "183") (name "unconnected-(J3-SSRX+-Pad6)") (class "Default")
      (node (ref "J3") (pin "6") (pinfunction "SSRX+_6") (pintype "passive"))
    )
    (net (code "184") (name "unconnected-(J3-SSRX--Pad5)") (class "Default")
      (node (ref "J3") (pin "5") (pinfunction "SSRX-_5") (pintype "passive"))
    )
    (net (code "185") (name "unconnected-(J3-SSTX+-Pad9)") (class "Default")
      (node (ref "J3") (pin "9") (pinfunction "SSTX+_9") (pintype "passive"))
    )
    (net (code "186") (name "unconnected-(J3-SSTX--Pad8)") (class "Default")
      (node (ref "J3") (pin "8") (pinfunction "SSTX-_8") (pintype "passive"))
    )
    (net (code "187") (name "unconnected-(P24-Pad3)") (class "Default")
      (node (ref "P24") (pin "3") (pinfunction "3_3") (pintype "passive"))
    )
    (net (code "188") (name "unconnected-(P25-Pad3)") (class "Default")
      (node (ref "P25") (pin "3") (pinfunction "3_3") (pintype "passive"))
    )
    (net (code "189") (name "unconnected-(P27-Pad13)") (class "Default")
      (node (ref "P27") (pin "13") (pinfunction "13_13") (pintype "passive"))
    )
    (net (code "190") (name "unconnected-(P27-Pad14)") (class "Default")
      (node (ref "P27") (pin "14") (pinfunction "14_14") (pintype "passive"))
    )
    (net (code "191") (name "unconnected-(P27-Pad15)") (class "Default")
      (node (ref "P27") (pin "15") (pinfunction "15_15") (pintype "passive"))
    )
    (net (code "192") (name "unconnected-(P27-Pad16)") (class "Default")
      (node (ref "P27") (pin "16") (pinfunction "16_16") (pintype "passive"))
    )
    (net (code "193") (name "unconnected-(U1-COL{slash}GPIO0-Pad46)") (class "Default")
      (node (ref "U1") (pin "46") (pinfunction "COL/GPIO0_46") (pintype "bidirectional"))
    )
    (net (code "194") (name "unconnected-(U1-CRS{slash}GPIO3-Pad45)") (class "Default")
      (node (ref "U1") (pin "45") (pinfunction "CRS/GPIO3_45") (pintype "bidirectional"))
    )
    (net (code "195") (name "unconnected-(U1-MDC{slash}GPIO2-Pad22)") (class "Default")
      (node (ref "U1") (pin "22") (pinfunction "MDC/GPIO2_22") (pintype "bidirectional"))
    )
    (net (code "196") (name "unconnected-(U1-MDIO{slash}GPIO1-Pad23)") (class "Default")
      (node (ref "U1") (pin "23") (pinfunction "MDIO/GPIO1_23") (pintype "bidirectional"))
    )
    (net (code "197") (name "unconnected-(U1-NC-Pad14)") (class "Default")
      (node (ref "U1") (pin "14") (pinfunction "NC_14") (pintype "passive"))
    )
    (net (code "198") (name "unconnected-(U1-NPHY_INT-Pad1)") (class "Default")
      (node (ref "U1") (pin "1") (pinfunction "NPHY_INT_1") (pintype "bidirectional"))
    )
    (net (code "199") (name "unconnected-(U1-NTRST{slash}RXD0-Pad36)") (class "Default")
      (node (ref "U1") (pin "36") (pinfunction "NTRST/RXD0_36") (pintype "bidirectional"))
    )
    (net (code "200") (name "unconnected-(U1-PHY_SEL-Pad34)") (class "Default")
      (node (ref "U1") (pin "34") (pinfunction "PHY_SEL_34") (pintype "input"))
    )
    (net (code "201") (name "unconnected-(U1-RXCLK-Pad41)") (class "Default")
      (node (ref "U1") (pin "41") (pinfunction "RXCLK_41") (pintype "input"))
    )
    (net (code "202") (name "unconnected-(U1-RXDV-Pad42)") (class "Default")
      (node (ref "U1") (pin "42") (pinfunction "RXDV_42") (pintype "input"))
    )
    (net (code "203") (name "unconnected-(U1-RXER-Pad44)") (class "Default")
      (node (ref "U1") (pin "44") (pinfunction "RXER_44") (pintype "input"))
    )
    (net (code "204") (name "unconnected-(U1-TCK{slash}RXD1-Pad38)") (class "Default")
      (node (ref "U1") (pin "38") (pinfunction "TCK/RXD1_38") (pintype "bidirectional"))
    )
    (net (code "205") (name "unconnected-(U1-TDI{slash}TXD3-Pad40)") (class "Default")
      (node (ref "U1") (pin "40") (pinfunction "TDI/TXD3_40") (pintype "bidirectional"))
    )
    (net (code "206") (name "unconnected-(U1-TDO{slash}NPHY_RST-Pad37)") (class "Default")
      (node (ref "U1") (pin "37") (pinfunction "TDO/NPHY_RST_37") (pintype "bidirectional"))
    )
    (net (code "207") (name "unconnected-(U1-TMS{slash}RXD2-Pad39)") (class "Default")
      (node (ref "U1") (pin "39") (pinfunction "TMS/RXD2_39") (pintype "bidirectional"))
    )
    (net (code "208") (name "unconnected-(U1-TXCLK-Pad47)") (class "Default")
      (node (ref "U1") (pin "47") (pinfunction "TXCLK_47") (pintype "input"))
    )
    (net (code "209") (name "unconnected-(U1-TXD0{slash}GPIO4{slash}*EEP_DISABLE-Pad56)") (class "Default")
      (node (ref "U1") (pin "56") (pinfunction "TXD0/GPIO4/*EEP_DISABLE_56") (pintype "bidirectional"))
    )
    (net (code "210") (name "unconnected-(U1-TXD1{slash}GPIO5{slash}*RMT_WKP-Pad55)") (class "Default")
      (node (ref "U1") (pin "55") (pinfunction "TXD1/GPIO5/*RMT_WKP_55") (pintype "bidirectional"))
    )
    (net (code "211") (name "unconnected-(U1-TXD2{slash}GPIO6{slash}*PORT_SWAP-Pad54)") (class "Default")
      (node (ref "U1") (pin "54") (pinfunction "TXD2/GPIO6/*PORT_SWAP_54") (pintype "bidirectional"))
    )
    (net (code "212") (name "unconnected-(U1-TXD3{slash}GPIO7{slash}*EEP_SIZE-Pad53)") (class "Default")
      (node (ref "U1") (pin "53") (pinfunction "TXD3/GPIO7/*EEP_SIZE_53") (pintype "bidirectional"))
    )
    (net (code "213") (name "unconnected-(U1-TXEN-Pad43)") (class "Default")
      (node (ref "U1") (pin "43") (pinfunction "TXEN_43") (pintype "output"))
    )
    (net (code "214") (name "unconnected-(U2-n.c.-Pad5)") (class "Default")
      (node (ref "U2") (pin "5") (pinfunction "n.c._5") (pintype "passive"))
    )
    (net (code "215") (name "unconnected-(U6-Pad5)") (class "Default")
      (node (ref "U6") (pin "5") (pinfunction "5_5") (pintype "passive"))
    )
    (net (code "216") (name "unconnected-(U6-Pad7)") (class "Default")
      (node (ref "U6") (pin "7") (pinfunction "7_7") (pintype "passive"))
    )
    (net (code "217") (name "unconnected-(U6-Pad11)") (class "Default")
      (node (ref "U6") (pin "11") (pinfunction "11_11") (pintype "passive"))
    )
    (net (code "218") (name "unconnected-(U6-Pad12)") (class "Default")
      (node (ref "U6") (pin "12") (pinfunction "12_12") (pintype "passive"))
    )
    (net (code "219") (name "unconnected-(U6-Pad13)") (class "Default")
      (node (ref "U6") (pin "13") (pinfunction "13_13") (pintype "passive"))
    )
    (net (code "220") (name "unconnected-(U6-Pad14)") (class "Default")
      (node (ref "U6") (pin "14") (pinfunction "14_14") (pintype "passive"))
    )
    (net (code "221") (name "unconnected-(U6-Pad16)") (class "Default")
      (node (ref "U6") (pin "16") (pinfunction "16_16") (pintype "passive"))
    )
    (net (code "222") (name "unconnected-(U6-Pad17)") (class "Default")
      (node (ref "U6") (pin "17") (pinfunction "17_17") (pintype "passive"))
    )
    (net (code "223") (name "unconnected-(U6-Pad26)") (class "Default")
      (node (ref "U6") (pin "26") (pinfunction "26_26") (pintype "passive"))
    )
    (net (code "224") (name "unconnected-(U6-Pad27)") (class "Default")
      (node (ref "U6") (pin "27") (pinfunction "27_27") (pintype "passive"))
    )
    (net (code "225") (name "unconnected-(U7A-VSS-Pad4)") (class "Default")
      (node (ref "U7") (pin "4") (pinfunction "VSS_4") (pintype "power_in"))
    )
    (net (code "226") (name "unconnected-(U7B-VDD-Pad8)") (class "Default")
      (node (ref "U7") (pin "8") (pinfunction "VDD_8") (pintype "power_in"))
    )
    (net (code "227") (name "unconnected-(U8-Pad5)") (class "Default")
      (node (ref "U8") (pin "5") (pinfunction "5_5") (pintype "passive"))
    )
    (net (code "228") (name "unconnected-(U8-Pad7)") (class "Default")
      (node (ref "U8") (pin "7") (pinfunction "7_7") (pintype "passive"))
    )
    (net (code "229") (name "unconnected-(U8-Pad16)") (class "Default")
      (node (ref "U8") (pin "16") (pinfunction "16_16") (pintype "passive"))
    )
    (net (code "230") (name "unconnected-(U8-Pad17)") (class "Default")
      (node (ref "U8") (pin "17") (pinfunction "17_17") (pintype "passive"))
    )
    (net (code "231") (name "unconnected-(U8-Pad26)") (class "Default")
      (node (ref "U8") (pin "26") (pinfunction "26_26") (pintype "passive"))
    )
    (net (code "232") (name "unconnected-(U8-Pad27)") (class "Default")
      (node (ref "U8") (pin "27") (pinfunction "27_27") (pintype "passive"))
    )
  )
)
